# Node_Plant_Project.net
KiCad netlist of a schematic drawn in EasyEDA
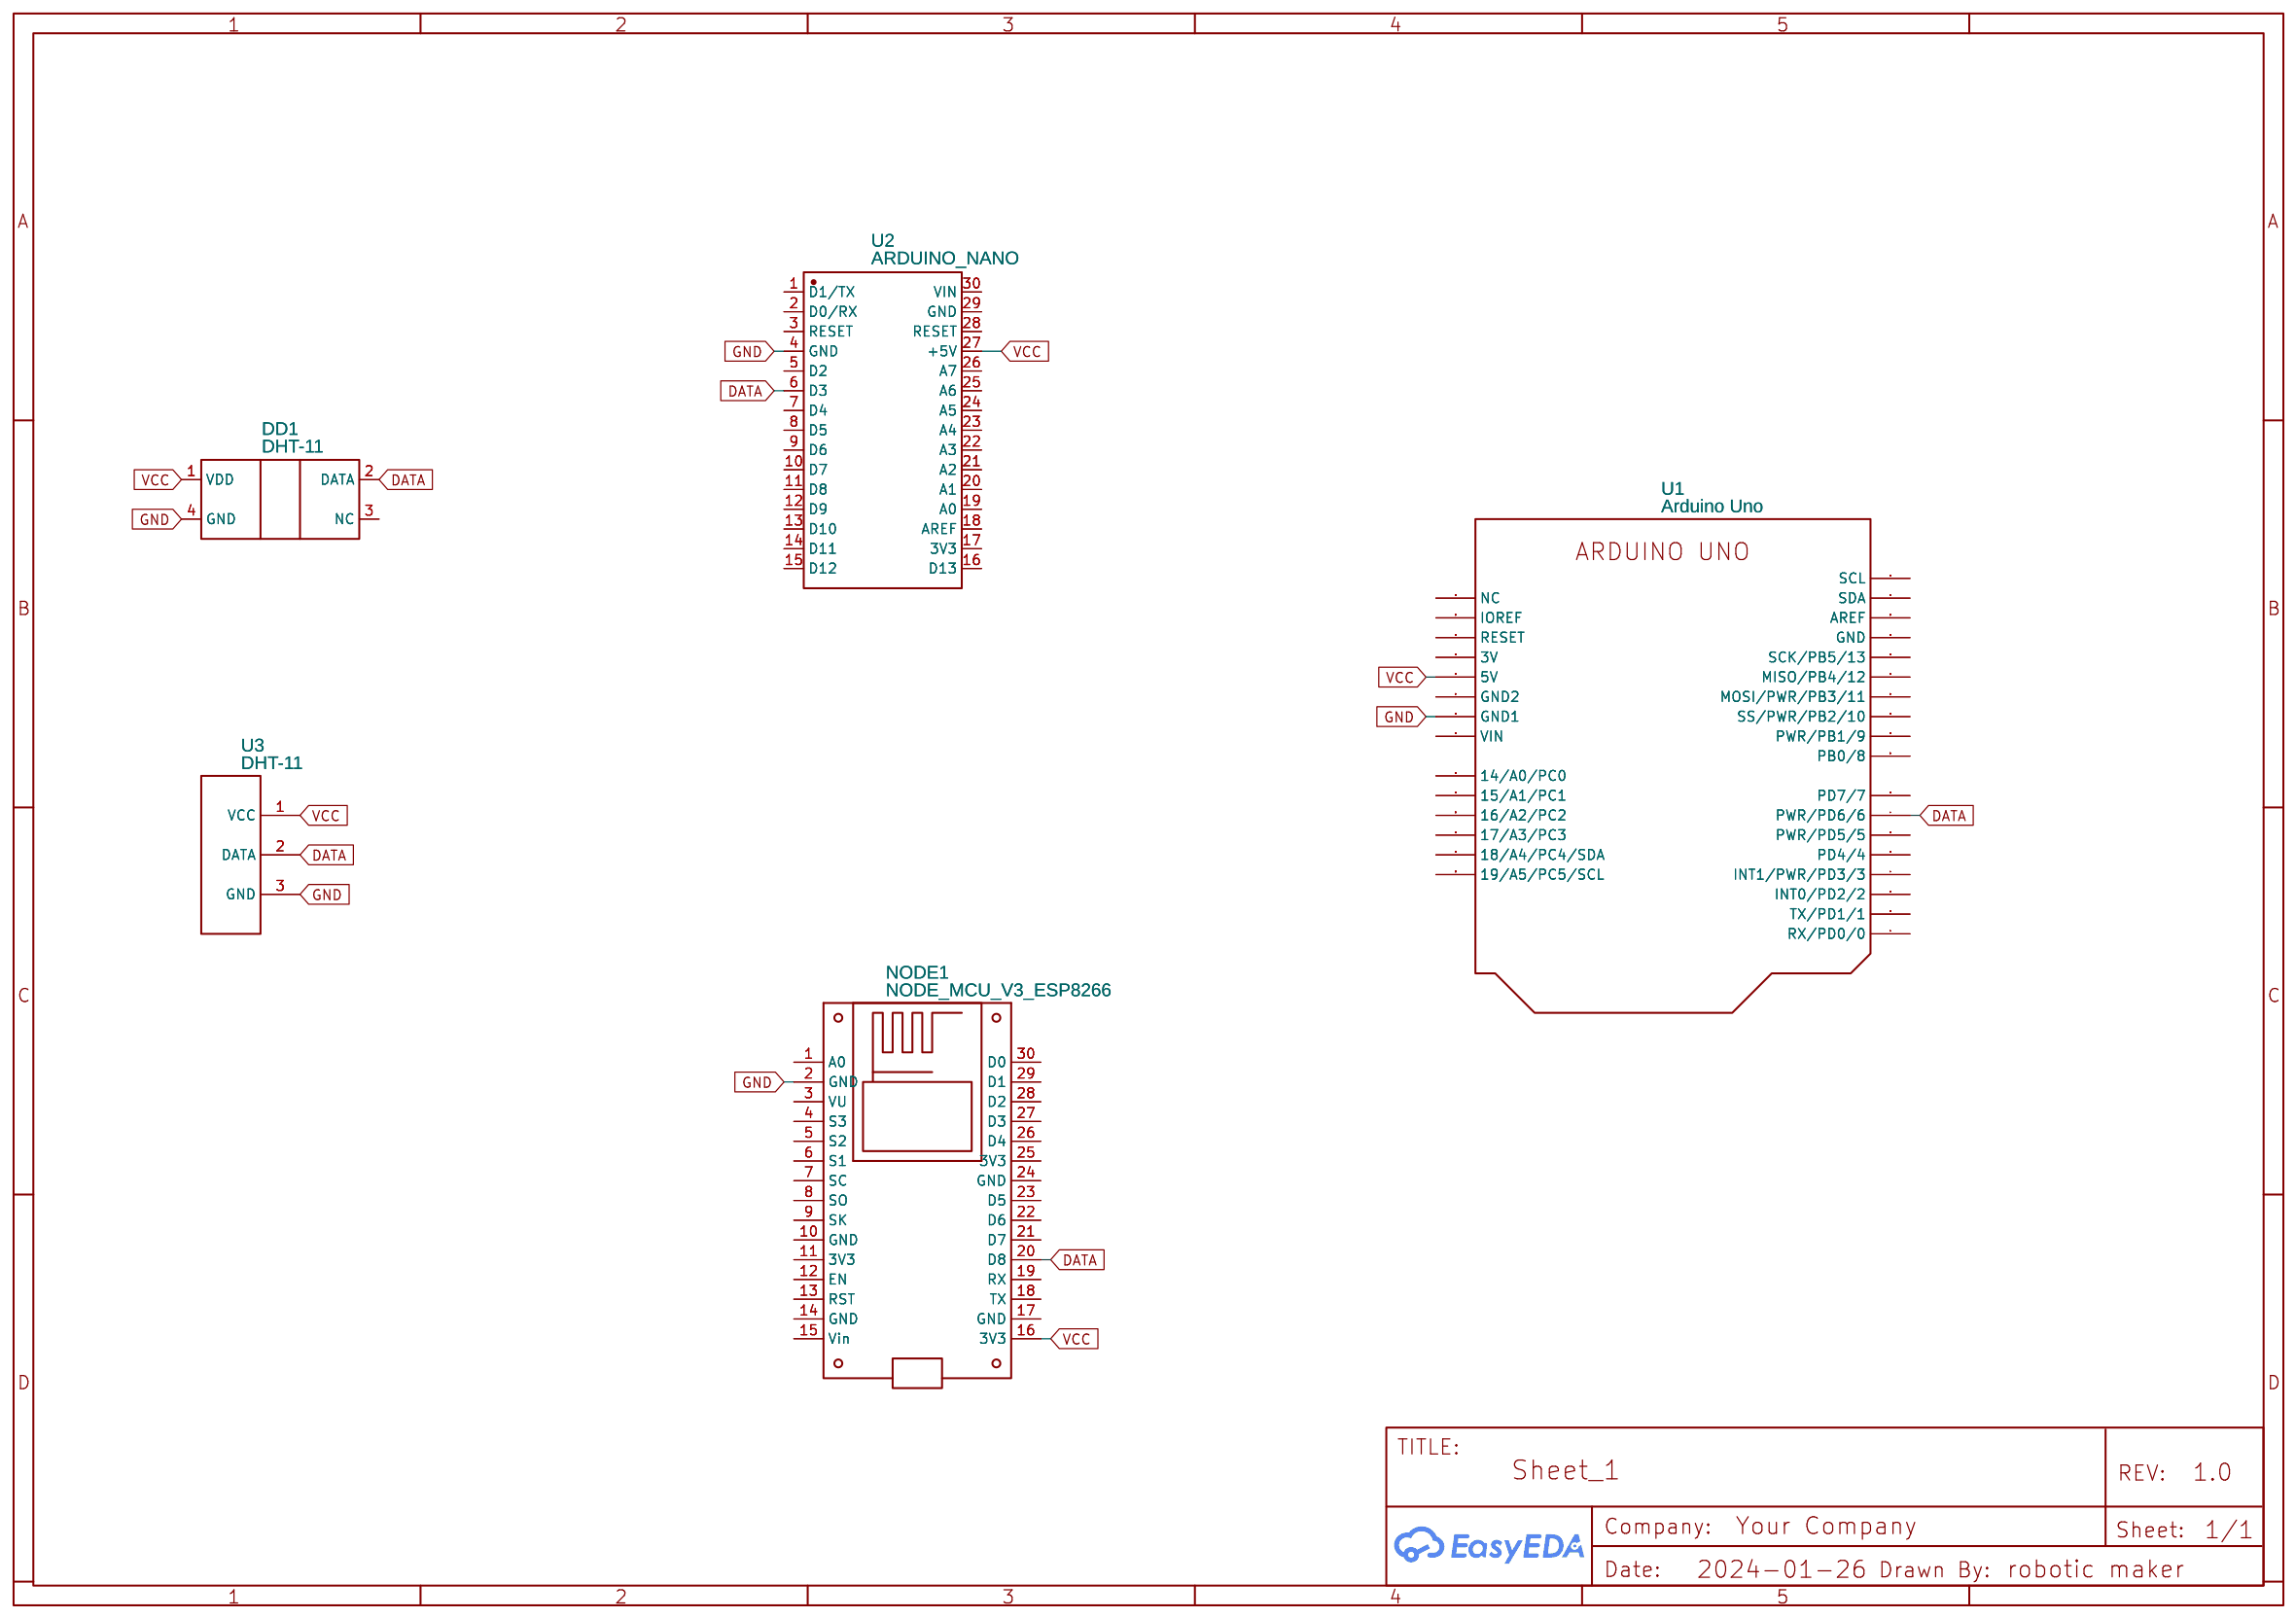
[diagram p0: DHT-11 & DHT-22]
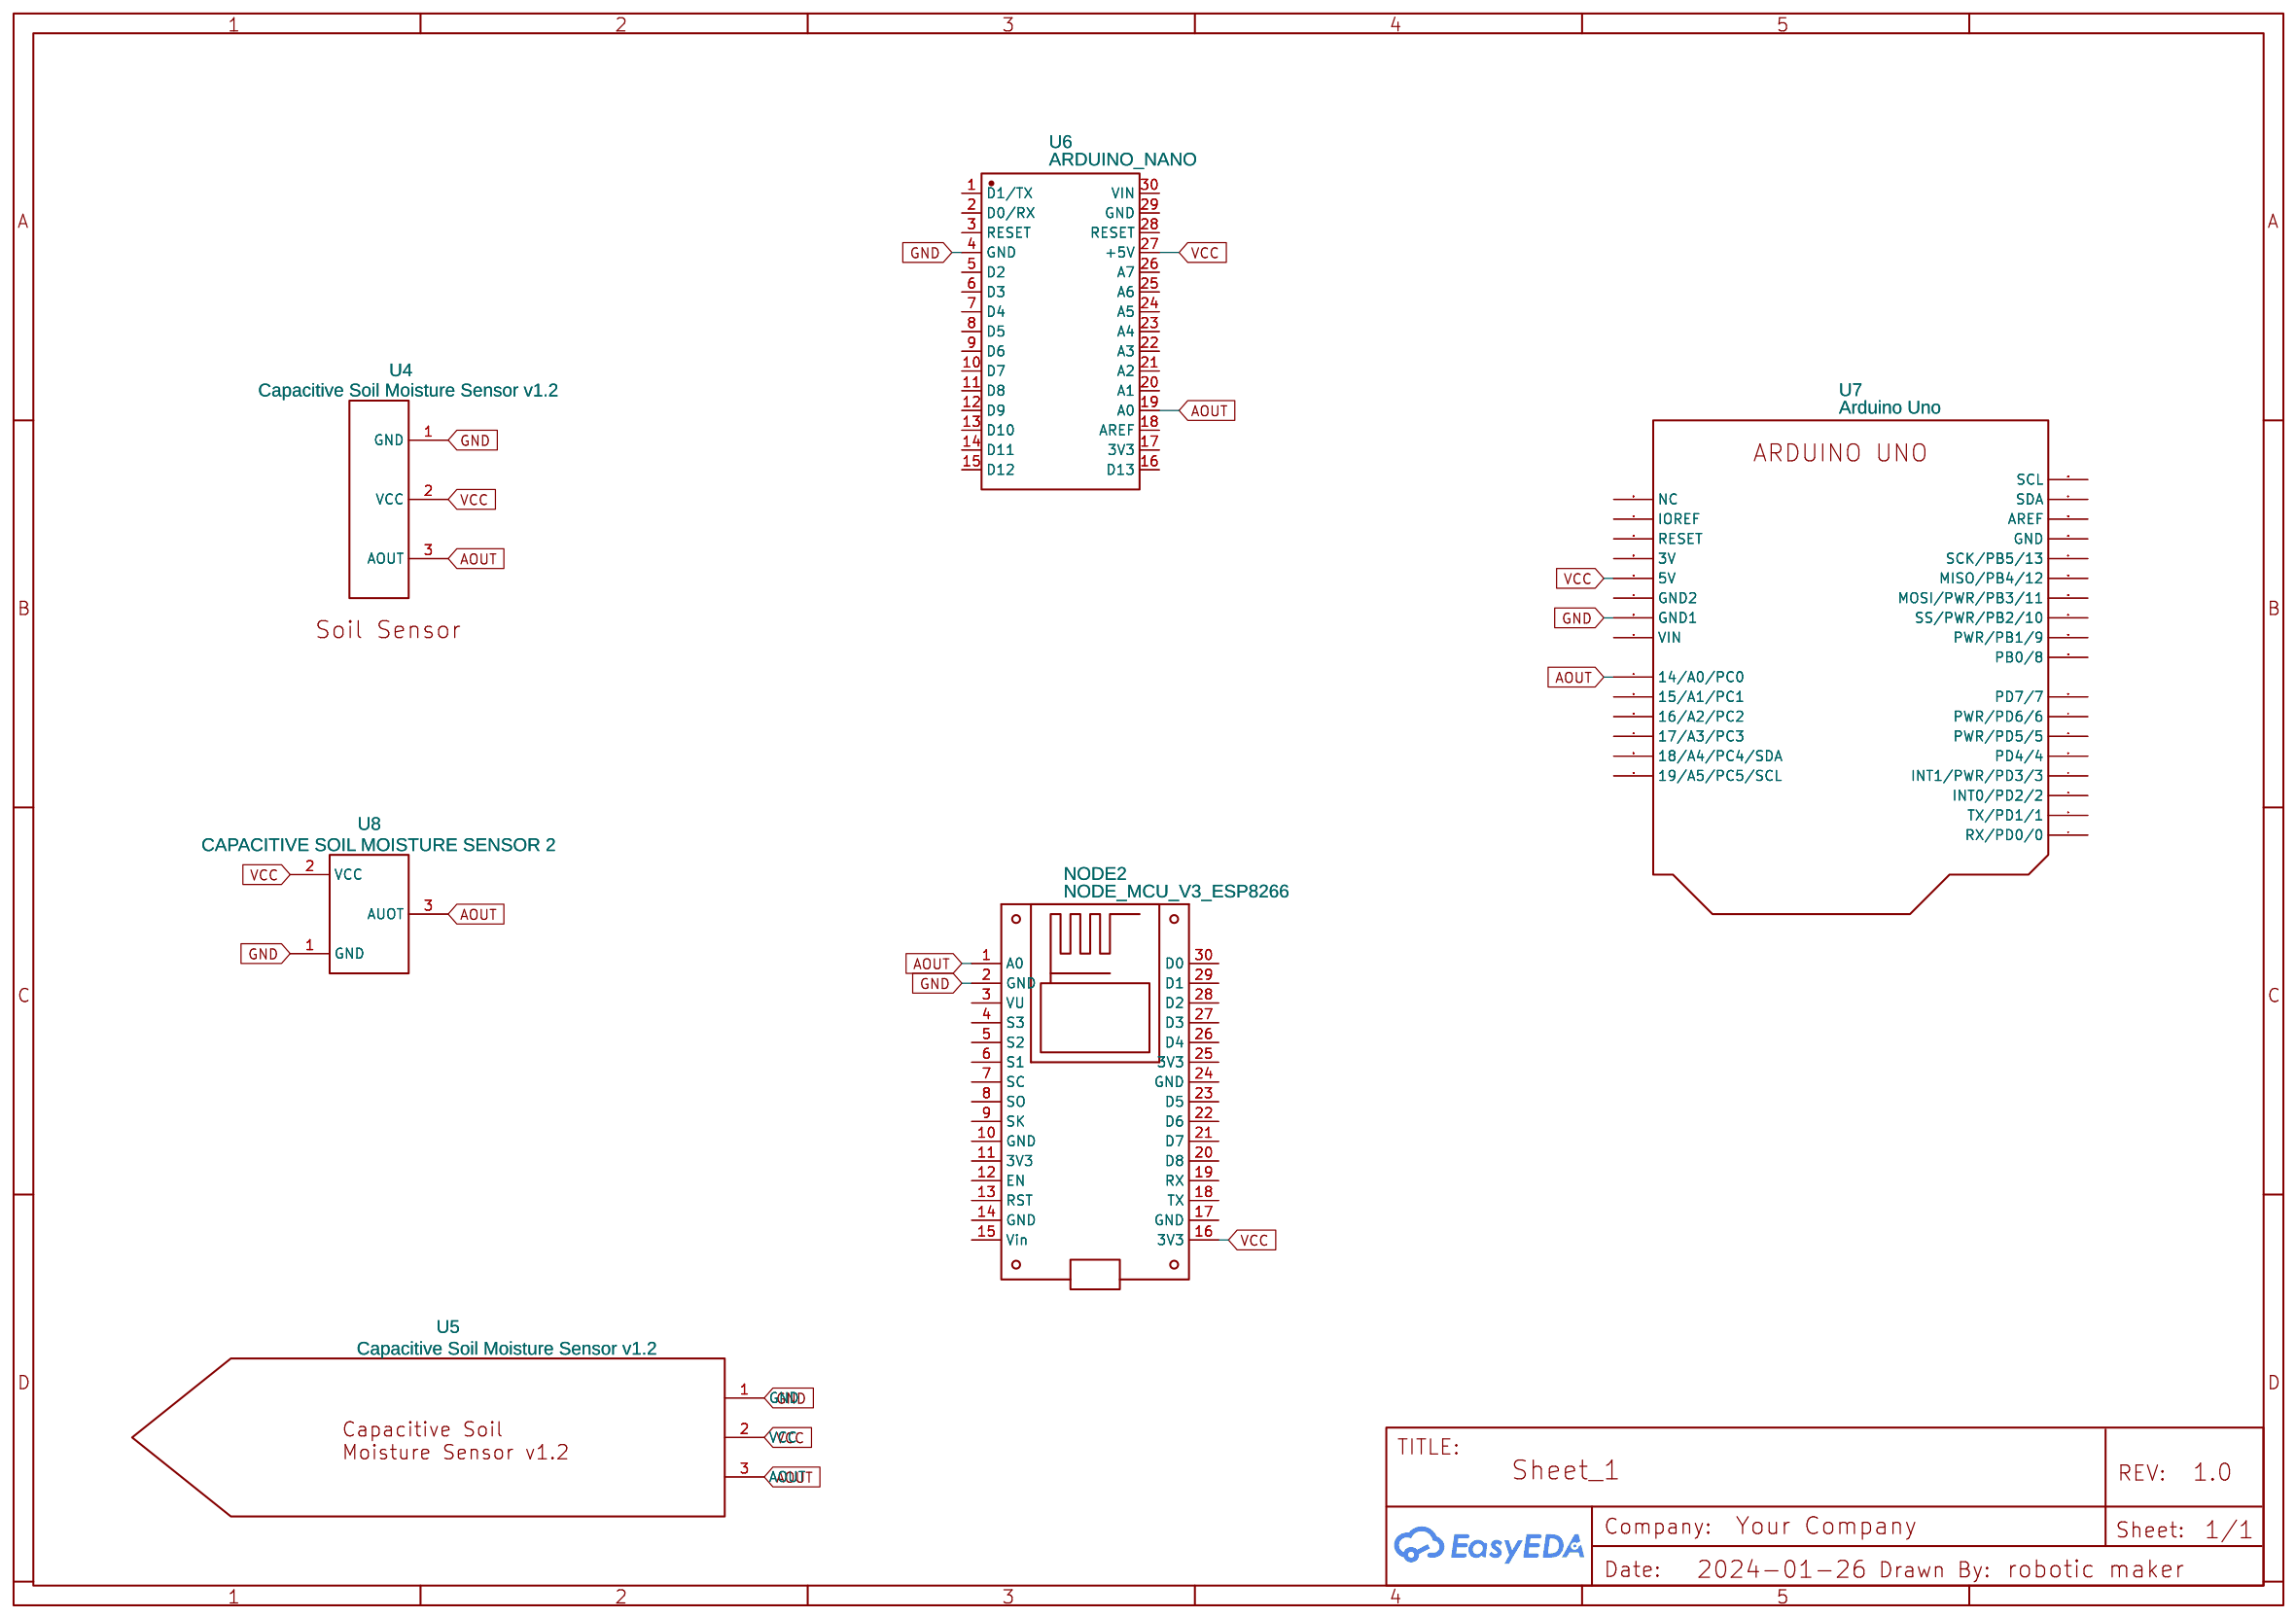
[diagram p1: Capacitive Soil Moisture Sensor]
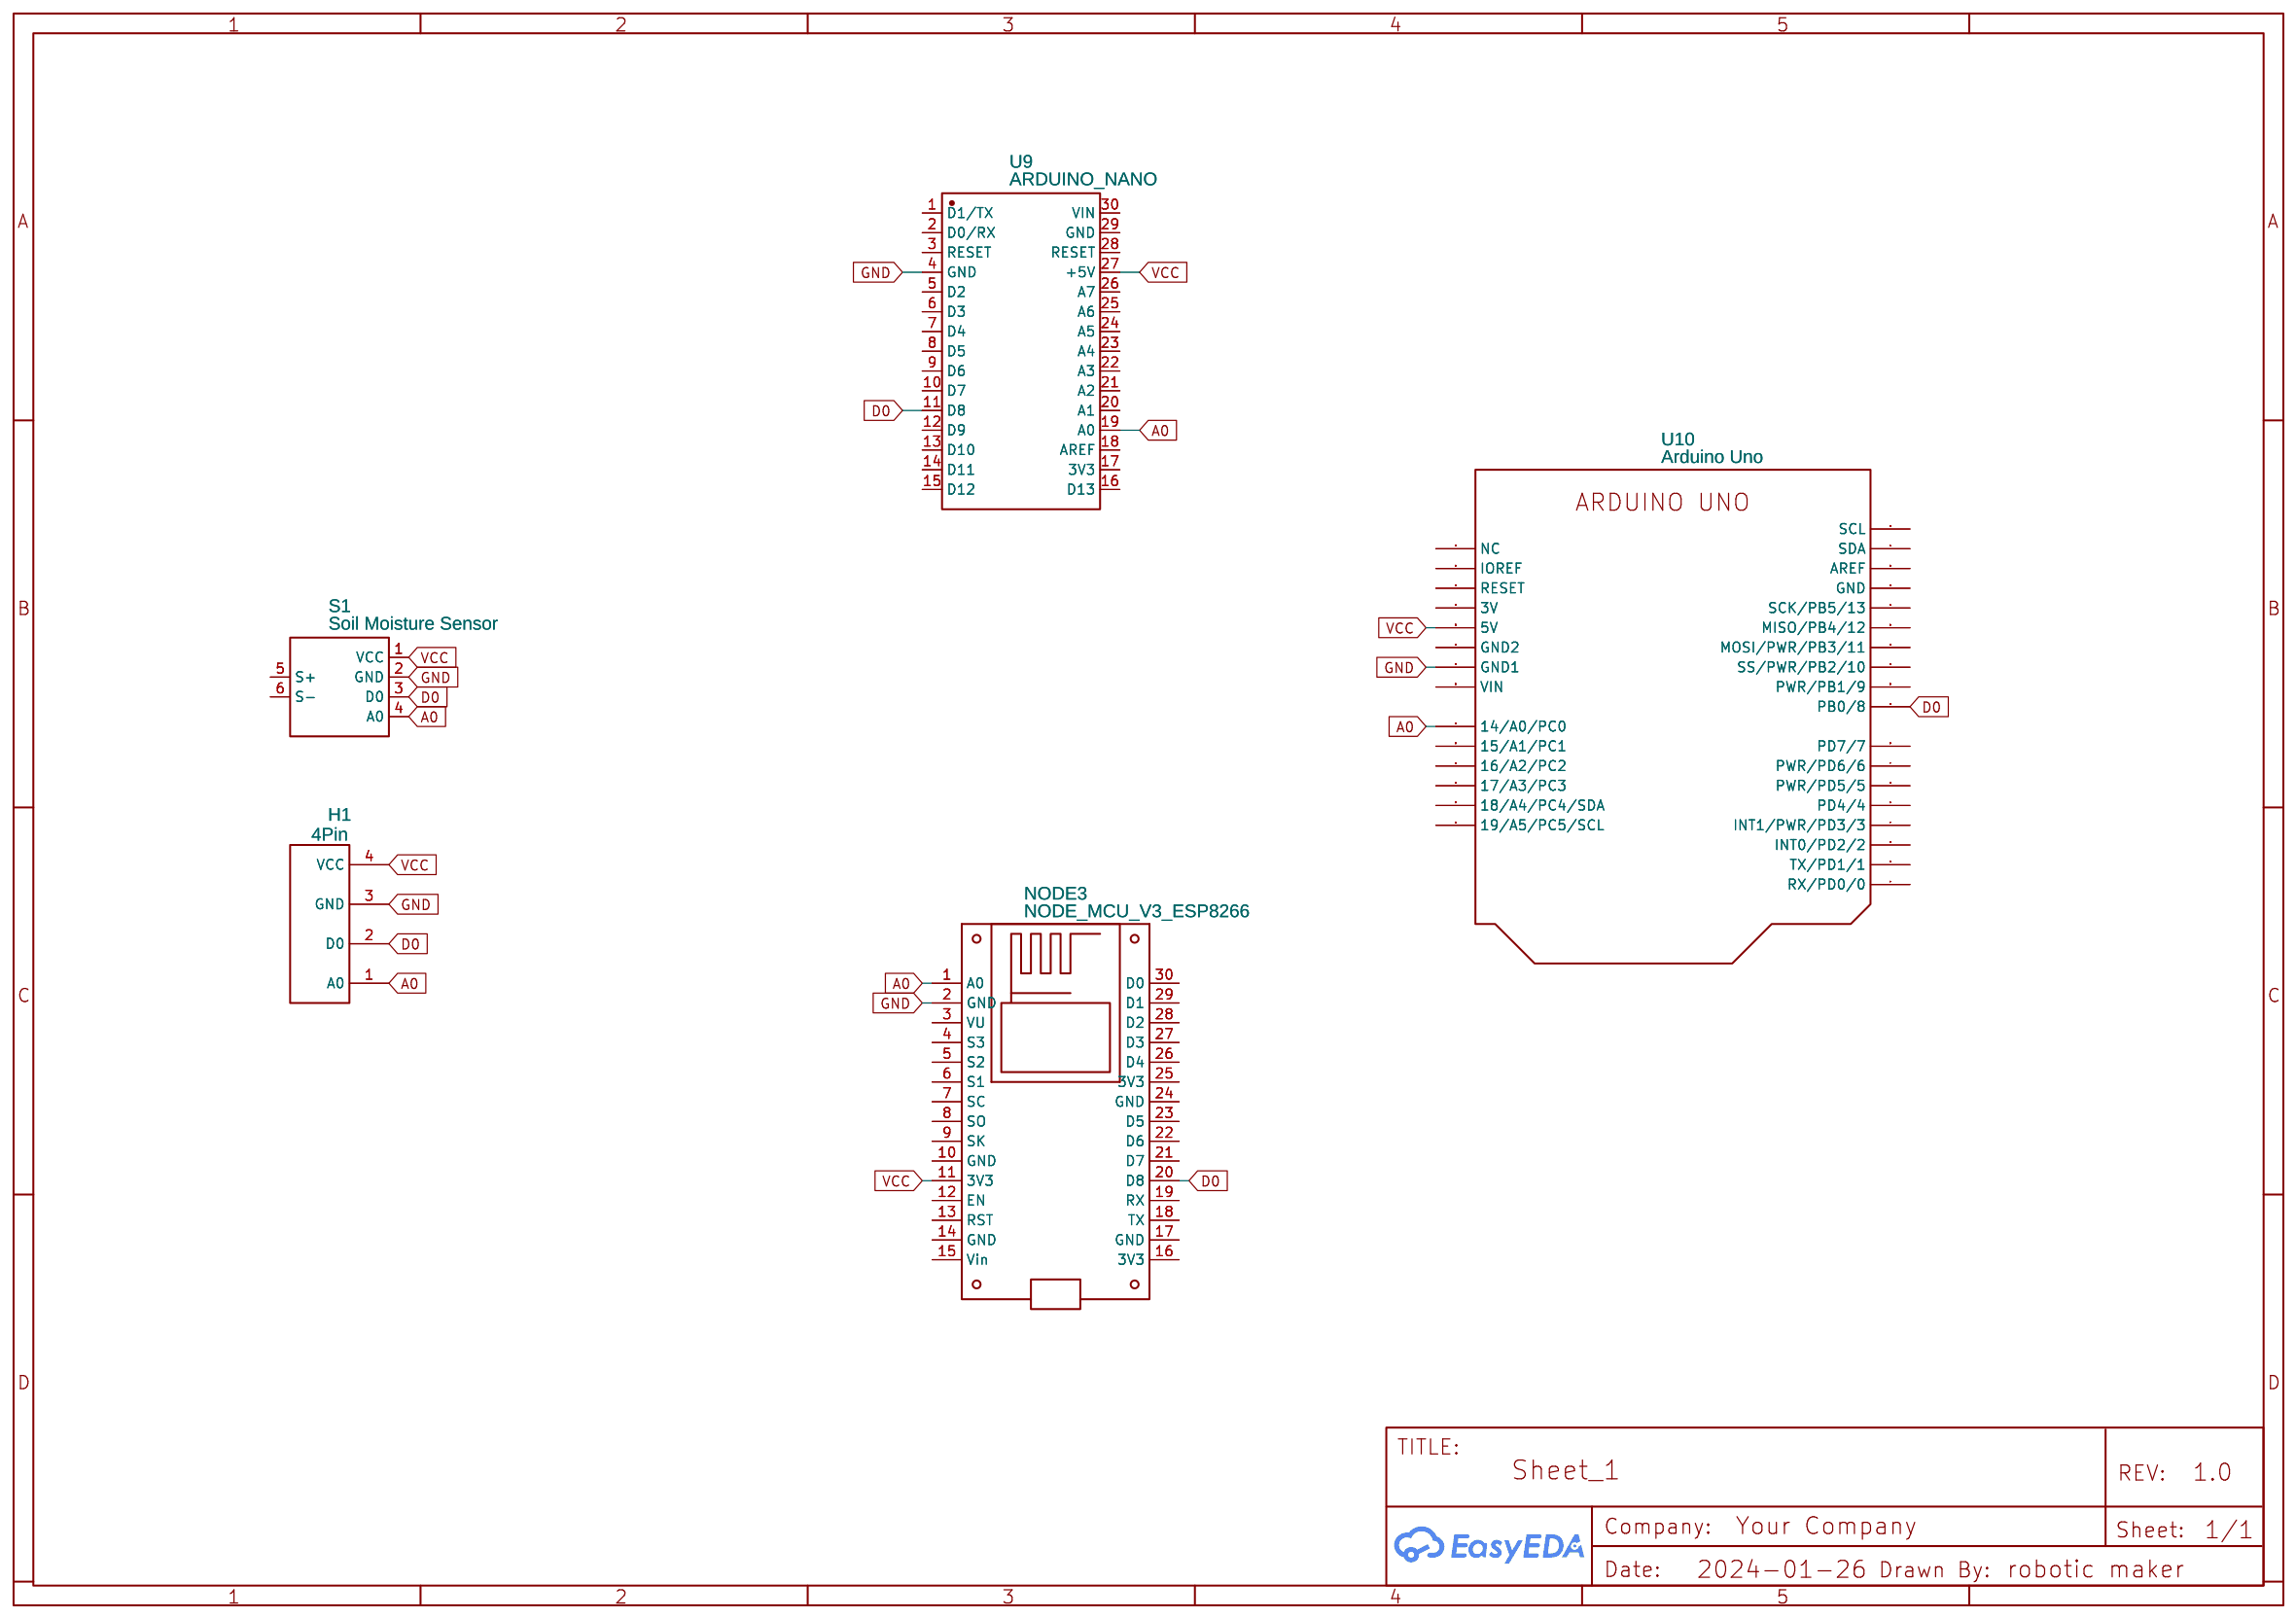
[diagram p2: Soil Moisture Sensor]
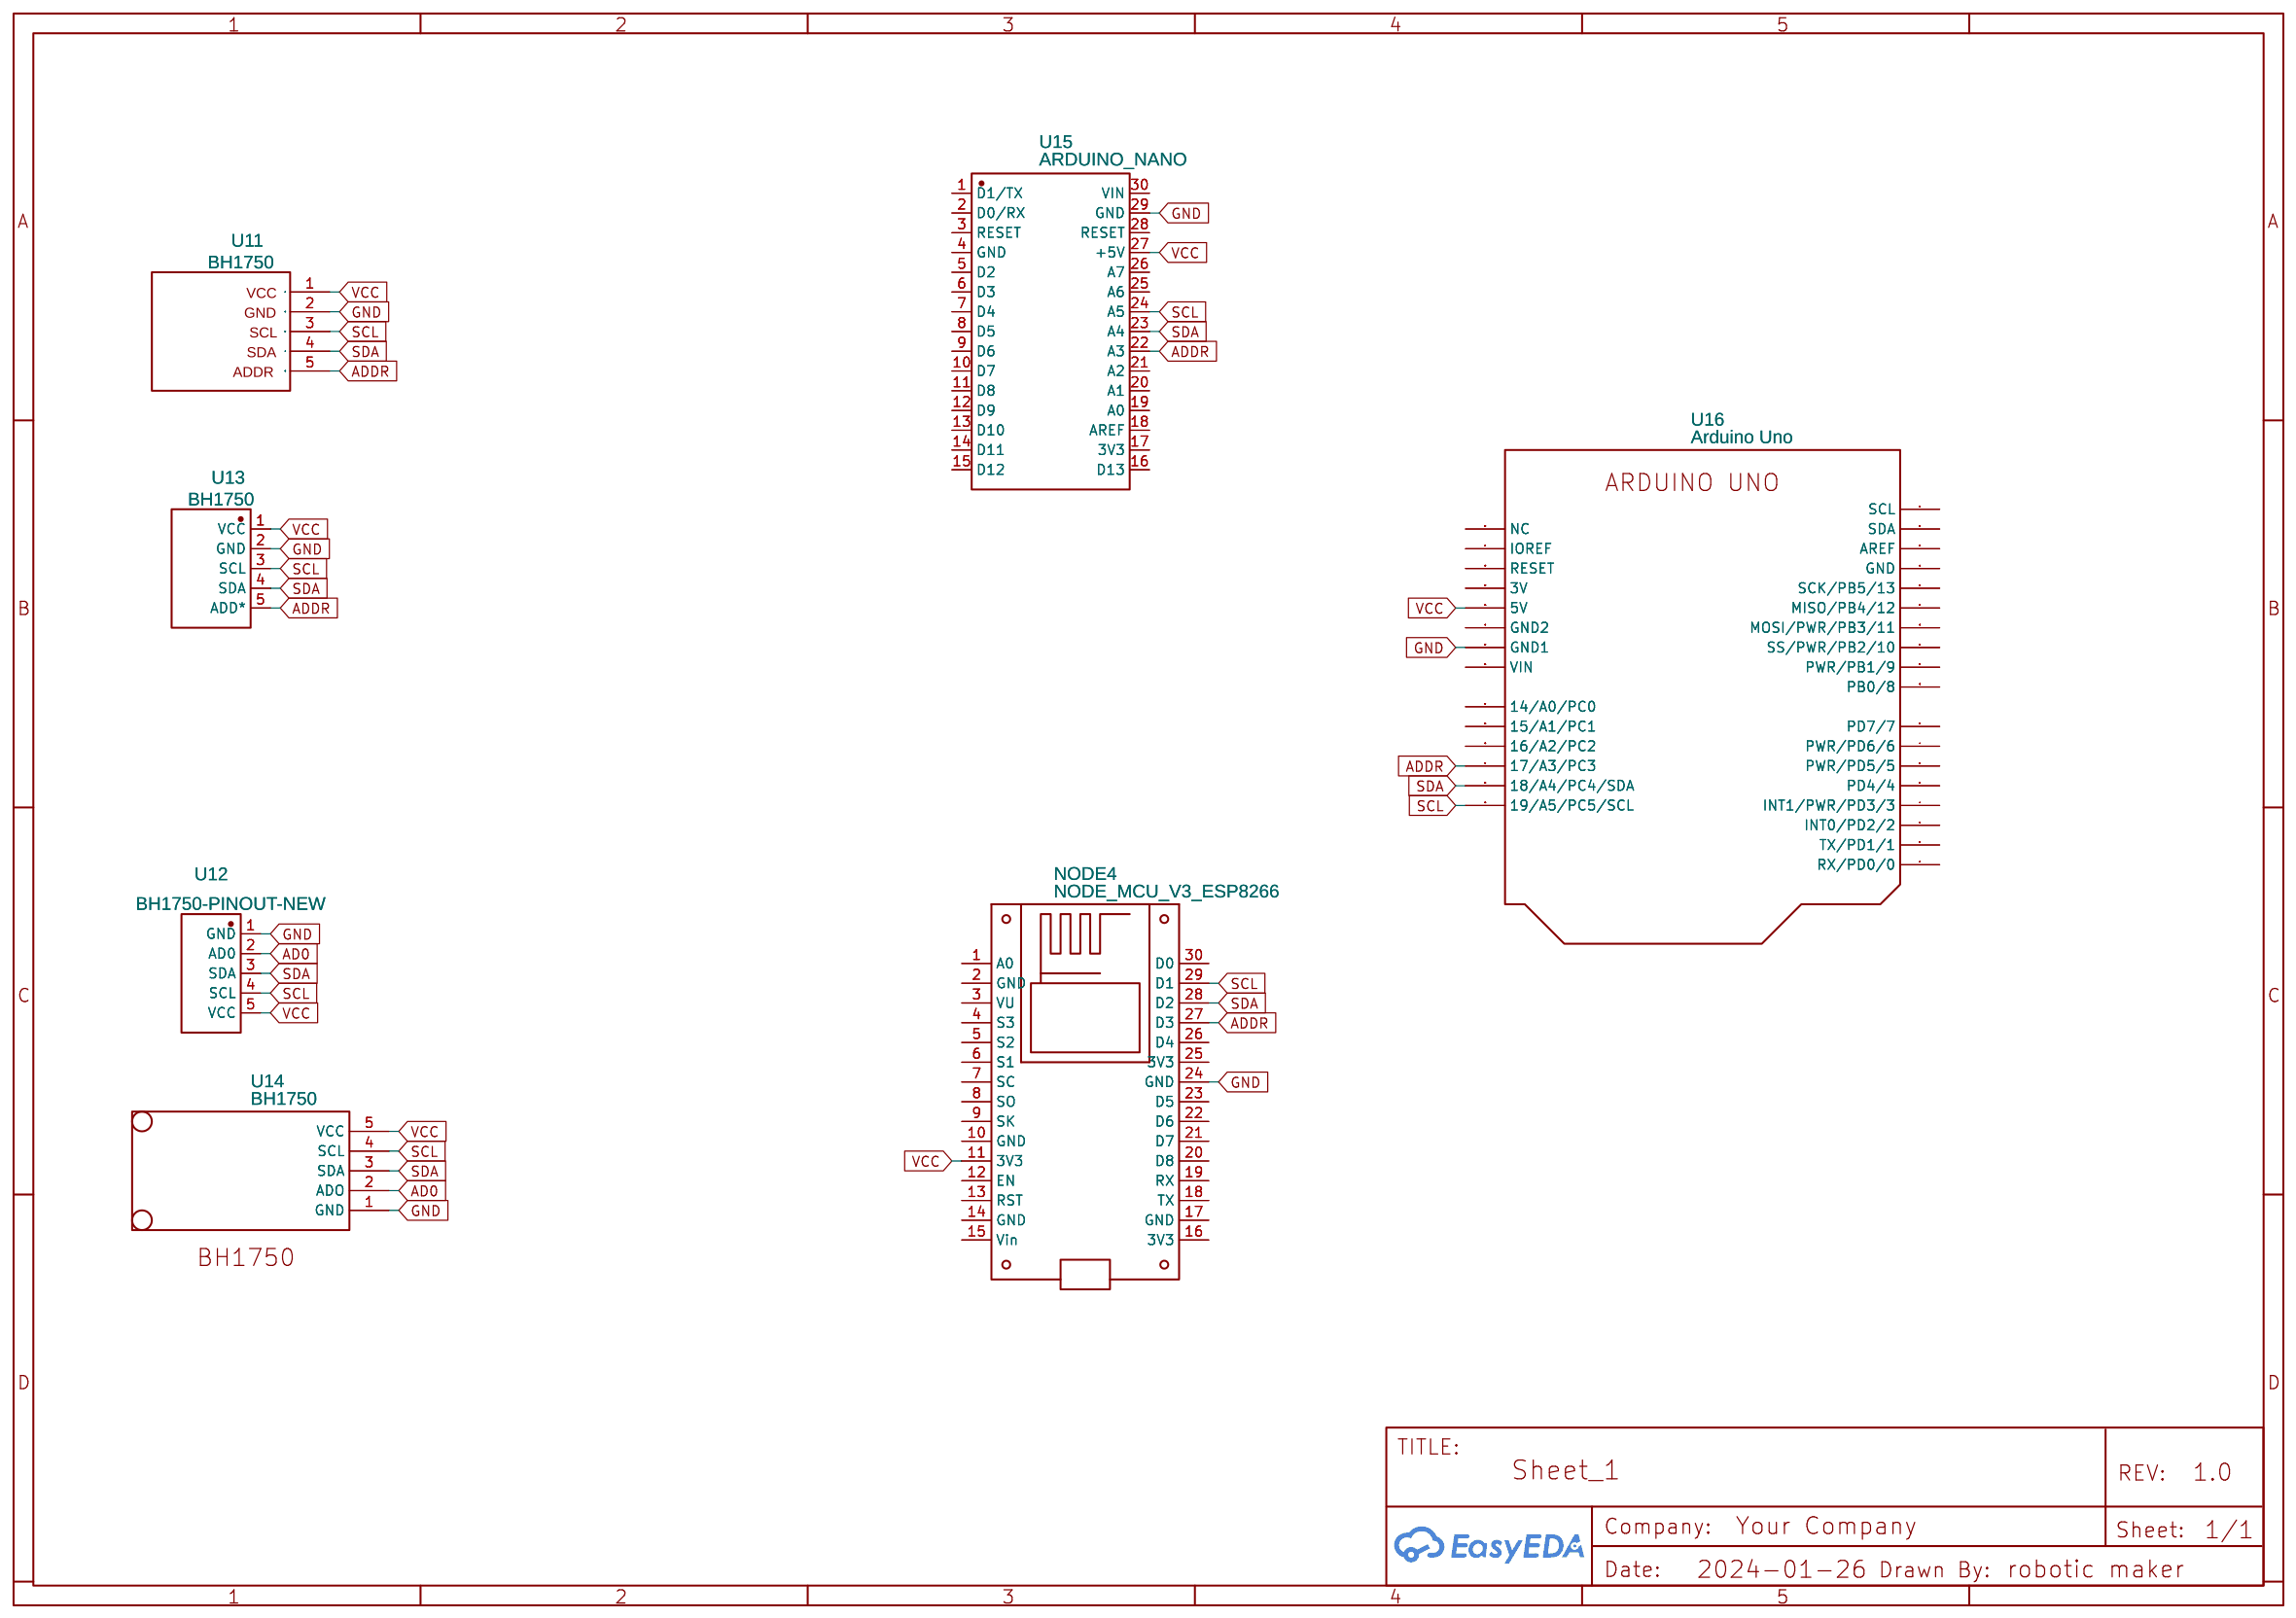
[diagram p3: BH1750]
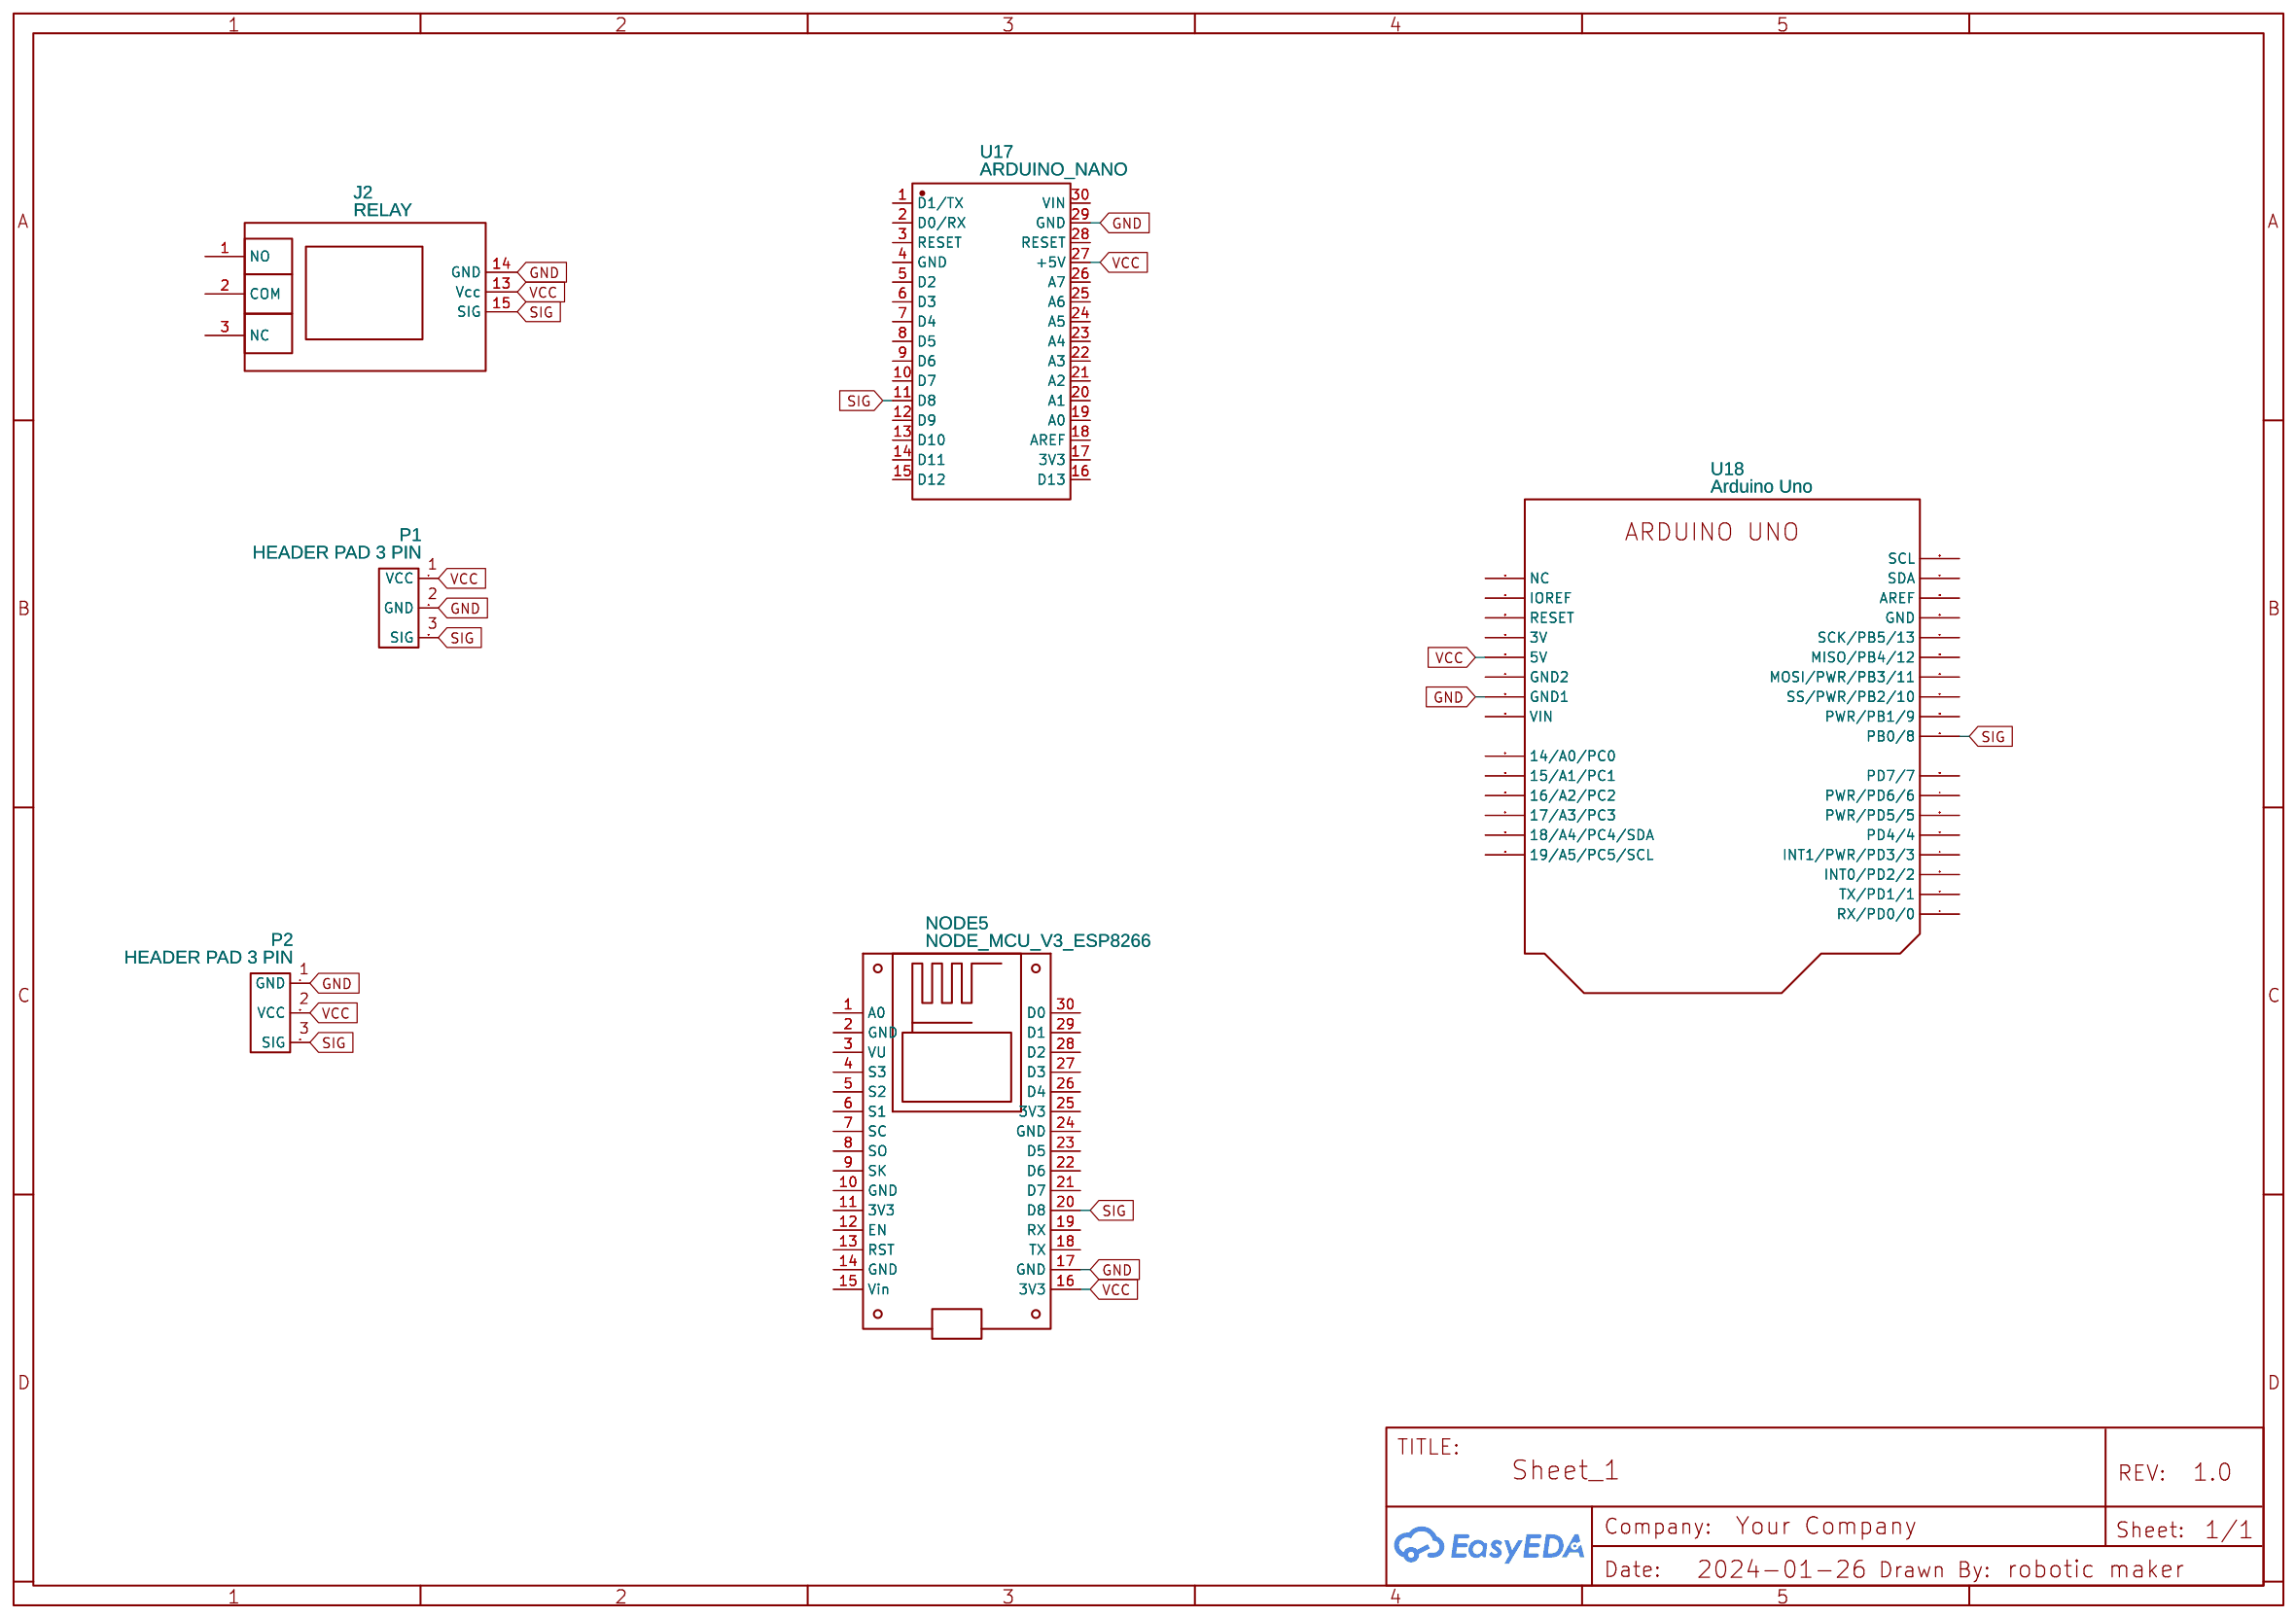
[diagram p4: Relay]
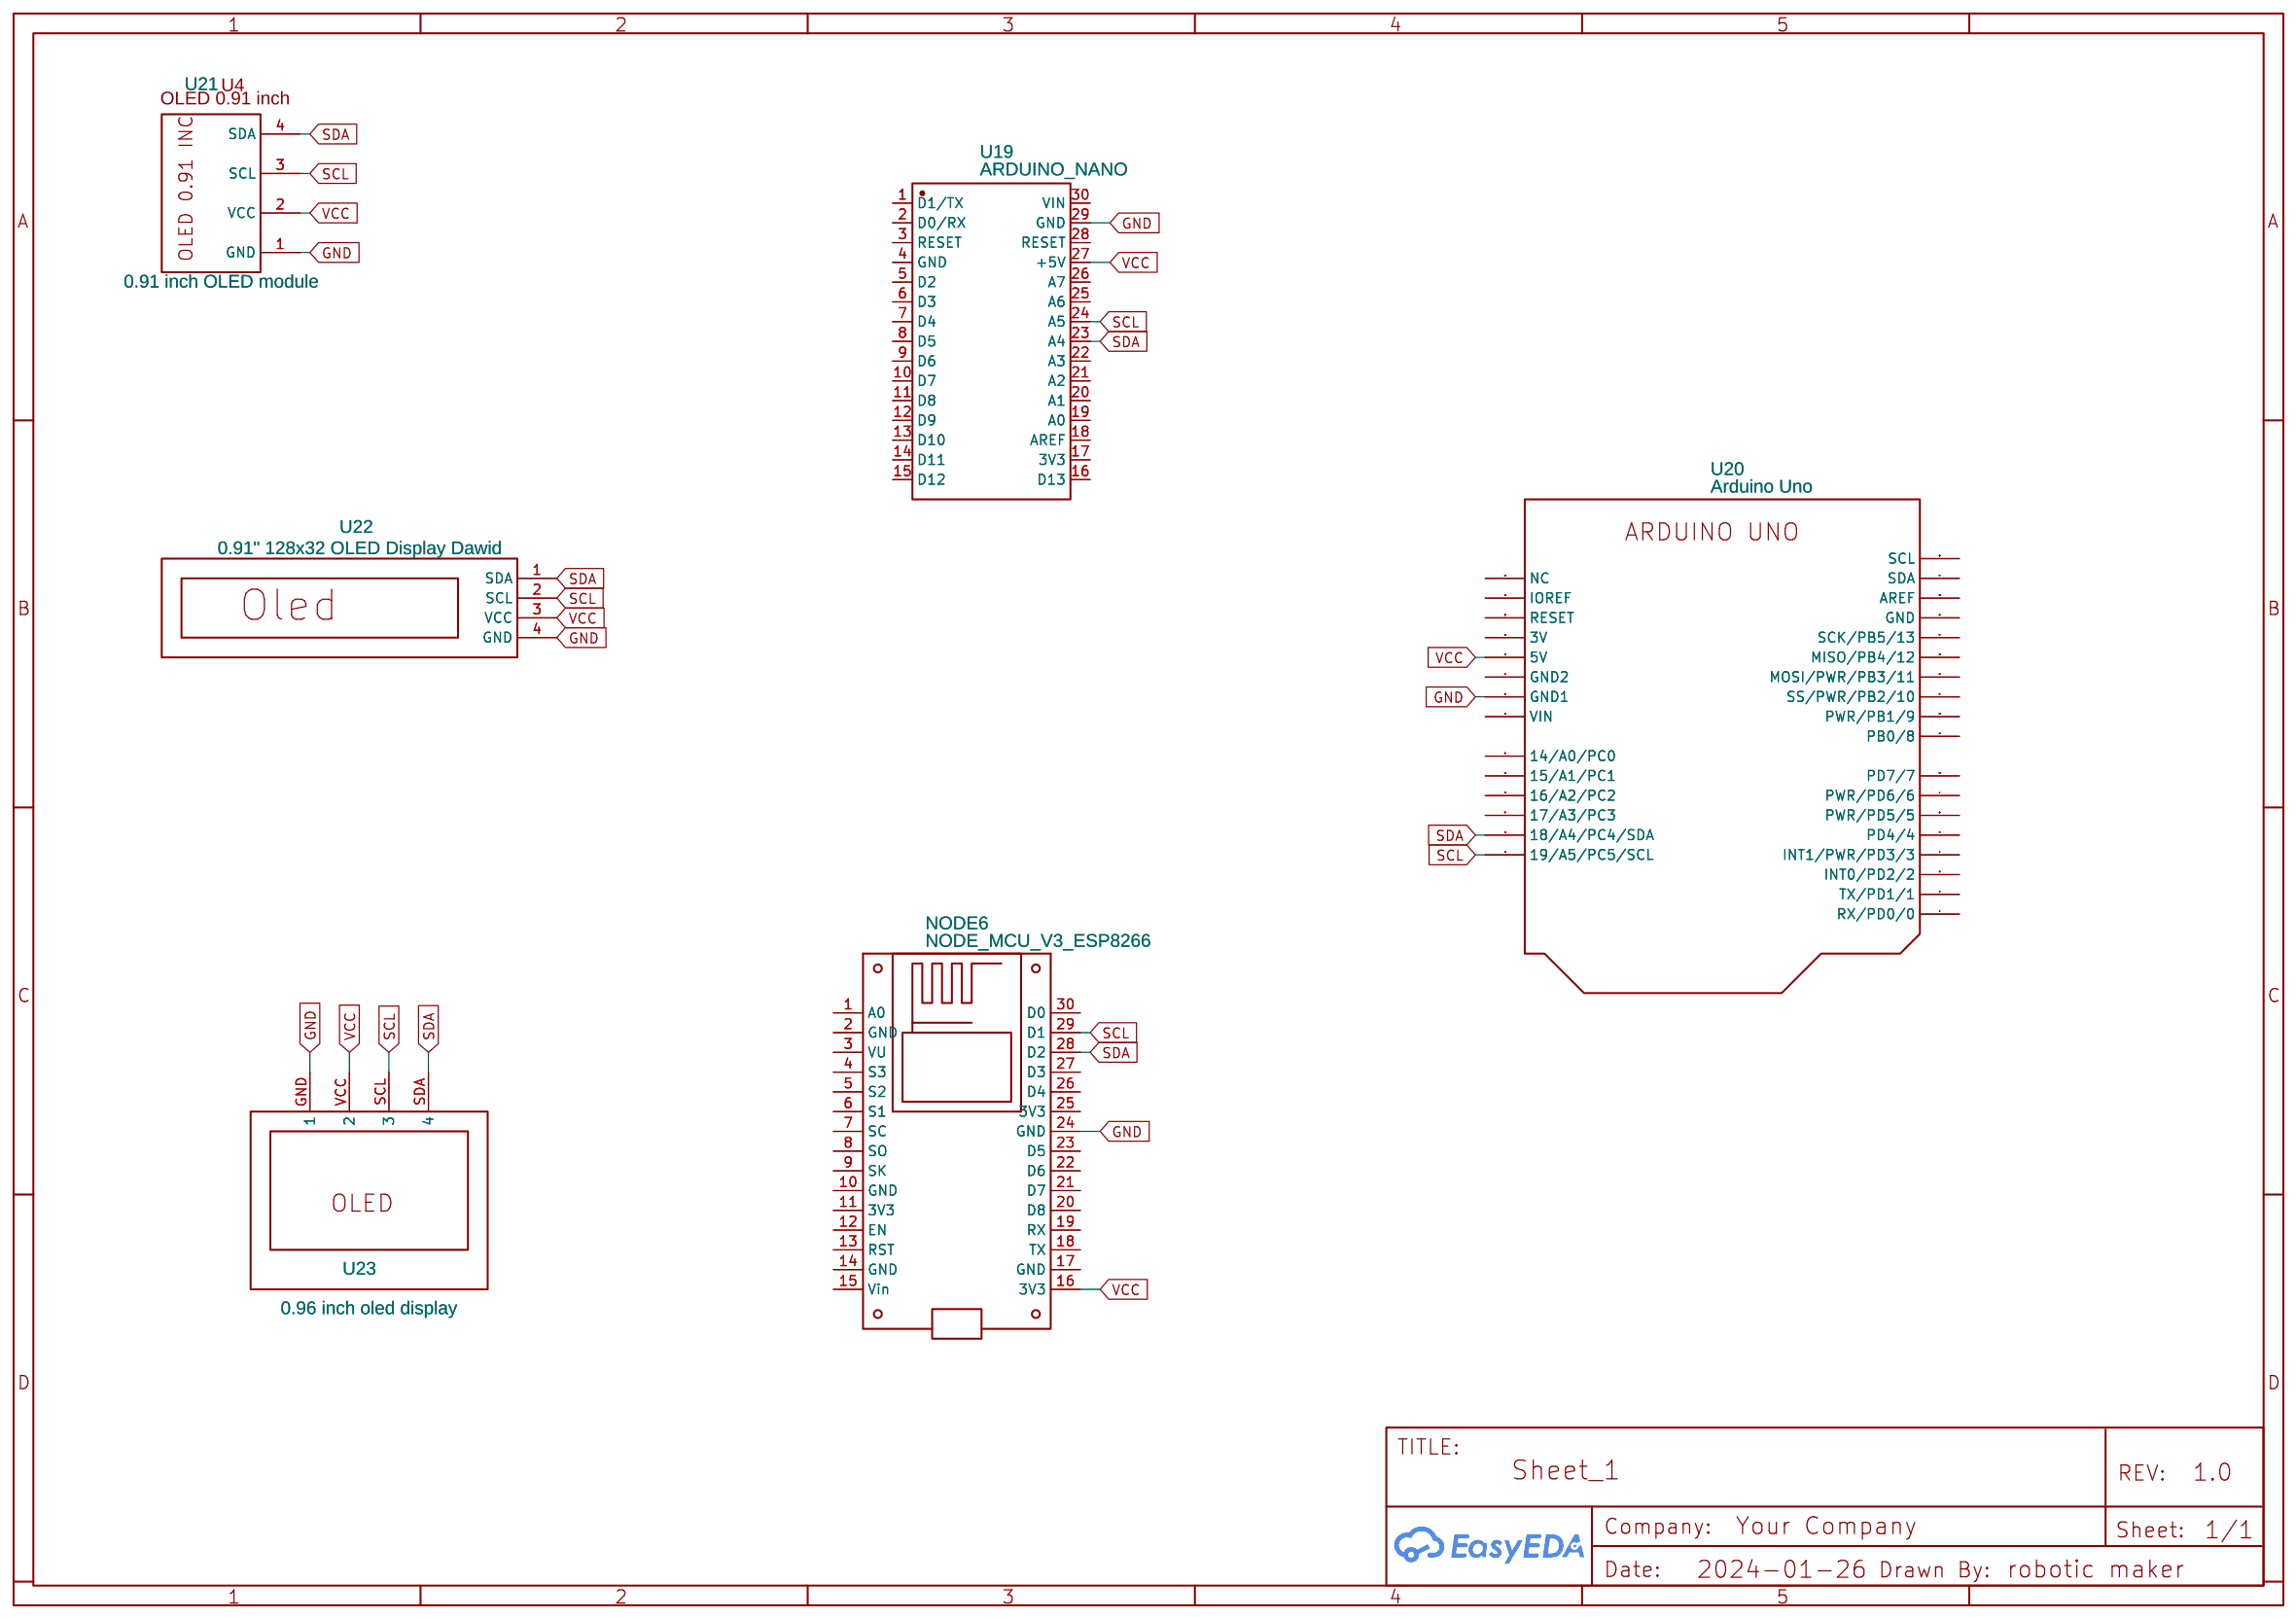
[diagram p5: 0.91 INCH OLED Display]
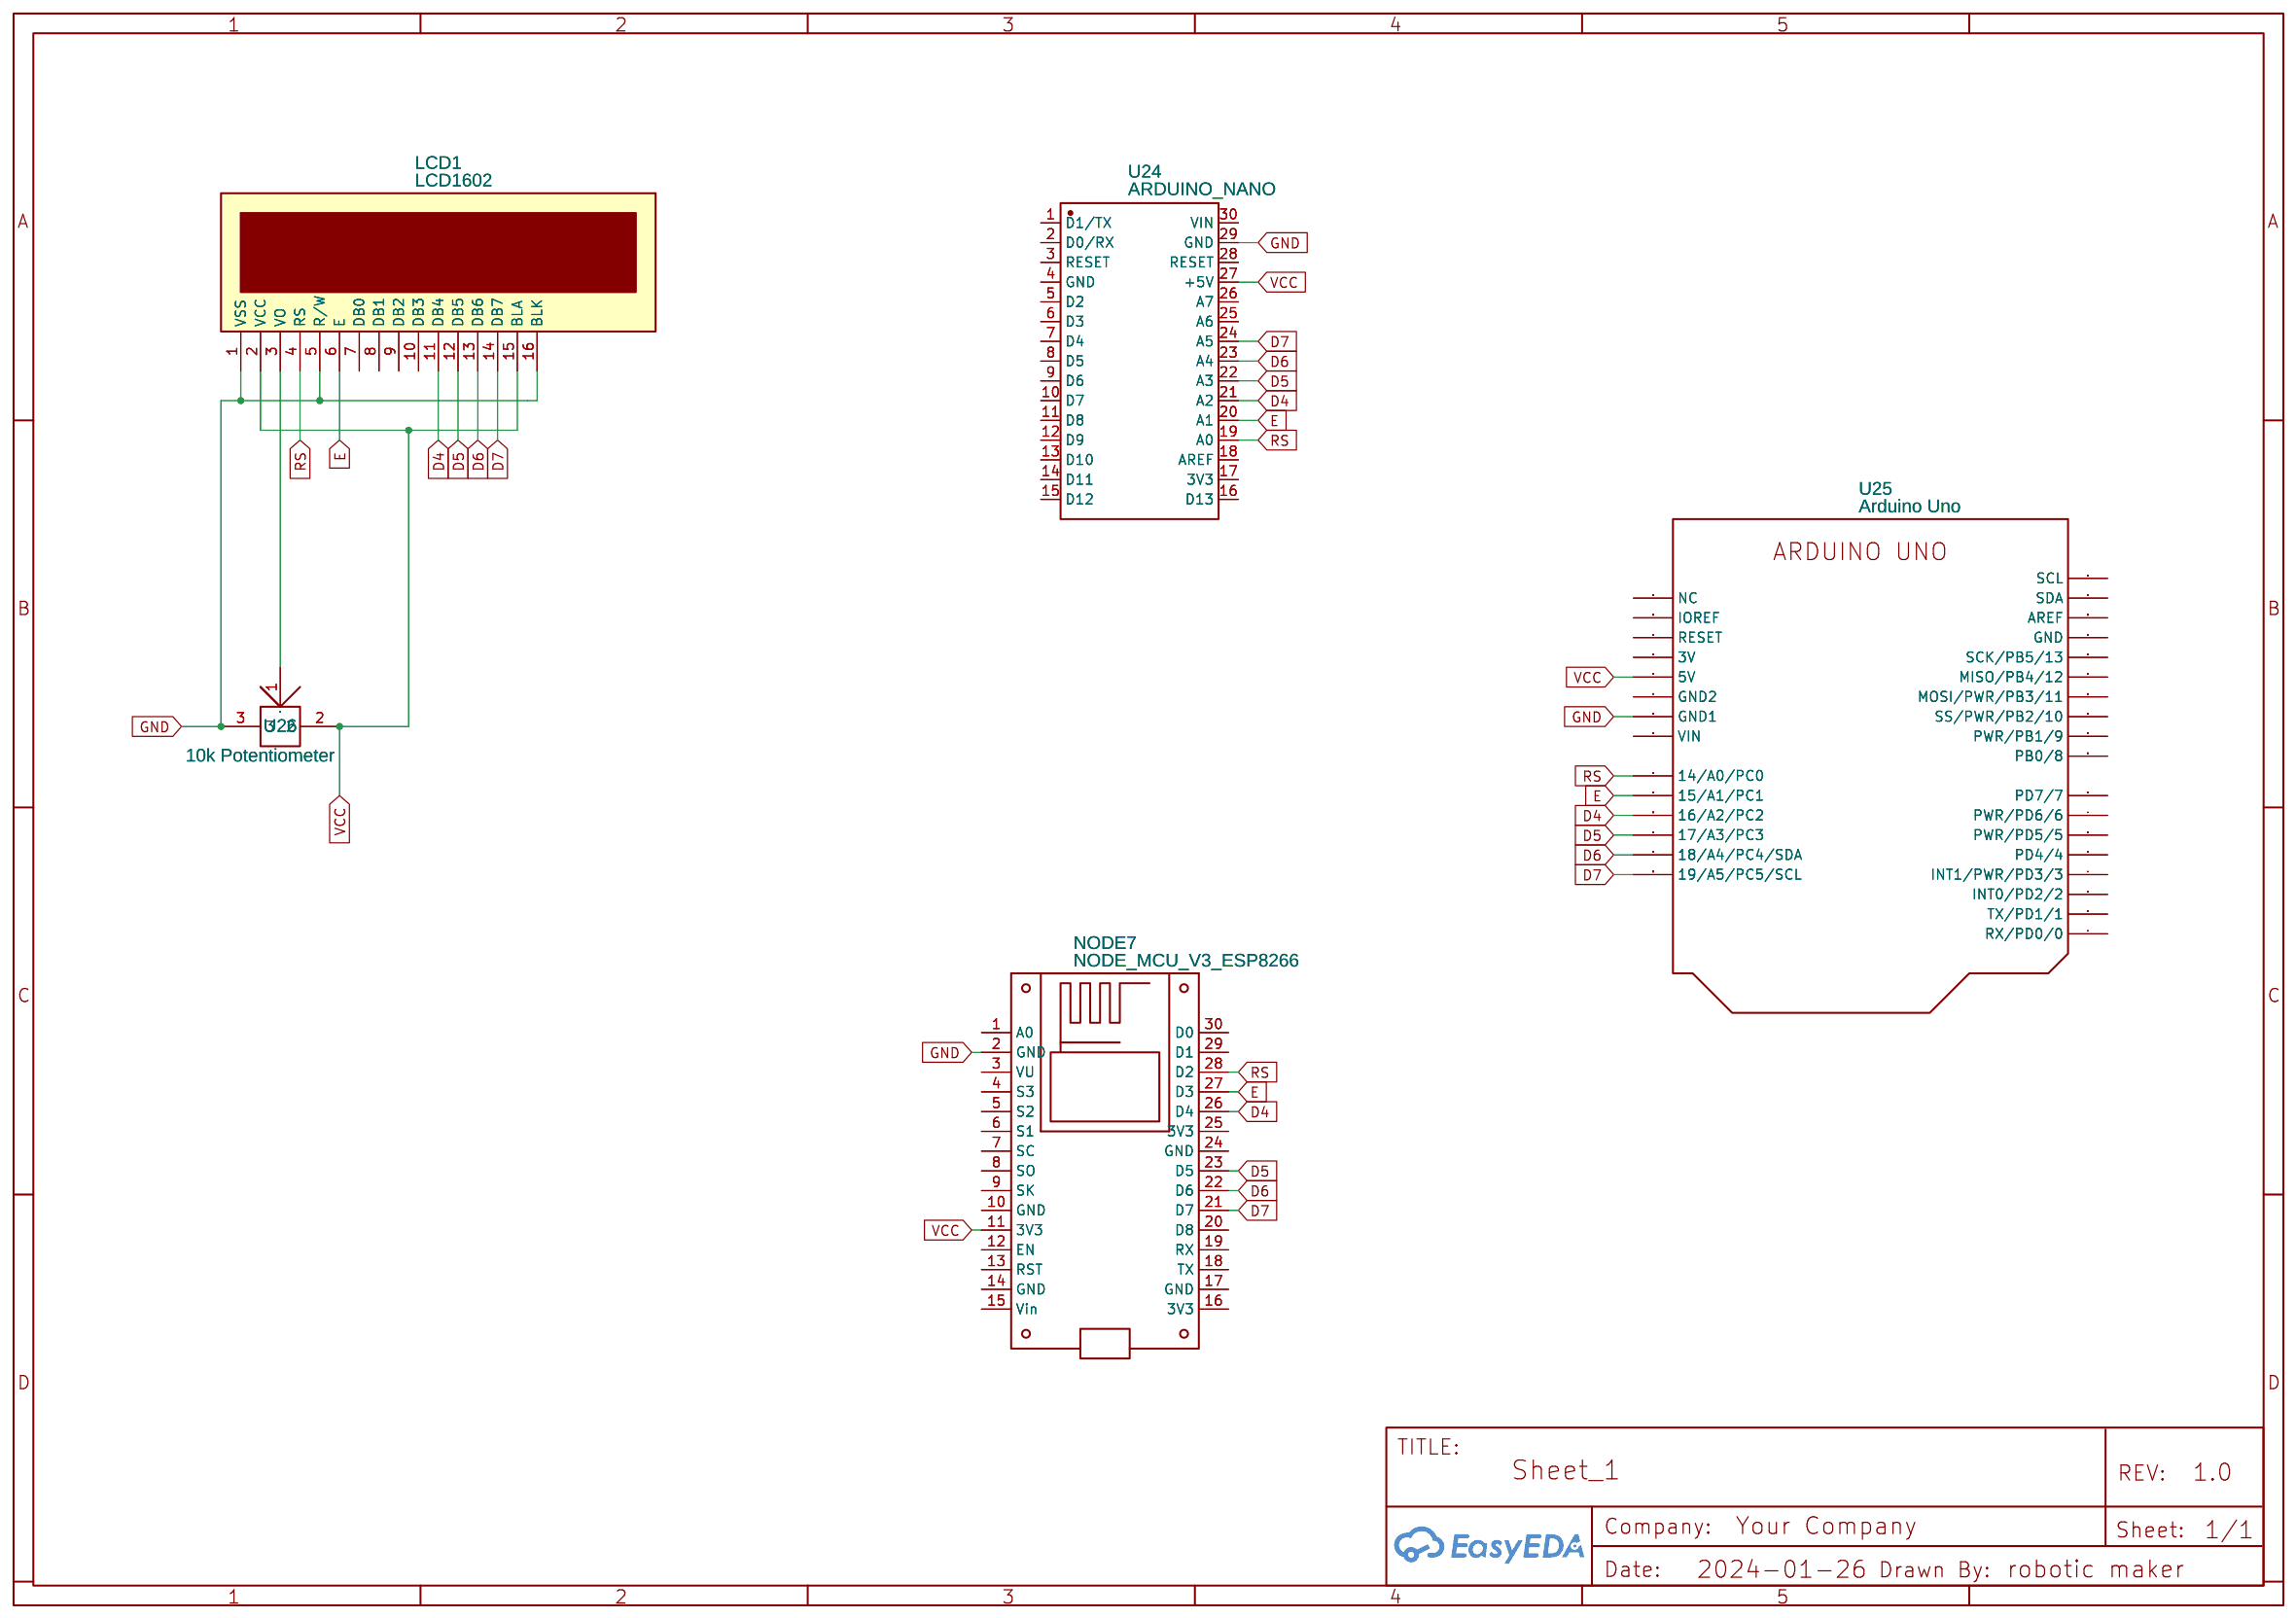
[diagram p6: 16X2 LCD Display]
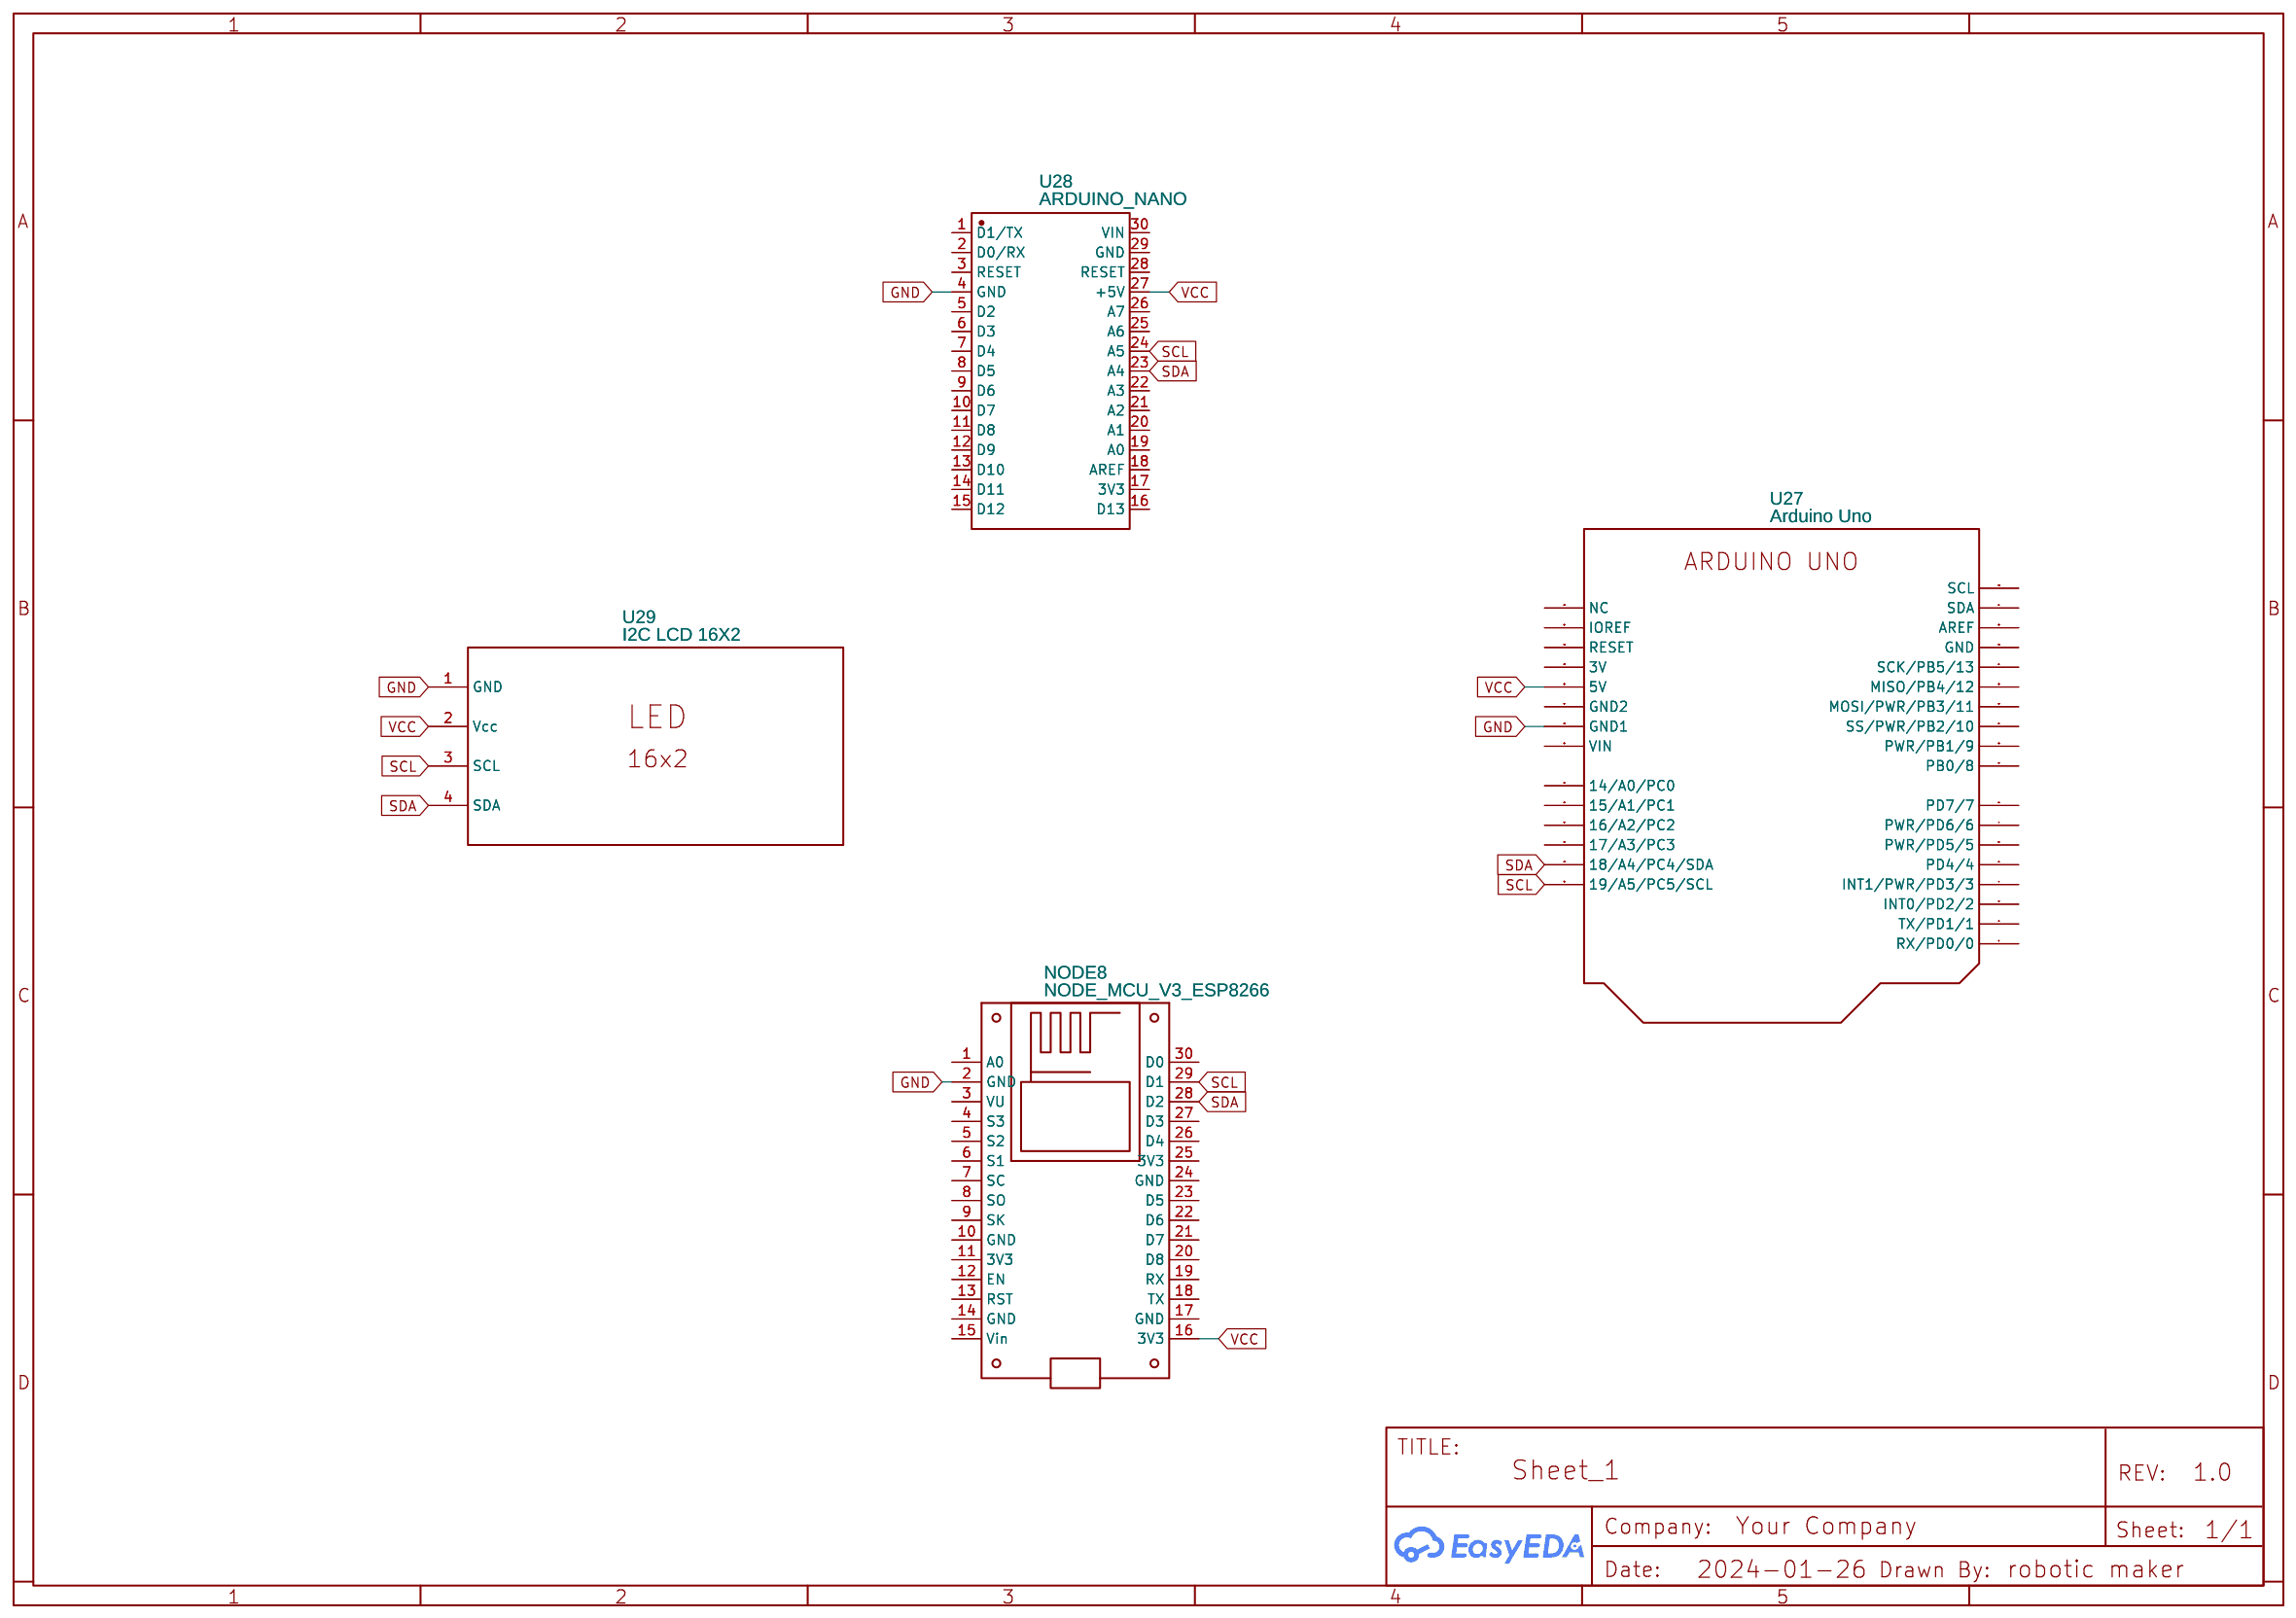
[diagram p7: 16X2 LCD Display I2C]

(export (version "E")
  (design (tool "Eeschema 10.0.6"))
  (components
    (comp (ref "DD1") (value "DHT-11") (libsource (lib "") (part "DHT-11_1")))
    (comp (ref "NODE1") (value "NODE_MCU_V3_ESP8266") (libsource (lib "") (part "NODE_MCU_V3_ESP8266")))
    (comp (ref "U1") (value "Arduino Uno") (libsource (lib "") (part "Arduino Uno")))
    (comp (ref "U2") (value "ARDUINO_NANO") (libsource (lib "") (part "ARDUINO_NANO")))
    (comp (ref "U3") (value "DHT-11") (libsource (lib "") (part "DHT-11")))
    (comp (ref "NODE2") (value "NODE_MCU_V3_ESP8266") (libsource (lib "") (part "NODE_MCU_V3_ESP8266")))
    (comp (ref "U4")
      (value "Capacitive Soil Moisture Sensor v1.2")
      (libsource (lib "") (part "Capacitive Soil Moisture Sensor v1.2"))
    )
    (comp (ref "U5")
      (value "Capacitive Soil Moisture Sensor v1.2")
      (libsource (lib "") (part "Capacitive Soil Moisture Sensor v1.2_1"))
    )
    (comp (ref "U6") (value "ARDUINO_NANO") (libsource (lib "") (part "ARDUINO_NANO")))
    (comp (ref "U7") (value "Arduino Uno") (libsource (lib "") (part "Arduino Uno")))
    (comp (ref "U8")
      (value "CAPACITIVE SOIL MOISTURE SENSOR 2")
      (libsource (lib "") (part "CAPACITIVE SOIL MOISTURE SENSOR 2"))
    )
    (comp (ref "H1") (value "4Pin") (libsource (lib "") (part "4Pin")))
    (comp (ref "NODE3") (value "NODE_MCU_V3_ESP8266") (libsource (lib "") (part "NODE_MCU_V3_ESP8266")))
    (comp (ref "S1") (value "Soil Moisture Sensor") (libsource (lib "") (part "Soil Moisture Sensor")))
    (comp (ref "U9") (value "ARDUINO_NANO") (libsource (lib "") (part "ARDUINO_NANO")))
    (comp (ref "U10") (value "Arduino Uno") (libsource (lib "") (part "Arduino Uno")))
    (comp (ref "NODE4") (value "NODE_MCU_V3_ESP8266") (libsource (lib "") (part "NODE_MCU_V3_ESP8266")))
    (comp (ref "U11") (value "BH1750") (libsource (lib "") (part "BH1750")))
    (comp (ref "U12")
      (value "BH1750-PINOUT-NEW")
      (fields (field (name "Manufacturer Part") "New SchematicLib"))
      (libsource (lib "") (part "BH1750-PINOUT-NEW"))
    )
    (comp (ref "U13") (value "BH1750") (libsource (lib "") (part "BH1750_2")))
    (comp (ref "U14") (value "BH1750") (libsource (lib "") (part "BH1750_1")))
    (comp (ref "U15") (value "ARDUINO_NANO") (libsource (lib "") (part "ARDUINO_NANO")))
    (comp (ref "U16") (value "Arduino Uno") (libsource (lib "") (part "Arduino Uno")))
    (comp (ref "J2")
      (value "RELAY")
      (fields (field (name "Manufacturer Part") "1-Channel 5V Relay Module w/ Opto-isolator"))
      (libsource (lib "") (part "RELAY"))
    )
    (comp (ref "NODE5") (value "NODE_MCU_V3_ESP8266") (libsource (lib "") (part "NODE_MCU_V3_ESP8266")))
    (comp (ref "P1")
      (value "HEADER PAD 3 PIN")
      (fields
        (field (name "Manufacturer Part") "Female headerHDR1X8-2.54")
        (field (name "Manufacturer") "BOOMELE")
      )
      (libsource (lib "") (part "HEADER PAD 3 PIN"))
    )
    (comp (ref "P2")
      (value "HEADER PAD 3 PIN")
      (fields
        (field (name "Manufacturer Part") "Female headerHDR1X8-2.54")
        (field (name "Manufacturer") "BOOMELE")
      )
      (libsource (lib "") (part "HEADER PAD 3 PIN_1"))
    )
    (comp (ref "U17") (value "ARDUINO_NANO") (libsource (lib "") (part "ARDUINO_NANO")))
    (comp (ref "U18") (value "Arduino Uno") (libsource (lib "") (part "Arduino Uno")))
    (comp (ref "NODE6") (value "NODE_MCU_V3_ESP8266") (libsource (lib "") (part "NODE_MCU_V3_ESP8266")))
    (comp (ref "U19") (value "ARDUINO_NANO") (libsource (lib "") (part "ARDUINO_NANO")))
    (comp (ref "U20") (value "Arduino Uno") (libsource (lib "") (part "Arduino Uno")))
    (comp (ref "U21") (value "0.91 inch OLED module") (libsource (lib "") (part "0.91 inch OLED module")))
    (comp (ref "U22")
      (value "0.91\" 128x32 OLED Display Dawid")
      (libsource (lib "") (part "0.91{dblquote} 128x32 OLED Display Dawid"))
    )
    (comp (ref "U23") (value "0.96 inch oled display") (libsource (lib "") (part "0.96 inch oled display")))
    (comp (ref "LCD1")
      (value "LCD1602")
      (fields
        (field (name "Manufacturer Part") "LCM1602K-NSW-BBW")
        (field (name "Manufacturer") "LONTECH(厦门龙特)")
      )
      (libsource (lib "") (part "LCD1602"))
    )
    (comp (ref "NODE7") (value "NODE_MCU_V3_ESP8266") (libsource (lib "") (part "NODE_MCU_V3_ESP8266")))
    (comp (ref "U24") (value "ARDUINO_NANO") (libsource (lib "") (part "ARDUINO_NANO")))
    (comp (ref "U25") (value "Arduino Uno") (libsource (lib "") (part "Arduino Uno")))
    (comp (ref "U26") (value "10k Potentiometer") (libsource (lib "") (part "10k Potentiometer")))
    (comp (ref "NODE8") (value "NODE_MCU_V3_ESP8266") (libsource (lib "") (part "NODE_MCU_V3_ESP8266")))
    (comp (ref "U27") (value "Arduino Uno") (libsource (lib "") (part "Arduino Uno")))
    (comp (ref "U28") (value "ARDUINO_NANO") (libsource (lib "") (part "ARDUINO_NANO")))
    (comp (ref "U29") (value "I2C LCD 16X2") (libsource (lib "") (part "I2C LCD 16X2")))
  )
  (nets
    (net (code "1") (name "A0") (class "Default")
      (node (ref "H1") (pin "1") (pinfunction "A0_1") (pintype "unspecified"))
      (node (ref "NODE3") (pin "1") (pinfunction "A0_1") (pintype "unspecified"))
      (node (ref "S1") (pin "4") (pinfunction "A0_4") (pintype "unspecified"))
      (node (ref "U10") (pin "24") (pinfunction "14/A0/PC0_24") (pintype "unspecified"))
      (node (ref "U9") (pin "19") (pinfunction "A0_19") (pintype "unspecified"))
    )
    (net (code "2") (name "AD0") (class "Default")
      (node (ref "U12") (pin "2") (pinfunction "AD0_2") (pintype "unspecified"))
      (node (ref "U14") (pin "2") (pinfunction "ADO_2") (pintype "unspecified"))
    )
    (net (code "3") (name "ADDR") (class "Default")
      (node (ref "NODE4") (pin "27") (pinfunction "D3_27") (pintype "unspecified"))
      (node (ref "U11") (pin "5") (pinfunction "5_5") (pintype "unspecified"))
      (node (ref "U13") (pin "5") (pinfunction "ADD*_5") (pintype "unspecified"))
      (node (ref "U15") (pin "22") (pinfunction "A3_22") (pintype "unspecified"))
      (node (ref "U16") (pin "21") (pinfunction "17/A3/PC3_21") (pintype "unspecified"))
    )
    (net (code "4") (name "AOUT") (class "Default")
      (node (ref "NODE2") (pin "1") (pinfunction "A0_1") (pintype "unspecified"))
      (node (ref "U4") (pin "3") (pinfunction "AOUT_3") (pintype "unspecified"))
      (node (ref "U6") (pin "19") (pinfunction "A0_19") (pintype "unspecified"))
      (node (ref "U7") (pin "24") (pinfunction "14/A0/PC0_24") (pintype "unspecified"))
      (node (ref "U8") (pin "3") (pinfunction "AUOT_3") (pintype "unspecified"))
    )
    (net (code "5") (name "D0") (class "Default")
      (node (ref "H1") (pin "2") (pinfunction "D0_2") (pintype "unspecified"))
      (node (ref "NODE3") (pin "20") (pinfunction "D8_20") (pintype "unspecified"))
      (node (ref "S1") (pin "3") (pinfunction "D0_3") (pintype "unspecified"))
      (node (ref "U10") (pin "9") (pinfunction "PB0/8_9") (pintype "unspecified"))
      (node (ref "U9") (pin "11") (pinfunction "D8_11") (pintype "unspecified"))
    )
    (net (code "6") (name "D4") (class "Default")
      (node (ref "LCD1") (pin "11") (pinfunction "DB4_11") (pintype "unspecified"))
      (node (ref "NODE7") (pin "26") (pinfunction "D4_26") (pintype "unspecified"))
      (node (ref "U24") (pin "21") (pinfunction "A2_21") (pintype "unspecified"))
      (node (ref "U25") (pin "22") (pinfunction "16/A2/PC2_22") (pintype "unspecified"))
    )
    (net (code "7") (name "D5") (class "Default")
      (node (ref "LCD1") (pin "12") (pinfunction "DB5_12") (pintype "unspecified"))
      (node (ref "NODE7") (pin "23") (pinfunction "D5_23") (pintype "unspecified"))
      (node (ref "U24") (pin "22") (pinfunction "A3_22") (pintype "unspecified"))
      (node (ref "U25") (pin "21") (pinfunction "17/A3/PC3_21") (pintype "unspecified"))
    )
    (net (code "8") (name "D6") (class "Default")
      (node (ref "LCD1") (pin "13") (pinfunction "DB6_13") (pintype "unspecified"))
      (node (ref "NODE7") (pin "22") (pinfunction "D6_22") (pintype "unspecified"))
      (node (ref "U24") (pin "23") (pinfunction "A4_23") (pintype "unspecified"))
      (node (ref "U25") (pin "20") (pinfunction "18/A4/PC4/SDA_20") (pintype "unspecified"))
    )
    (net (code "9") (name "D7") (class "Default")
      (node (ref "LCD1") (pin "14") (pinfunction "DB7_14") (pintype "unspecified"))
      (node (ref "NODE7") (pin "21") (pinfunction "D7_21") (pintype "unspecified"))
      (node (ref "U24") (pin "24") (pinfunction "A5_24") (pintype "unspecified"))
      (node (ref "U25") (pin "19") (pinfunction "19/A5/PC5/SCL_19") (pintype "unspecified"))
    )
    (net (code "10") (name "DATA") (class "Default")
      (node (ref "DD1") (pin "2") (pinfunction "DATA_2") (pintype "unspecified"))
      (node (ref "NODE1") (pin "20") (pinfunction "D8_20") (pintype "unspecified"))
      (node (ref "U1") (pin "7") (pinfunction "PWR/PD6/6_7") (pintype "unspecified"))
      (node (ref "U2") (pin "6") (pinfunction "D3_6") (pintype "unspecified"))
      (node (ref "U3") (pin "2") (pinfunction "DATA_2") (pintype "unspecified"))
    )
    (net (code "11") (name "E") (class "Default")
      (node (ref "LCD1") (pin "6") (pinfunction "E_6") (pintype "unspecified"))
      (node (ref "NODE7") (pin "27") (pinfunction "D3_27") (pintype "unspecified"))
      (node (ref "U24") (pin "20") (pinfunction "A1_20") (pintype "unspecified"))
      (node (ref "U25") (pin "23") (pinfunction "15/A1/PC1_23") (pintype "unspecified"))
    )
    (net (code "12") (name "GND") (class "Default")
      (node (ref "DD1") (pin "4") (pinfunction "GND_4") (pintype "unspecified"))
      (node (ref "H1") (pin "3") (pinfunction "GND_3") (pintype "unspecified"))
      (node (ref "J2") (pin "14") (pinfunction "GND_14") (pintype "unspecified"))
      (node (ref "LCD1") (pin "1") (pinfunction "VSS_1") (pintype "unspecified"))
      (node (ref "LCD1") (pin "16") (pinfunction "BLK_16") (pintype "unspecified"))
      (node (ref "LCD1") (pin "5") (pinfunction "R/W_5") (pintype "unspecified"))
      (node (ref "NODE1") (pin "2") (pinfunction "GND_2") (pintype "unspecified"))
      (node (ref "NODE2") (pin "2") (pinfunction "GND_2") (pintype "unspecified"))
      (node (ref "NODE3") (pin "2") (pinfunction "GND_2") (pintype "unspecified"))
      (node (ref "NODE4") (pin "24") (pinfunction "GND_24") (pintype "unspecified"))
      (node (ref "NODE5") (pin "17") (pinfunction "GND_17") (pintype "unspecified"))
      (node (ref "NODE6") (pin "24") (pinfunction "GND_24") (pintype "unspecified"))
      (node (ref "NODE7") (pin "2") (pinfunction "GND_2") (pintype "unspecified"))
      (node (ref "NODE8") (pin "2") (pinfunction "GND_2") (pintype "unspecified"))
      (node (ref "P1") (pin "2") (pinfunction "GND_2") (pintype "input"))
      (node (ref "P2") (pin "1") (pinfunction "GND_1") (pintype "input"))
      (node (ref "S1") (pin "2") (pinfunction "GND_2") (pintype "unspecified"))
      (node (ref "U1") (pin "26") (pinfunction "GND1_26") (pintype "passive"))
      (node (ref "U10") (pin "26") (pinfunction "GND1_26") (pintype "passive"))
      (node (ref "U11") (pin "2") (pinfunction "2_2") (pintype "unspecified"))
      (node (ref "U12") (pin "1") (pinfunction "GND_1") (pintype "unspecified"))
      (node (ref "U13") (pin "2") (pinfunction "GND_2") (pintype "unspecified"))
      (node (ref "U14") (pin "1") (pinfunction "GND_1") (pintype "unspecified"))
      (node (ref "U15") (pin "29") (pinfunction "GND_29") (pintype "unspecified"))
      (node (ref "U16") (pin "26") (pinfunction "GND1_26") (pintype "passive"))
      (node (ref "U17") (pin "29") (pinfunction "GND_29") (pintype "unspecified"))
      (node (ref "U18") (pin "26") (pinfunction "GND1_26") (pintype "passive"))
      (node (ref "U19") (pin "29") (pinfunction "GND_29") (pintype "unspecified"))
      (node (ref "U2") (pin "4") (pinfunction "GND_4") (pintype "unspecified"))
      (node (ref "U20") (pin "26") (pinfunction "GND1_26") (pintype "passive"))
      (node (ref "U21") (pin "1") (pinfunction "GND_1") (pintype "unspecified"))
      (node (ref "U22") (pin "4") (pinfunction "GND_4") (pintype "unspecified"))
      (node (ref "U23") (pin "GND") (pinfunction "1_GND") (pintype "unspecified"))
      (node (ref "U24") (pin "29") (pinfunction "GND_29") (pintype "unspecified"))
      (node (ref "U25") (pin "26") (pinfunction "GND1_26") (pintype "passive"))
      (node (ref "U26") (pin "3") (pinfunction "3_3") (pintype "unspecified"))
      (node (ref "U27") (pin "26") (pinfunction "GND1_26") (pintype "passive"))
      (node (ref "U28") (pin "4") (pinfunction "GND_4") (pintype "unspecified"))
      (node (ref "U29") (pin "1") (pinfunction "GND_1") (pintype "unspecified"))
      (node (ref "U3") (pin "3") (pinfunction "GND_3") (pintype "unspecified"))
      (node (ref "U4") (pin "1") (pinfunction "GND_1") (pintype "unspecified"))
      (node (ref "U6") (pin "4") (pinfunction "GND_4") (pintype "unspecified"))
      (node (ref "U7") (pin "26") (pinfunction "GND1_26") (pintype "passive"))
      (node (ref "U8") (pin "1") (pinfunction "GND_1") (pintype "unspecified"))
      (node (ref "U9") (pin "4") (pinfunction "GND_4") (pintype "unspecified"))
    )
    (net (code "13") (name "Net-(LCD1-VO)") (class "Default")
      (node (ref "LCD1") (pin "3") (pinfunction "VO_3") (pintype "unspecified"))
      (node (ref "U26") (pin "1") (pinfunction "1_1") (pintype "unspecified"))
    )
    (net (code "14") (name "RS") (class "Default")
      (node (ref "LCD1") (pin "4") (pinfunction "RS_4") (pintype "unspecified"))
      (node (ref "NODE7") (pin "28") (pinfunction "D2_28") (pintype "unspecified"))
      (node (ref "U24") (pin "19") (pinfunction "A0_19") (pintype "unspecified"))
      (node (ref "U25") (pin "24") (pinfunction "14/A0/PC0_24") (pintype "unspecified"))
    )
    (net (code "15") (name "SCL") (class "Default")
      (node (ref "NODE4") (pin "29") (pinfunction "D1_29") (pintype "unspecified"))
      (node (ref "NODE6") (pin "29") (pinfunction "D1_29") (pintype "unspecified"))
      (node (ref "NODE8") (pin "29") (pinfunction "D1_29") (pintype "unspecified"))
      (node (ref "U11") (pin "3") (pinfunction "3_3") (pintype "unspecified"))
      (node (ref "U12") (pin "4") (pinfunction "SCL_4") (pintype "unspecified"))
      (node (ref "U13") (pin "3") (pinfunction "SCL_3") (pintype "unspecified"))
      (node (ref "U14") (pin "4") (pinfunction "SCL_4") (pintype "unspecified"))
      (node (ref "U15") (pin "24") (pinfunction "A5_24") (pintype "unspecified"))
      (node (ref "U16") (pin "19") (pinfunction "19/A5/PC5/SCL_19") (pintype "unspecified"))
      (node (ref "U19") (pin "24") (pinfunction "A5_24") (pintype "unspecified"))
      (node (ref "U20") (pin "19") (pinfunction "19/A5/PC5/SCL_19") (pintype "unspecified"))
      (node (ref "U21") (pin "3") (pinfunction "SCL_3") (pintype "unspecified"))
      (node (ref "U22") (pin "2") (pinfunction "SCL_2") (pintype "unspecified"))
      (node (ref "U23") (pin "SCL") (pinfunction "3_SCL") (pintype "unspecified"))
      (node (ref "U27") (pin "19") (pinfunction "19/A5/PC5/SCL_19") (pintype "unspecified"))
      (node (ref "U28") (pin "24") (pinfunction "A5_24") (pintype "unspecified"))
      (node (ref "U29") (pin "3") (pinfunction "SCL_3") (pintype "unspecified"))
    )
    (net (code "16") (name "SDA") (class "Default")
      (node (ref "NODE4") (pin "28") (pinfunction "D2_28") (pintype "unspecified"))
      (node (ref "NODE6") (pin "28") (pinfunction "D2_28") (pintype "unspecified"))
      (node (ref "NODE8") (pin "28") (pinfunction "D2_28") (pintype "unspecified"))
      (node (ref "U11") (pin "4") (pinfunction "4_4") (pintype "unspecified"))
      (node (ref "U12") (pin "3") (pinfunction "SDA_3") (pintype "unspecified"))
      (node (ref "U13") (pin "4") (pinfunction "SDA_4") (pintype "unspecified"))
      (node (ref "U14") (pin "3") (pinfunction "SDA_3") (pintype "unspecified"))
      (node (ref "U15") (pin "23") (pinfunction "A4_23") (pintype "unspecified"))
      (node (ref "U16") (pin "20") (pinfunction "18/A4/PC4/SDA_20") (pintype "unspecified"))
      (node (ref "U19") (pin "23") (pinfunction "A4_23") (pintype "unspecified"))
      (node (ref "U20") (pin "20") (pinfunction "18/A4/PC4/SDA_20") (pintype "unspecified"))
      (node (ref "U21") (pin "4") (pinfunction "SDA_4") (pintype "unspecified"))
      (node (ref "U22") (pin "1") (pinfunction "SDA_1") (pintype "unspecified"))
      (node (ref "U23") (pin "SDA") (pinfunction "4_SDA") (pintype "unspecified"))
      (node (ref "U27") (pin "20") (pinfunction "18/A4/PC4/SDA_20") (pintype "unspecified"))
      (node (ref "U28") (pin "23") (pinfunction "A4_23") (pintype "unspecified"))
      (node (ref "U29") (pin "4") (pinfunction "SDA_4") (pintype "unspecified"))
    )
    (net (code "17") (name "SIG") (class "Default")
      (node (ref "J2") (pin "15") (pinfunction "SIG_15") (pintype "unspecified"))
      (node (ref "NODE5") (pin "20") (pinfunction "D8_20") (pintype "unspecified"))
      (node (ref "P1") (pin "3") (pinfunction "SIG_3") (pintype "input"))
      (node (ref "P2") (pin "3") (pinfunction "SIG_3") (pintype "input"))
      (node (ref "U17") (pin "11") (pinfunction "D8_11") (pintype "unspecified"))
      (node (ref "U18") (pin "9") (pinfunction "PB0/8_9") (pintype "unspecified"))
    )
    (net (code "18") (name "VCC") (class "Default")
      (node (ref "DD1") (pin "1") (pinfunction "VDD_1") (pintype "unspecified"))
      (node (ref "H1") (pin "4") (pinfunction "VCC_4") (pintype "unspecified"))
      (node (ref "J2") (pin "13") (pinfunction "Vcc_13") (pintype "unspecified"))
      (node (ref "LCD1") (pin "15") (pinfunction "BLA_15") (pintype "unspecified"))
      (node (ref "LCD1") (pin "2") (pinfunction "VCC_2") (pintype "unspecified"))
      (node (ref "NODE1") (pin "16") (pinfunction "3V3_16") (pintype "unspecified"))
      (node (ref "NODE2") (pin "16") (pinfunction "3V3_16") (pintype "unspecified"))
      (node (ref "NODE3") (pin "11") (pinfunction "3V3_11") (pintype "unspecified"))
      (node (ref "NODE4") (pin "11") (pinfunction "3V3_11") (pintype "unspecified"))
      (node (ref "NODE5") (pin "16") (pinfunction "3V3_16") (pintype "unspecified"))
      (node (ref "NODE6") (pin "16") (pinfunction "3V3_16") (pintype "unspecified"))
      (node (ref "NODE7") (pin "11") (pinfunction "3V3_11") (pintype "unspecified"))
      (node (ref "NODE8") (pin "16") (pinfunction "3V3_16") (pintype "unspecified"))
      (node (ref "P1") (pin "1") (pinfunction "VCC_1") (pintype "input"))
      (node (ref "P2") (pin "2") (pinfunction "VCC_2") (pintype "input"))
      (node (ref "S1") (pin "1") (pinfunction "VCC_1") (pintype "unspecified"))
      (node (ref "U1") (pin "28") (pinfunction "5V_28") (pintype "passive"))
      (node (ref "U10") (pin "28") (pinfunction "5V_28") (pintype "passive"))
      (node (ref "U11") (pin "1") (pinfunction "1_1") (pintype "unspecified"))
      (node (ref "U12") (pin "5") (pinfunction "VCC_5") (pintype "unspecified"))
      (node (ref "U13") (pin "1") (pinfunction "VCC_1") (pintype "unspecified"))
      (node (ref "U14") (pin "5") (pinfunction "VCC_5") (pintype "unspecified"))
      (node (ref "U15") (pin "27") (pinfunction "+5V_27") (pintype "unspecified"))
      (node (ref "U16") (pin "28") (pinfunction "5V_28") (pintype "passive"))
      (node (ref "U17") (pin "27") (pinfunction "+5V_27") (pintype "unspecified"))
      (node (ref "U18") (pin "28") (pinfunction "5V_28") (pintype "passive"))
      (node (ref "U19") (pin "27") (pinfunction "+5V_27") (pintype "unspecified"))
      (node (ref "U2") (pin "27") (pinfunction "+5V_27") (pintype "unspecified"))
      (node (ref "U20") (pin "28") (pinfunction "5V_28") (pintype "passive"))
      (node (ref "U21") (pin "2") (pinfunction "VCC_2") (pintype "unspecified"))
      (node (ref "U22") (pin "3") (pinfunction "VCC_3") (pintype "unspecified"))
      (node (ref "U23") (pin "VCC") (pinfunction "2_VCC") (pintype "unspecified"))
      (node (ref "U24") (pin "27") (pinfunction "+5V_27") (pintype "unspecified"))
      (node (ref "U25") (pin "28") (pinfunction "5V_28") (pintype "passive"))
      (node (ref "U26") (pin "2") (pinfunction "2_2") (pintype "unspecified"))
      (node (ref "U27") (pin "28") (pinfunction "5V_28") (pintype "passive"))
      (node (ref "U28") (pin "27") (pinfunction "+5V_27") (pintype "unspecified"))
      (node (ref "U29") (pin "2") (pinfunction "Vcc_2") (pintype "unspecified"))
      (node (ref "U3") (pin "1") (pinfunction "VCC_1") (pintype "unspecified"))
      (node (ref "U4") (pin "2") (pinfunction "VCC_2") (pintype "unspecified"))
      (node (ref "U6") (pin "27") (pinfunction "+5V_27") (pintype "unspecified"))
      (node (ref "U7") (pin "28") (pinfunction "5V_28") (pintype "passive"))
      (node (ref "U8") (pin "2") (pinfunction "VCC_2") (pintype "unspecified"))
      (node (ref "U9") (pin "27") (pinfunction "+5V_27") (pintype "unspecified"))
    )
    (net (code "19") (name "unconnected-(DD1-NC-Pad3)") (class "Default")
      (node (ref "DD1") (pin "3") (pinfunction "NC_3") (pintype "unspecified"))
    )
    (net (code "20") (name "unconnected-(J2-COM-Pad2)") (class "Default")
      (node (ref "J2") (pin "2") (pinfunction "COM_2") (pintype "unspecified"))
    )
    (net (code "21") (name "unconnected-(J2-NC-Pad3)") (class "Default")
      (node (ref "J2") (pin "3") (pinfunction "NC_3") (pintype "unspecified"))
    )
    (net (code "22") (name "unconnected-(J2-NO-Pad1)") (class "Default")
      (node (ref "J2") (pin "1") (pinfunction "NO_1") (pintype "unspecified"))
    )
    (net (code "23") (name "unconnected-(LCD1-DB0-Pad7)") (class "Default")
      (node (ref "LCD1") (pin "7") (pinfunction "DB0_7") (pintype "unspecified"))
    )
    (net (code "24") (name "unconnected-(LCD1-DB1-Pad8)") (class "Default")
      (node (ref "LCD1") (pin "8") (pinfunction "DB1_8") (pintype "unspecified"))
    )
    (net (code "25") (name "unconnected-(LCD1-DB2-Pad9)") (class "Default")
      (node (ref "LCD1") (pin "9") (pinfunction "DB2_9") (pintype "unspecified"))
    )
    (net (code "26") (name "unconnected-(LCD1-DB3-Pad10)") (class "Default")
      (node (ref "LCD1") (pin "10") (pinfunction "DB3_10") (pintype "unspecified"))
    )
    (net (code "27") (name "unconnected-(NODE1-3V3-Pad11)") (class "Default")
      (node (ref "NODE1") (pin "11") (pinfunction "3V3_11") (pintype "unspecified"))
    )
    (net (code "28") (name "unconnected-(NODE1-3V3-Pad25)") (class "Default")
      (node (ref "NODE1") (pin "25") (pinfunction "3V3_25") (pintype "unspecified"))
    )
    (net (code "29") (name "unconnected-(NODE1-A0-Pad1)") (class "Default")
      (node (ref "NODE1") (pin "1") (pinfunction "A0_1") (pintype "unspecified"))
    )
    (net (code "30") (name "unconnected-(NODE1-D0-Pad30)") (class "Default")
      (node (ref "NODE1") (pin "30") (pinfunction "D0_30") (pintype "unspecified"))
    )
    (net (code "31") (name "unconnected-(NODE1-D1-Pad29)") (class "Default")
      (node (ref "NODE1") (pin "29") (pinfunction "D1_29") (pintype "unspecified"))
    )
    (net (code "32") (name "unconnected-(NODE1-D2-Pad28)") (class "Default")
      (node (ref "NODE1") (pin "28") (pinfunction "D2_28") (pintype "unspecified"))
    )
    (net (code "33") (name "unconnected-(NODE1-D3-Pad27)") (class "Default")
      (node (ref "NODE1") (pin "27") (pinfunction "D3_27") (pintype "unspecified"))
    )
    (net (code "34") (name "unconnected-(NODE1-D4-Pad26)") (class "Default")
      (node (ref "NODE1") (pin "26") (pinfunction "D4_26") (pintype "unspecified"))
    )
    (net (code "35") (name "unconnected-(NODE1-D5-Pad23)") (class "Default")
      (node (ref "NODE1") (pin "23") (pinfunction "D5_23") (pintype "unspecified"))
    )
    (net (code "36") (name "unconnected-(NODE1-D6-Pad22)") (class "Default")
      (node (ref "NODE1") (pin "22") (pinfunction "D6_22") (pintype "unspecified"))
    )
    (net (code "37") (name "unconnected-(NODE1-D7-Pad21)") (class "Default")
      (node (ref "NODE1") (pin "21") (pinfunction "D7_21") (pintype "unspecified"))
    )
    (net (code "38") (name "unconnected-(NODE1-EN-Pad12)") (class "Default")
      (node (ref "NODE1") (pin "12") (pinfunction "EN_12") (pintype "unspecified"))
    )
    (net (code "39") (name "unconnected-(NODE1-GND-Pad10)") (class "Default")
      (node (ref "NODE1") (pin "10") (pinfunction "GND_10") (pintype "unspecified"))
    )
    (net (code "40") (name "unconnected-(NODE1-GND-Pad14)") (class "Default")
      (node (ref "NODE1") (pin "14") (pinfunction "GND_14") (pintype "unspecified"))
    )
    (net (code "41") (name "unconnected-(NODE1-GND-Pad17)") (class "Default")
      (node (ref "NODE1") (pin "17") (pinfunction "GND_17") (pintype "unspecified"))
    )
    (net (code "42") (name "unconnected-(NODE1-GND-Pad24)") (class "Default")
      (node (ref "NODE1") (pin "24") (pinfunction "GND_24") (pintype "unspecified"))
    )
    (net (code "43") (name "unconnected-(NODE1-RST-Pad13)") (class "Default")
      (node (ref "NODE1") (pin "13") (pinfunction "RST_13") (pintype "unspecified"))
    )
    (net (code "44") (name "unconnected-(NODE1-RX-Pad19)") (class "Default")
      (node (ref "NODE1") (pin "19") (pinfunction "RX_19") (pintype "unspecified"))
    )
    (net (code "45") (name "unconnected-(NODE1-S1-Pad6)") (class "Default")
      (node (ref "NODE1") (pin "6") (pinfunction "S1_6") (pintype "unspecified"))
    )
    (net (code "46") (name "unconnected-(NODE1-S2-Pad5)") (class "Default")
      (node (ref "NODE1") (pin "5") (pinfunction "S2_5") (pintype "unspecified"))
    )
    (net (code "47") (name "unconnected-(NODE1-S3-Pad4)") (class "Default")
      (node (ref "NODE1") (pin "4") (pinfunction "S3_4") (pintype "unspecified"))
    )
    (net (code "48") (name "unconnected-(NODE1-SC-Pad7)") (class "Default")
      (node (ref "NODE1") (pin "7") (pinfunction "SC_7") (pintype "unspecified"))
    )
    (net (code "49") (name "unconnected-(NODE1-SK-Pad9)") (class "Default")
      (node (ref "NODE1") (pin "9") (pinfunction "SK_9") (pintype "unspecified"))
    )
    (net (code "50") (name "unconnected-(NODE1-SO-Pad8)") (class "Default")
      (node (ref "NODE1") (pin "8") (pinfunction "SO_8") (pintype "unspecified"))
    )
    (net (code "51") (name "unconnected-(NODE1-TX-Pad18)") (class "Default")
      (node (ref "NODE1") (pin "18") (pinfunction "TX_18") (pintype "unspecified"))
    )
    (net (code "52") (name "unconnected-(NODE1-VU-Pad3)") (class "Default")
      (node (ref "NODE1") (pin "3") (pinfunction "VU_3") (pintype "unspecified"))
    )
    (net (code "53") (name "unconnected-(NODE1-Vin-Pad15)") (class "Default")
      (node (ref "NODE1") (pin "15") (pinfunction "Vin_15") (pintype "unspecified"))
    )
    (net (code "54") (name "unconnected-(NODE2-3V3-Pad11)") (class "Default")
      (node (ref "NODE2") (pin "11") (pinfunction "3V3_11") (pintype "unspecified"))
    )
    (net (code "55") (name "unconnected-(NODE2-3V3-Pad25)") (class "Default")
      (node (ref "NODE2") (pin "25") (pinfunction "3V3_25") (pintype "unspecified"))
    )
    (net (code "56") (name "unconnected-(NODE2-D0-Pad30)") (class "Default")
      (node (ref "NODE2") (pin "30") (pinfunction "D0_30") (pintype "unspecified"))
    )
    (net (code "57") (name "unconnected-(NODE2-D1-Pad29)") (class "Default")
      (node (ref "NODE2") (pin "29") (pinfunction "D1_29") (pintype "unspecified"))
    )
    (net (code "58") (name "unconnected-(NODE2-D2-Pad28)") (class "Default")
      (node (ref "NODE2") (pin "28") (pinfunction "D2_28") (pintype "unspecified"))
    )
    (net (code "59") (name "unconnected-(NODE2-D3-Pad27)") (class "Default")
      (node (ref "NODE2") (pin "27") (pinfunction "D3_27") (pintype "unspecified"))
    )
    (net (code "60") (name "unconnected-(NODE2-D4-Pad26)") (class "Default")
      (node (ref "NODE2") (pin "26") (pinfunction "D4_26") (pintype "unspecified"))
    )
    (net (code "61") (name "unconnected-(NODE2-D5-Pad23)") (class "Default")
      (node (ref "NODE2") (pin "23") (pinfunction "D5_23") (pintype "unspecified"))
    )
    (net (code "62") (name "unconnected-(NODE2-D6-Pad22)") (class "Default")
      (node (ref "NODE2") (pin "22") (pinfunction "D6_22") (pintype "unspecified"))
    )
    (net (code "63") (name "unconnected-(NODE2-D7-Pad21)") (class "Default")
      (node (ref "NODE2") (pin "21") (pinfunction "D7_21") (pintype "unspecified"))
    )
    (net (code "64") (name "unconnected-(NODE2-D8-Pad20)") (class "Default")
      (node (ref "NODE2") (pin "20") (pinfunction "D8_20") (pintype "unspecified"))
    )
    (net (code "65") (name "unconnected-(NODE2-EN-Pad12)") (class "Default")
      (node (ref "NODE2") (pin "12") (pinfunction "EN_12") (pintype "unspecified"))
    )
    (net (code "66") (name "unconnected-(NODE2-GND-Pad10)") (class "Default")
      (node (ref "NODE2") (pin "10") (pinfunction "GND_10") (pintype "unspecified"))
    )
    (net (code "67") (name "unconnected-(NODE2-GND-Pad14)") (class "Default")
      (node (ref "NODE2") (pin "14") (pinfunction "GND_14") (pintype "unspecified"))
    )
    (net (code "68") (name "unconnected-(NODE2-GND-Pad17)") (class "Default")
      (node (ref "NODE2") (pin "17") (pinfunction "GND_17") (pintype "unspecified"))
    )
    (net (code "69") (name "unconnected-(NODE2-GND-Pad24)") (class "Default")
      (node (ref "NODE2") (pin "24") (pinfunction "GND_24") (pintype "unspecified"))
    )
    (net (code "70") (name "unconnected-(NODE2-RST-Pad13)") (class "Default")
      (node (ref "NODE2") (pin "13") (pinfunction "RST_13") (pintype "unspecified"))
    )
    (net (code "71") (name "unconnected-(NODE2-RX-Pad19)") (class "Default")
      (node (ref "NODE2") (pin "19") (pinfunction "RX_19") (pintype "unspecified"))
    )
    (net (code "72") (name "unconnected-(NODE2-S1-Pad6)") (class "Default")
      (node (ref "NODE2") (pin "6") (pinfunction "S1_6") (pintype "unspecified"))
    )
    (net (code "73") (name "unconnected-(NODE2-S2-Pad5)") (class "Default")
      (node (ref "NODE2") (pin "5") (pinfunction "S2_5") (pintype "unspecified"))
    )
    (net (code "74") (name "unconnected-(NODE2-S3-Pad4)") (class "Default")
      (node (ref "NODE2") (pin "4") (pinfunction "S3_4") (pintype "unspecified"))
    )
    (net (code "75") (name "unconnected-(NODE2-SC-Pad7)") (class "Default")
      (node (ref "NODE2") (pin "7") (pinfunction "SC_7") (pintype "unspecified"))
    )
    (net (code "76") (name "unconnected-(NODE2-SK-Pad9)") (class "Default")
      (node (ref "NODE2") (pin "9") (pinfunction "SK_9") (pintype "unspecified"))
    )
    (net (code "77") (name "unconnected-(NODE2-SO-Pad8)") (class "Default")
      (node (ref "NODE2") (pin "8") (pinfunction "SO_8") (pintype "unspecified"))
    )
    (net (code "78") (name "unconnected-(NODE2-TX-Pad18)") (class "Default")
      (node (ref "NODE2") (pin "18") (pinfunction "TX_18") (pintype "unspecified"))
    )
    (net (code "79") (name "unconnected-(NODE2-VU-Pad3)") (class "Default")
      (node (ref "NODE2") (pin "3") (pinfunction "VU_3") (pintype "unspecified"))
    )
    (net (code "80") (name "unconnected-(NODE2-Vin-Pad15)") (class "Default")
      (node (ref "NODE2") (pin "15") (pinfunction "Vin_15") (pintype "unspecified"))
    )
    (net (code "81") (name "unconnected-(NODE3-3V3-Pad16)") (class "Default")
      (node (ref "NODE3") (pin "16") (pinfunction "3V3_16") (pintype "unspecified"))
    )
    (net (code "82") (name "unconnected-(NODE3-3V3-Pad25)") (class "Default")
      (node (ref "NODE3") (pin "25") (pinfunction "3V3_25") (pintype "unspecified"))
    )
    (net (code "83") (name "unconnected-(NODE3-D0-Pad30)") (class "Default")
      (node (ref "NODE3") (pin "30") (pinfunction "D0_30") (pintype "unspecified"))
    )
    (net (code "84") (name "unconnected-(NODE3-D1-Pad29)") (class "Default")
      (node (ref "NODE3") (pin "29") (pinfunction "D1_29") (pintype "unspecified"))
    )
    (net (code "85") (name "unconnected-(NODE3-D2-Pad28)") (class "Default")
      (node (ref "NODE3") (pin "28") (pinfunction "D2_28") (pintype "unspecified"))
    )
    (net (code "86") (name "unconnected-(NODE3-D3-Pad27)") (class "Default")
      (node (ref "NODE3") (pin "27") (pinfunction "D3_27") (pintype "unspecified"))
    )
    (net (code "87") (name "unconnected-(NODE3-D4-Pad26)") (class "Default")
      (node (ref "NODE3") (pin "26") (pinfunction "D4_26") (pintype "unspecified"))
    )
    (net (code "88") (name "unconnected-(NODE3-D5-Pad23)") (class "Default")
      (node (ref "NODE3") (pin "23") (pinfunction "D5_23") (pintype "unspecified"))
    )
    (net (code "89") (name "unconnected-(NODE3-D6-Pad22)") (class "Default")
      (node (ref "NODE3") (pin "22") (pinfunction "D6_22") (pintype "unspecified"))
    )
    (net (code "90") (name "unconnected-(NODE3-D7-Pad21)") (class "Default")
      (node (ref "NODE3") (pin "21") (pinfunction "D7_21") (pintype "unspecified"))
    )
    (net (code "91") (name "unconnected-(NODE3-EN-Pad12)") (class "Default")
      (node (ref "NODE3") (pin "12") (pinfunction "EN_12") (pintype "unspecified"))
    )
    (net (code "92") (name "unconnected-(NODE3-GND-Pad10)") (class "Default")
      (node (ref "NODE3") (pin "10") (pinfunction "GND_10") (pintype "unspecified"))
    )
    (net (code "93") (name "unconnected-(NODE3-GND-Pad14)") (class "Default")
      (node (ref "NODE3") (pin "14") (pinfunction "GND_14") (pintype "unspecified"))
    )
    (net (code "94") (name "unconnected-(NODE3-GND-Pad17)") (class "Default")
      (node (ref "NODE3") (pin "17") (pinfunction "GND_17") (pintype "unspecified"))
    )
    (net (code "95") (name "unconnected-(NODE3-GND-Pad24)") (class "Default")
      (node (ref "NODE3") (pin "24") (pinfunction "GND_24") (pintype "unspecified"))
    )
    (net (code "96") (name "unconnected-(NODE3-RST-Pad13)") (class "Default")
      (node (ref "NODE3") (pin "13") (pinfunction "RST_13") (pintype "unspecified"))
    )
    (net (code "97") (name "unconnected-(NODE3-RX-Pad19)") (class "Default")
      (node (ref "NODE3") (pin "19") (pinfunction "RX_19") (pintype "unspecified"))
    )
    (net (code "98") (name "unconnected-(NODE3-S1-Pad6)") (class "Default")
      (node (ref "NODE3") (pin "6") (pinfunction "S1_6") (pintype "unspecified"))
    )
    (net (code "99") (name "unconnected-(NODE3-S2-Pad5)") (class "Default")
      (node (ref "NODE3") (pin "5") (pinfunction "S2_5") (pintype "unspecified"))
    )
    (net (code "100") (name "unconnected-(NODE3-S3-Pad4)") (class "Default")
      (node (ref "NODE3") (pin "4") (pinfunction "S3_4") (pintype "unspecified"))
    )
    (net (code "101") (name "unconnected-(NODE3-SC-Pad7)") (class "Default")
      (node (ref "NODE3") (pin "7") (pinfunction "SC_7") (pintype "unspecified"))
    )
    (net (code "102") (name "unconnected-(NODE3-SK-Pad9)") (class "Default")
      (node (ref "NODE3") (pin "9") (pinfunction "SK_9") (pintype "unspecified"))
    )
    (net (code "103") (name "unconnected-(NODE3-SO-Pad8)") (class "Default")
      (node (ref "NODE3") (pin "8") (pinfunction "SO_8") (pintype "unspecified"))
    )
    (net (code "104") (name "unconnected-(NODE3-TX-Pad18)") (class "Default")
      (node (ref "NODE3") (pin "18") (pinfunction "TX_18") (pintype "unspecified"))
    )
    (net (code "105") (name "unconnected-(NODE3-VU-Pad3)") (class "Default")
      (node (ref "NODE3") (pin "3") (pinfunction "VU_3") (pintype "unspecified"))
    )
    (net (code "106") (name "unconnected-(NODE3-Vin-Pad15)") (class "Default")
      (node (ref "NODE3") (pin "15") (pinfunction "Vin_15") (pintype "unspecified"))
    )
    (net (code "107") (name "unconnected-(NODE4-3V3-Pad16)") (class "Default")
      (node (ref "NODE4") (pin "16") (pinfunction "3V3_16") (pintype "unspecified"))
    )
    (net (code "108") (name "unconnected-(NODE4-3V3-Pad25)") (class "Default")
      (node (ref "NODE4") (pin "25") (pinfunction "3V3_25") (pintype "unspecified"))
    )
    (net (code "109") (name "unconnected-(NODE4-A0-Pad1)") (class "Default")
      (node (ref "NODE4") (pin "1") (pinfunction "A0_1") (pintype "unspecified"))
    )
    (net (code "110") (name "unconnected-(NODE4-D0-Pad30)") (class "Default")
      (node (ref "NODE4") (pin "30") (pinfunction "D0_30") (pintype "unspecified"))
    )
    (net (code "111") (name "unconnected-(NODE4-D4-Pad26)") (class "Default")
      (node (ref "NODE4") (pin "26") (pinfunction "D4_26") (pintype "unspecified"))
    )
    (net (code "112") (name "unconnected-(NODE4-D5-Pad23)") (class "Default")
      (node (ref "NODE4") (pin "23") (pinfunction "D5_23") (pintype "unspecified"))
    )
    (net (code "113") (name "unconnected-(NODE4-D6-Pad22)") (class "Default")
      (node (ref "NODE4") (pin "22") (pinfunction "D6_22") (pintype "unspecified"))
    )
    (net (code "114") (name "unconnected-(NODE4-D7-Pad21)") (class "Default")
      (node (ref "NODE4") (pin "21") (pinfunction "D7_21") (pintype "unspecified"))
    )
    (net (code "115") (name "unconnected-(NODE4-D8-Pad20)") (class "Default")
      (node (ref "NODE4") (pin "20") (pinfunction "D8_20") (pintype "unspecified"))
    )
    (net (code "116") (name "unconnected-(NODE4-EN-Pad12)") (class "Default")
      (node (ref "NODE4") (pin "12") (pinfunction "EN_12") (pintype "unspecified"))
    )
    (net (code "117") (name "unconnected-(NODE4-GND-Pad2)") (class "Default")
      (node (ref "NODE4") (pin "2") (pinfunction "GND_2") (pintype "unspecified"))
    )
    (net (code "118") (name "unconnected-(NODE4-GND-Pad10)") (class "Default")
      (node (ref "NODE4") (pin "10") (pinfunction "GND_10") (pintype "unspecified"))
    )
    (net (code "119") (name "unconnected-(NODE4-GND-Pad14)") (class "Default")
      (node (ref "NODE4") (pin "14") (pinfunction "GND_14") (pintype "unspecified"))
    )
    (net (code "120") (name "unconnected-(NODE4-GND-Pad17)") (class "Default")
      (node (ref "NODE4") (pin "17") (pinfunction "GND_17") (pintype "unspecified"))
    )
    (net (code "121") (name "unconnected-(NODE4-RST-Pad13)") (class "Default")
      (node (ref "NODE4") (pin "13") (pinfunction "RST_13") (pintype "unspecified"))
    )
    (net (code "122") (name "unconnected-(NODE4-RX-Pad19)") (class "Default")
      (node (ref "NODE4") (pin "19") (pinfunction "RX_19") (pintype "unspecified"))
    )
    (net (code "123") (name "unconnected-(NODE4-S1-Pad6)") (class "Default")
      (node (ref "NODE4") (pin "6") (pinfunction "S1_6") (pintype "unspecified"))
    )
    (net (code "124") (name "unconnected-(NODE4-S2-Pad5)") (class "Default")
      (node (ref "NODE4") (pin "5") (pinfunction "S2_5") (pintype "unspecified"))
    )
    (net (code "125") (name "unconnected-(NODE4-S3-Pad4)") (class "Default")
      (node (ref "NODE4") (pin "4") (pinfunction "S3_4") (pintype "unspecified"))
    )
    (net (code "126") (name "unconnected-(NODE4-SC-Pad7)") (class "Default")
      (node (ref "NODE4") (pin "7") (pinfunction "SC_7") (pintype "unspecified"))
    )
    (net (code "127") (name "unconnected-(NODE4-SK-Pad9)") (class "Default")
      (node (ref "NODE4") (pin "9") (pinfunction "SK_9") (pintype "unspecified"))
    )
    (net (code "128") (name "unconnected-(NODE4-SO-Pad8)") (class "Default")
      (node (ref "NODE4") (pin "8") (pinfunction "SO_8") (pintype "unspecified"))
    )
    (net (code "129") (name "unconnected-(NODE4-TX-Pad18)") (class "Default")
      (node (ref "NODE4") (pin "18") (pinfunction "TX_18") (pintype "unspecified"))
    )
    (net (code "130") (name "unconnected-(NODE4-VU-Pad3)") (class "Default")
      (node (ref "NODE4") (pin "3") (pinfunction "VU_3") (pintype "unspecified"))
    )
    (net (code "131") (name "unconnected-(NODE4-Vin-Pad15)") (class "Default")
      (node (ref "NODE4") (pin "15") (pinfunction "Vin_15") (pintype "unspecified"))
    )
    (net (code "132") (name "unconnected-(NODE5-3V3-Pad11)") (class "Default")
      (node (ref "NODE5") (pin "11") (pinfunction "3V3_11") (pintype "unspecified"))
    )
    (net (code "133") (name "unconnected-(NODE5-3V3-Pad25)") (class "Default")
      (node (ref "NODE5") (pin "25") (pinfunction "3V3_25") (pintype "unspecified"))
    )
    (net (code "134") (name "unconnected-(NODE5-A0-Pad1)") (class "Default")
      (node (ref "NODE5") (pin "1") (pinfunction "A0_1") (pintype "unspecified"))
    )
    (net (code "135") (name "unconnected-(NODE5-D0-Pad30)") (class "Default")
      (node (ref "NODE5") (pin "30") (pinfunction "D0_30") (pintype "unspecified"))
    )
    (net (code "136") (name "unconnected-(NODE5-D1-Pad29)") (class "Default")
      (node (ref "NODE5") (pin "29") (pinfunction "D1_29") (pintype "unspecified"))
    )
    (net (code "137") (name "unconnected-(NODE5-D2-Pad28)") (class "Default")
      (node (ref "NODE5") (pin "28") (pinfunction "D2_28") (pintype "unspecified"))
    )
    (net (code "138") (name "unconnected-(NODE5-D3-Pad27)") (class "Default")
      (node (ref "NODE5") (pin "27") (pinfunction "D3_27") (pintype "unspecified"))
    )
    (net (code "139") (name "unconnected-(NODE5-D4-Pad26)") (class "Default")
      (node (ref "NODE5") (pin "26") (pinfunction "D4_26") (pintype "unspecified"))
    )
    (net (code "140") (name "unconnected-(NODE5-D5-Pad23)") (class "Default")
      (node (ref "NODE5") (pin "23") (pinfunction "D5_23") (pintype "unspecified"))
    )
    (net (code "141") (name "unconnected-(NODE5-D6-Pad22)") (class "Default")
      (node (ref "NODE5") (pin "22") (pinfunction "D6_22") (pintype "unspecified"))
    )
    (net (code "142") (name "unconnected-(NODE5-D7-Pad21)") (class "Default")
      (node (ref "NODE5") (pin "21") (pinfunction "D7_21") (pintype "unspecified"))
    )
    (net (code "143") (name "unconnected-(NODE5-EN-Pad12)") (class "Default")
      (node (ref "NODE5") (pin "12") (pinfunction "EN_12") (pintype "unspecified"))
    )
    (net (code "144") (name "unconnected-(NODE5-GND-Pad2)") (class "Default")
      (node (ref "NODE5") (pin "2") (pinfunction "GND_2") (pintype "unspecified"))
    )
    (net (code "145") (name "unconnected-(NODE5-GND-Pad10)") (class "Default")
      (node (ref "NODE5") (pin "10") (pinfunction "GND_10") (pintype "unspecified"))
    )
    (net (code "146") (name "unconnected-(NODE5-GND-Pad14)") (class "Default")
      (node (ref "NODE5") (pin "14") (pinfunction "GND_14") (pintype "unspecified"))
    )
    (net (code "147") (name "unconnected-(NODE5-GND-Pad24)") (class "Default")
      (node (ref "NODE5") (pin "24") (pinfunction "GND_24") (pintype "unspecified"))
    )
    (net (code "148") (name "unconnected-(NODE5-RST-Pad13)") (class "Default")
      (node (ref "NODE5") (pin "13") (pinfunction "RST_13") (pintype "unspecified"))
    )
    (net (code "149") (name "unconnected-(NODE5-RX-Pad19)") (class "Default")
      (node (ref "NODE5") (pin "19") (pinfunction "RX_19") (pintype "unspecified"))
    )
    (net (code "150") (name "unconnected-(NODE5-S1-Pad6)") (class "Default")
      (node (ref "NODE5") (pin "6") (pinfunction "S1_6") (pintype "unspecified"))
    )
    (net (code "151") (name "unconnected-(NODE5-S2-Pad5)") (class "Default")
      (node (ref "NODE5") (pin "5") (pinfunction "S2_5") (pintype "unspecified"))
    )
    (net (code "152") (name "unconnected-(NODE5-S3-Pad4)") (class "Default")
      (node (ref "NODE5") (pin "4") (pinfunction "S3_4") (pintype "unspecified"))
    )
    (net (code "153") (name "unconnected-(NODE5-SC-Pad7)") (class "Default")
      (node (ref "NODE5") (pin "7") (pinfunction "SC_7") (pintype "unspecified"))
    )
    (net (code "154") (name "unconnected-(NODE5-SK-Pad9)") (class "Default")
      (node (ref "NODE5") (pin "9") (pinfunction "SK_9") (pintype "unspecified"))
    )
    (net (code "155") (name "unconnected-(NODE5-SO-Pad8)") (class "Default")
      (node (ref "NODE5") (pin "8") (pinfunction "SO_8") (pintype "unspecified"))
    )
    (net (code "156") (name "unconnected-(NODE5-TX-Pad18)") (class "Default")
      (node (ref "NODE5") (pin "18") (pinfunction "TX_18") (pintype "unspecified"))
    )
    (net (code "157") (name "unconnected-(NODE5-VU-Pad3)") (class "Default")
      (node (ref "NODE5") (pin "3") (pinfunction "VU_3") (pintype "unspecified"))
    )
    (net (code "158") (name "unconnected-(NODE5-Vin-Pad15)") (class "Default")
      (node (ref "NODE5") (pin "15") (pinfunction "Vin_15") (pintype "unspecified"))
    )
    (net (code "159") (name "unconnected-(NODE6-3V3-Pad11)") (class "Default")
      (node (ref "NODE6") (pin "11") (pinfunction "3V3_11") (pintype "unspecified"))
    )
    (net (code "160") (name "unconnected-(NODE6-3V3-Pad25)") (class "Default")
      (node (ref "NODE6") (pin "25") (pinfunction "3V3_25") (pintype "unspecified"))
    )
    (net (code "161") (name "unconnected-(NODE6-A0-Pad1)") (class "Default")
      (node (ref "NODE6") (pin "1") (pinfunction "A0_1") (pintype "unspecified"))
    )
    (net (code "162") (name "unconnected-(NODE6-D0-Pad30)") (class "Default")
      (node (ref "NODE6") (pin "30") (pinfunction "D0_30") (pintype "unspecified"))
    )
    (net (code "163") (name "unconnected-(NODE6-D3-Pad27)") (class "Default")
      (node (ref "NODE6") (pin "27") (pinfunction "D3_27") (pintype "unspecified"))
    )
    (net (code "164") (name "unconnected-(NODE6-D4-Pad26)") (class "Default")
      (node (ref "NODE6") (pin "26") (pinfunction "D4_26") (pintype "unspecified"))
    )
    (net (code "165") (name "unconnected-(NODE6-D5-Pad23)") (class "Default")
      (node (ref "NODE6") (pin "23") (pinfunction "D5_23") (pintype "unspecified"))
    )
    (net (code "166") (name "unconnected-(NODE6-D6-Pad22)") (class "Default")
      (node (ref "NODE6") (pin "22") (pinfunction "D6_22") (pintype "unspecified"))
    )
    (net (code "167") (name "unconnected-(NODE6-D7-Pad21)") (class "Default")
      (node (ref "NODE6") (pin "21") (pinfunction "D7_21") (pintype "unspecified"))
    )
    (net (code "168") (name "unconnected-(NODE6-D8-Pad20)") (class "Default")
      (node (ref "NODE6") (pin "20") (pinfunction "D8_20") (pintype "unspecified"))
    )
    (net (code "169") (name "unconnected-(NODE6-EN-Pad12)") (class "Default")
      (node (ref "NODE6") (pin "12") (pinfunction "EN_12") (pintype "unspecified"))
    )
    (net (code "170") (name "unconnected-(NODE6-GND-Pad2)") (class "Default")
      (node (ref "NODE6") (pin "2") (pinfunction "GND_2") (pintype "unspecified"))
    )
    (net (code "171") (name "unconnected-(NODE6-GND-Pad10)") (class "Default")
      (node (ref "NODE6") (pin "10") (pinfunction "GND_10") (pintype "unspecified"))
    )
    (net (code "172") (name "unconnected-(NODE6-GND-Pad14)") (class "Default")
      (node (ref "NODE6") (pin "14") (pinfunction "GND_14") (pintype "unspecified"))
    )
    (net (code "173") (name "unconnected-(NODE6-GND-Pad17)") (class "Default")
      (node (ref "NODE6") (pin "17") (pinfunction "GND_17") (pintype "unspecified"))
    )
    (net (code "174") (name "unconnected-(NODE6-RST-Pad13)") (class "Default")
      (node (ref "NODE6") (pin "13") (pinfunction "RST_13") (pintype "unspecified"))
    )
    (net (code "175") (name "unconnected-(NODE6-RX-Pad19)") (class "Default")
      (node (ref "NODE6") (pin "19") (pinfunction "RX_19") (pintype "unspecified"))
    )
    (net (code "176") (name "unconnected-(NODE6-S1-Pad6)") (class "Default")
      (node (ref "NODE6") (pin "6") (pinfunction "S1_6") (pintype "unspecified"))
    )
    (net (code "177") (name "unconnected-(NODE6-S2-Pad5)") (class "Default")
      (node (ref "NODE6") (pin "5") (pinfunction "S2_5") (pintype "unspecified"))
    )
    (net (code "178") (name "unconnected-(NODE6-S3-Pad4)") (class "Default")
      (node (ref "NODE6") (pin "4") (pinfunction "S3_4") (pintype "unspecified"))
    )
    (net (code "179") (name "unconnected-(NODE6-SC-Pad7)") (class "Default")
      (node (ref "NODE6") (pin "7") (pinfunction "SC_7") (pintype "unspecified"))
    )
    (net (code "180") (name "unconnected-(NODE6-SK-Pad9)") (class "Default")
      (node (ref "NODE6") (pin "9") (pinfunction "SK_9") (pintype "unspecified"))
    )
    (net (code "181") (name "unconnected-(NODE6-SO-Pad8)") (class "Default")
      (node (ref "NODE6") (pin "8") (pinfunction "SO_8") (pintype "unspecified"))
    )
    (net (code "182") (name "unconnected-(NODE6-TX-Pad18)") (class "Default")
      (node (ref "NODE6") (pin "18") (pinfunction "TX_18") (pintype "unspecified"))
    )
    (net (code "183") (name "unconnected-(NODE6-VU-Pad3)") (class "Default")
      (node (ref "NODE6") (pin "3") (pinfunction "VU_3") (pintype "unspecified"))
    )
    (net (code "184") (name "unconnected-(NODE6-Vin-Pad15)") (class "Default")
      (node (ref "NODE6") (pin "15") (pinfunction "Vin_15") (pintype "unspecified"))
    )
    (net (code "185") (name "unconnected-(NODE7-3V3-Pad16)") (class "Default")
      (node (ref "NODE7") (pin "16") (pinfunction "3V3_16") (pintype "unspecified"))
    )
    (net (code "186") (name "unconnected-(NODE7-3V3-Pad25)") (class "Default")
      (node (ref "NODE7") (pin "25") (pinfunction "3V3_25") (pintype "unspecified"))
    )
    (net (code "187") (name "unconnected-(NODE7-A0-Pad1)") (class "Default")
      (node (ref "NODE7") (pin "1") (pinfunction "A0_1") (pintype "unspecified"))
    )
    (net (code "188") (name "unconnected-(NODE7-D0-Pad30)") (class "Default")
      (node (ref "NODE7") (pin "30") (pinfunction "D0_30") (pintype "unspecified"))
    )
    (net (code "189") (name "unconnected-(NODE7-D1-Pad29)") (class "Default")
      (node (ref "NODE7") (pin "29") (pinfunction "D1_29") (pintype "unspecified"))
    )
    (net (code "190") (name "unconnected-(NODE7-D8-Pad20)") (class "Default")
      (node (ref "NODE7") (pin "20") (pinfunction "D8_20") (pintype "unspecified"))
    )
    (net (code "191") (name "unconnected-(NODE7-EN-Pad12)") (class "Default")
      (node (ref "NODE7") (pin "12") (pinfunction "EN_12") (pintype "unspecified"))
    )
    (net (code "192") (name "unconnected-(NODE7-GND-Pad10)") (class "Default")
      (node (ref "NODE7") (pin "10") (pinfunction "GND_10") (pintype "unspecified"))
    )
    (net (code "193") (name "unconnected-(NODE7-GND-Pad14)") (class "Default")
      (node (ref "NODE7") (pin "14") (pinfunction "GND_14") (pintype "unspecified"))
    )
    (net (code "194") (name "unconnected-(NODE7-GND-Pad17)") (class "Default")
      (node (ref "NODE7") (pin "17") (pinfunction "GND_17") (pintype "unspecified"))
    )
    (net (code "195") (name "unconnected-(NODE7-GND-Pad24)") (class "Default")
      (node (ref "NODE7") (pin "24") (pinfunction "GND_24") (pintype "unspecified"))
    )
    (net (code "196") (name "unconnected-(NODE7-RST-Pad13)") (class "Default")
      (node (ref "NODE7") (pin "13") (pinfunction "RST_13") (pintype "unspecified"))
    )
    (net (code "197") (name "unconnected-(NODE7-RX-Pad19)") (class "Default")
      (node (ref "NODE7") (pin "19") (pinfunction "RX_19") (pintype "unspecified"))
    )
    (net (code "198") (name "unconnected-(NODE7-S1-Pad6)") (class "Default")
      (node (ref "NODE7") (pin "6") (pinfunction "S1_6") (pintype "unspecified"))
    )
    (net (code "199") (name "unconnected-(NODE7-S2-Pad5)") (class "Default")
      (node (ref "NODE7") (pin "5") (pinfunction "S2_5") (pintype "unspecified"))
    )
    (net (code "200") (name "unconnected-(NODE7-S3-Pad4)") (class "Default")
      (node (ref "NODE7") (pin "4") (pinfunction "S3_4") (pintype "unspecified"))
    )
    (net (code "201") (name "unconnected-(NODE7-SC-Pad7)") (class "Default")
      (node (ref "NODE7") (pin "7") (pinfunction "SC_7") (pintype "unspecified"))
    )
    (net (code "202") (name "unconnected-(NODE7-SK-Pad9)") (class "Default")
      (node (ref "NODE7") (pin "9") (pinfunction "SK_9") (pintype "unspecified"))
    )
    (net (code "203") (name "unconnected-(NODE7-SO-Pad8)") (class "Default")
      (node (ref "NODE7") (pin "8") (pinfunction "SO_8") (pintype "unspecified"))
    )
    (net (code "204") (name "unconnected-(NODE7-TX-Pad18)") (class "Default")
      (node (ref "NODE7") (pin "18") (pinfunction "TX_18") (pintype "unspecified"))
    )
    (net (code "205") (name "unconnected-(NODE7-VU-Pad3)") (class "Default")
      (node (ref "NODE7") (pin "3") (pinfunction "VU_3") (pintype "unspecified"))
    )
    (net (code "206") (name "unconnected-(NODE7-Vin-Pad15)") (class "Default")
      (node (ref "NODE7") (pin "15") (pinfunction "Vin_15") (pintype "unspecified"))
    )
    (net (code "207") (name "unconnected-(NODE8-3V3-Pad11)") (class "Default")
      (node (ref "NODE8") (pin "11") (pinfunction "3V3_11") (pintype "unspecified"))
    )
    (net (code "208") (name "unconnected-(NODE8-3V3-Pad25)") (class "Default")
      (node (ref "NODE8") (pin "25") (pinfunction "3V3_25") (pintype "unspecified"))
    )
    (net (code "209") (name "unconnected-(NODE8-A0-Pad1)") (class "Default")
      (node (ref "NODE8") (pin "1") (pinfunction "A0_1") (pintype "unspecified"))
    )
    (net (code "210") (name "unconnected-(NODE8-D0-Pad30)") (class "Default")
      (node (ref "NODE8") (pin "30") (pinfunction "D0_30") (pintype "unspecified"))
    )
    (net (code "211") (name "unconnected-(NODE8-D3-Pad27)") (class "Default")
      (node (ref "NODE8") (pin "27") (pinfunction "D3_27") (pintype "unspecified"))
    )
    (net (code "212") (name "unconnected-(NODE8-D4-Pad26)") (class "Default")
      (node (ref "NODE8") (pin "26") (pinfunction "D4_26") (pintype "unspecified"))
    )
    (net (code "213") (name "unconnected-(NODE8-D5-Pad23)") (class "Default")
      (node (ref "NODE8") (pin "23") (pinfunction "D5_23") (pintype "unspecified"))
    )
    (net (code "214") (name "unconnected-(NODE8-D6-Pad22)") (class "Default")
      (node (ref "NODE8") (pin "22") (pinfunction "D6_22") (pintype "unspecified"))
    )
    (net (code "215") (name "unconnected-(NODE8-D7-Pad21)") (class "Default")
      (node (ref "NODE8") (pin "21") (pinfunction "D7_21") (pintype "unspecified"))
    )
    (net (code "216") (name "unconnected-(NODE8-D8-Pad20)") (class "Default")
      (node (ref "NODE8") (pin "20") (pinfunction "D8_20") (pintype "unspecified"))
    )
    (net (code "217") (name "unconnected-(NODE8-EN-Pad12)") (class "Default")
      (node (ref "NODE8") (pin "12") (pinfunction "EN_12") (pintype "unspecified"))
    )
    (net (code "218") (name "unconnected-(NODE8-GND-Pad10)") (class "Default")
      (node (ref "NODE8") (pin "10") (pinfunction "GND_10") (pintype "unspecified"))
    )
    (net (code "219") (name "unconnected-(NODE8-GND-Pad14)") (class "Default")
      (node (ref "NODE8") (pin "14") (pinfunction "GND_14") (pintype "unspecified"))
    )
    (net (code "220") (name "unconnected-(NODE8-GND-Pad17)") (class "Default")
      (node (ref "NODE8") (pin "17") (pinfunction "GND_17") (pintype "unspecified"))
    )
    (net (code "221") (name "unconnected-(NODE8-GND-Pad24)") (class "Default")
      (node (ref "NODE8") (pin "24") (pinfunction "GND_24") (pintype "unspecified"))
    )
    (net (code "222") (name "unconnected-(NODE8-RST-Pad13)") (class "Default")
      (node (ref "NODE8") (pin "13") (pinfunction "RST_13") (pintype "unspecified"))
    )
    (net (code "223") (name "unconnected-(NODE8-RX-Pad19)") (class "Default")
      (node (ref "NODE8") (pin "19") (pinfunction "RX_19") (pintype "unspecified"))
    )
    (net (code "224") (name "unconnected-(NODE8-S1-Pad6)") (class "Default")
      (node (ref "NODE8") (pin "6") (pinfunction "S1_6") (pintype "unspecified"))
    )
    (net (code "225") (name "unconnected-(NODE8-S2-Pad5)") (class "Default")
      (node (ref "NODE8") (pin "5") (pinfunction "S2_5") (pintype "unspecified"))
    )
    (net (code "226") (name "unconnected-(NODE8-S3-Pad4)") (class "Default")
      (node (ref "NODE8") (pin "4") (pinfunction "S3_4") (pintype "unspecified"))
    )
    (net (code "227") (name "unconnected-(NODE8-SC-Pad7)") (class "Default")
      (node (ref "NODE8") (pin "7") (pinfunction "SC_7") (pintype "unspecified"))
    )
    (net (code "228") (name "unconnected-(NODE8-SK-Pad9)") (class "Default")
      (node (ref "NODE8") (pin "9") (pinfunction "SK_9") (pintype "unspecified"))
    )
    (net (code "229") (name "unconnected-(NODE8-SO-Pad8)") (class "Default")
      (node (ref "NODE8") (pin "8") (pinfunction "SO_8") (pintype "unspecified"))
    )
    (net (code "230") (name "unconnected-(NODE8-TX-Pad18)") (class "Default")
      (node (ref "NODE8") (pin "18") (pinfunction "TX_18") (pintype "unspecified"))
    )
    (net (code "231") (name "unconnected-(NODE8-VU-Pad3)") (class "Default")
      (node (ref "NODE8") (pin "3") (pinfunction "VU_3") (pintype "unspecified"))
    )
    (net (code "232") (name "unconnected-(NODE8-Vin-Pad15)") (class "Default")
      (node (ref "NODE8") (pin "15") (pinfunction "Vin_15") (pintype "unspecified"))
    )
    (net (code "233") (name "unconnected-(S1-S+-Pad5)") (class "Default")
      (node (ref "S1") (pin "5") (pinfunction "S+_5") (pintype "unspecified"))
    )
    (net (code "234") (name "unconnected-(S1-S--Pad6)") (class "Default")
      (node (ref "S1") (pin "6") (pinfunction "S-_6") (pintype "unspecified"))
    )
    (net (code "235") (name "unconnected-(U1-3V-Pad29)") (class "Default")
      (node (ref "U1") (pin "29") (pinfunction "3V_29") (pintype "passive"))
    )
    (net (code "236") (name "unconnected-(U1-14{slash}A0{slash}PC0-Pad24)") (class "Default")
      (node (ref "U1") (pin "24") (pinfunction "14/A0/PC0_24") (pintype "unspecified"))
    )
    (net (code "237") (name "unconnected-(U1-15{slash}A1{slash}PC1-Pad23)") (class "Default")
      (node (ref "U1") (pin "23") (pinfunction "15/A1/PC1_23") (pintype "unspecified"))
    )
    (net (code "238") (name "unconnected-(U1-16{slash}A2{slash}PC2-Pad22)") (class "Default")
      (node (ref "U1") (pin "22") (pinfunction "16/A2/PC2_22") (pintype "unspecified"))
    )
    (net (code "239") (name "unconnected-(U1-17{slash}A3{slash}PC3-Pad21)") (class "Default")
      (node (ref "U1") (pin "21") (pinfunction "17/A3/PC3_21") (pintype "unspecified"))
    )
    (net (code "240") (name "unconnected-(U1-18{slash}A4{slash}PC4{slash}SDA-Pad20)") (class "Default")
      (node (ref "U1") (pin "20") (pinfunction "18/A4/PC4/SDA_20") (pintype "unspecified"))
    )
    (net (code "241") (name "unconnected-(U1-19{slash}A5{slash}PC5{slash}SCL-Pad19)") (class "Default")
      (node (ref "U1") (pin "19") (pinfunction "19/A5/PC5/SCL_19") (pintype "unspecified"))
    )
    (net (code "242") (name "unconnected-(U1-AREF-Pad16)") (class "Default")
      (node (ref "U1") (pin "16") (pinfunction "AREF_16") (pintype "unspecified"))
    )
    (net (code "243") (name "unconnected-(U1-GND-Pad15)") (class "Default")
      (node (ref "U1") (pin "15") (pinfunction "GND_15") (pintype "passive"))
    )
    (net (code "244") (name "unconnected-(U1-GND2-Pad27)") (class "Default")
      (node (ref "U1") (pin "27") (pinfunction "GND2_27") (pintype "passive"))
    )
    (net (code "245") (name "unconnected-(U1-INT0{slash}PD2{slash}2-Pad3)") (class "Default")
      (node (ref "U1") (pin "3") (pinfunction "INT0/PD2/2_3") (pintype "unspecified"))
    )
    (net (code "246") (name "unconnected-(U1-INT1{slash}PWR{slash}PD3{slash}3-Pad4)") (class "Default")
      (node (ref "U1") (pin "4") (pinfunction "INT1/PWR/PD3/3_4") (pintype "unspecified"))
    )
    (net (code "247") (name "unconnected-(U1-IOREF-Pad31)") (class "Default")
      (node (ref "U1") (pin "31") (pinfunction "IOREF_31") (pintype "unspecified"))
    )
    (net (code "248") (name "unconnected-(U1-MISO{slash}PB4{slash}12-Pad13)") (class "Default")
      (node (ref "U1") (pin "13") (pinfunction "MISO/PB4/12_13") (pintype "unspecified"))
    )
    (net (code "249") (name "unconnected-(U1-MOSI{slash}PWR{slash}PB3{slash}11-Pad12)") (class "Default")
      (node (ref "U1") (pin "12") (pinfunction "MOSI/PWR/PB3/11_12") (pintype "unspecified"))
    )
    (net (code "250") (name "unconnected-(U1-NC-Pad32)") (class "Default")
      (node (ref "U1") (pin "32") (pinfunction "NC_32") (pintype "unspecified"))
    )
    (net (code "251") (name "unconnected-(U1-PB0{slash}8-Pad9)") (class "Default")
      (node (ref "U1") (pin "9") (pinfunction "PB0/8_9") (pintype "unspecified"))
    )
    (net (code "252") (name "unconnected-(U1-PD4{slash}4-Pad5)") (class "Default")
      (node (ref "U1") (pin "5") (pinfunction "PD4/4_5") (pintype "unspecified"))
    )
    (net (code "253") (name "unconnected-(U1-PD7{slash}7-Pad8)") (class "Default")
      (node (ref "U1") (pin "8") (pinfunction "PD7/7_8") (pintype "unspecified"))
    )
    (net (code "254") (name "unconnected-(U1-PWR{slash}PB1{slash}9-Pad10)") (class "Default")
      (node (ref "U1") (pin "10") (pinfunction "PWR/PB1/9_10") (pintype "unspecified"))
    )
    (net (code "255") (name "unconnected-(U1-PWR{slash}PD5{slash}5-Pad6)") (class "Default")
      (node (ref "U1") (pin "6") (pinfunction "PWR/PD5/5_6") (pintype "unspecified"))
    )
    (net (code "256") (name "unconnected-(U1-RESET-Pad30)") (class "Default")
      (node (ref "U1") (pin "30") (pinfunction "RESET_30") (pintype "unspecified"))
    )
    (net (code "257") (name "unconnected-(U1-RX{slash}PD0{slash}0-Pad1)") (class "Default")
      (node (ref "U1") (pin "1") (pinfunction "RX/PD0/0_1") (pintype "unspecified"))
    )
    (net (code "258") (name "unconnected-(U1-SCK{slash}PB5{slash}13-Pad14)") (class "Default")
      (node (ref "U1") (pin "14") (pinfunction "SCK/PB5/13_14") (pintype "unspecified"))
    )
    (net (code "259") (name "unconnected-(U1-SCL-Pad18)") (class "Default")
      (node (ref "U1") (pin "18") (pinfunction "SCL_18") (pintype "unspecified"))
    )
    (net (code "260") (name "unconnected-(U1-SDA-Pad17)") (class "Default")
      (node (ref "U1") (pin "17") (pinfunction "SDA_17") (pintype "unspecified"))
    )
    (net (code "261") (name "unconnected-(U1-SS{slash}PWR{slash}PB2{slash}10-Pad11)") (class "Default")
      (node (ref "U1") (pin "11") (pinfunction "SS/PWR/PB2/10_11") (pintype "unspecified"))
    )
    (net (code "262") (name "unconnected-(U1-TX{slash}PD1{slash}1-Pad2)") (class "Default")
      (node (ref "U1") (pin "2") (pinfunction "TX/PD1/1_2") (pintype "unspecified"))
    )
    (net (code "263") (name "unconnected-(U1-VIN-Pad25)") (class "Default")
      (node (ref "U1") (pin "25") (pinfunction "VIN_25") (pintype "passive"))
    )
    (net (code "264") (name "unconnected-(U2-3V3-Pad17)") (class "Default")
      (node (ref "U2") (pin "17") (pinfunction "3V3_17") (pintype "unspecified"))
    )
    (net (code "265") (name "unconnected-(U2-A0-Pad19)") (class "Default")
      (node (ref "U2") (pin "19") (pinfunction "A0_19") (pintype "unspecified"))
    )
    (net (code "266") (name "unconnected-(U2-A1-Pad20)") (class "Default")
      (node (ref "U2") (pin "20") (pinfunction "A1_20") (pintype "unspecified"))
    )
    (net (code "267") (name "unconnected-(U2-A2-Pad21)") (class "Default")
      (node (ref "U2") (pin "21") (pinfunction "A2_21") (pintype "unspecified"))
    )
    (net (code "268") (name "unconnected-(U2-A3-Pad22)") (class "Default")
      (node (ref "U2") (pin "22") (pinfunction "A3_22") (pintype "unspecified"))
    )
    (net (code "269") (name "unconnected-(U2-A4-Pad23)") (class "Default")
      (node (ref "U2") (pin "23") (pinfunction "A4_23") (pintype "unspecified"))
    )
    (net (code "270") (name "unconnected-(U2-A5-Pad24)") (class "Default")
      (node (ref "U2") (pin "24") (pinfunction "A5_24") (pintype "unspecified"))
    )
    (net (code "271") (name "unconnected-(U2-A6-Pad25)") (class "Default")
      (node (ref "U2") (pin "25") (pinfunction "A6_25") (pintype "unspecified"))
    )
    (net (code "272") (name "unconnected-(U2-A7-Pad26)") (class "Default")
      (node (ref "U2") (pin "26") (pinfunction "A7_26") (pintype "unspecified"))
    )
    (net (code "273") (name "unconnected-(U2-AREF-Pad18)") (class "Default")
      (node (ref "U2") (pin "18") (pinfunction "AREF_18") (pintype "unspecified"))
    )
    (net (code "274") (name "unconnected-(U2-D0{slash}RX-Pad2)") (class "Default")
      (node (ref "U2") (pin "2") (pinfunction "D0/RX_2") (pintype "unspecified"))
    )
    (net (code "275") (name "unconnected-(U2-D1{slash}TX-Pad1)") (class "Default")
      (node (ref "U2") (pin "1") (pinfunction "D1/TX_1") (pintype "unspecified"))
    )
    (net (code "276") (name "unconnected-(U2-D2-Pad5)") (class "Default")
      (node (ref "U2") (pin "5") (pinfunction "D2_5") (pintype "unspecified"))
    )
    (net (code "277") (name "unconnected-(U2-D4-Pad7)") (class "Default")
      (node (ref "U2") (pin "7") (pinfunction "D4_7") (pintype "unspecified"))
    )
    (net (code "278") (name "unconnected-(U2-D5-Pad8)") (class "Default")
      (node (ref "U2") (pin "8") (pinfunction "D5_8") (pintype "unspecified"))
    )
    (net (code "279") (name "unconnected-(U2-D6-Pad9)") (class "Default")
      (node (ref "U2") (pin "9") (pinfunction "D6_9") (pintype "unspecified"))
    )
    (net (code "280") (name "unconnected-(U2-D7-Pad10)") (class "Default")
      (node (ref "U2") (pin "10") (pinfunction "D7_10") (pintype "unspecified"))
    )
    (net (code "281") (name "unconnected-(U2-D8-Pad11)") (class "Default")
      (node (ref "U2") (pin "11") (pinfunction "D8_11") (pintype "unspecified"))
    )
    (net (code "282") (name "unconnected-(U2-D9-Pad12)") (class "Default")
      (node (ref "U2") (pin "12") (pinfunction "D9_12") (pintype "unspecified"))
    )
    (net (code "283") (name "unconnected-(U2-D10-Pad13)") (class "Default")
      (node (ref "U2") (pin "13") (pinfunction "D10_13") (pintype "unspecified"))
    )
    (net (code "284") (name "unconnected-(U2-D11-Pad14)") (class "Default")
      (node (ref "U2") (pin "14") (pinfunction "D11_14") (pintype "unspecified"))
    )
    (net (code "285") (name "unconnected-(U2-D12-Pad15)") (class "Default")
      (node (ref "U2") (pin "15") (pinfunction "D12_15") (pintype "unspecified"))
    )
    (net (code "286") (name "unconnected-(U2-D13-Pad16)") (class "Default")
      (node (ref "U2") (pin "16") (pinfunction "D13_16") (pintype "unspecified"))
    )
    (net (code "287") (name "unconnected-(U2-GND-Pad29)") (class "Default")
      (node (ref "U2") (pin "29") (pinfunction "GND_29") (pintype "unspecified"))
    )
    (net (code "288") (name "unconnected-(U2-RESET-Pad3)") (class "Default")
      (node (ref "U2") (pin "3") (pinfunction "RESET_3") (pintype "unspecified"))
    )
    (net (code "289") (name "unconnected-(U2-RESET-Pad28)") (class "Default")
      (node (ref "U2") (pin "28") (pinfunction "RESET_28") (pintype "unspecified"))
    )
    (net (code "290") (name "unconnected-(U2-VIN-Pad30)") (class "Default")
      (node (ref "U2") (pin "30") (pinfunction "VIN_30") (pintype "unspecified"))
    )
    (net (code "291") (name "unconnected-(U5-AOUT-Pad3)") (class "Default")
      (node (ref "U5") (pin "3") (pinfunction "AOUT_3") (pintype "unspecified"))
    )
    (net (code "292") (name "unconnected-(U5-GND-Pad1)") (class "Default")
      (node (ref "U5") (pin "1") (pinfunction "GND_1") (pintype "unspecified"))
    )
    (net (code "293") (name "unconnected-(U5-VCC-Pad2)") (class "Default")
      (node (ref "U5") (pin "2") (pinfunction "VCC_2") (pintype "unspecified"))
    )
    (net (code "294") (name "unconnected-(U6-3V3-Pad17)") (class "Default")
      (node (ref "U6") (pin "17") (pinfunction "3V3_17") (pintype "unspecified"))
    )
    (net (code "295") (name "unconnected-(U6-A1-Pad20)") (class "Default")
      (node (ref "U6") (pin "20") (pinfunction "A1_20") (pintype "unspecified"))
    )
    (net (code "296") (name "unconnected-(U6-A2-Pad21)") (class "Default")
      (node (ref "U6") (pin "21") (pinfunction "A2_21") (pintype "unspecified"))
    )
    (net (code "297") (name "unconnected-(U6-A3-Pad22)") (class "Default")
      (node (ref "U6") (pin "22") (pinfunction "A3_22") (pintype "unspecified"))
    )
    (net (code "298") (name "unconnected-(U6-A4-Pad23)") (class "Default")
      (node (ref "U6") (pin "23") (pinfunction "A4_23") (pintype "unspecified"))
    )
    (net (code "299") (name "unconnected-(U6-A5-Pad24)") (class "Default")
      (node (ref "U6") (pin "24") (pinfunction "A5_24") (pintype "unspecified"))
    )
    (net (code "300") (name "unconnected-(U6-A6-Pad25)") (class "Default")
      (node (ref "U6") (pin "25") (pinfunction "A6_25") (pintype "unspecified"))
    )
    (net (code "301") (name "unconnected-(U6-A7-Pad26)") (class "Default")
      (node (ref "U6") (pin "26") (pinfunction "A7_26") (pintype "unspecified"))
    )
    (net (code "302") (name "unconnected-(U6-AREF-Pad18)") (class "Default")
      (node (ref "U6") (pin "18") (pinfunction "AREF_18") (pintype "unspecified"))
    )
    (net (code "303") (name "unconnected-(U6-D0{slash}RX-Pad2)") (class "Default")
      (node (ref "U6") (pin "2") (pinfunction "D0/RX_2") (pintype "unspecified"))
    )
    (net (code "304") (name "unconnected-(U6-D1{slash}TX-Pad1)") (class "Default")
      (node (ref "U6") (pin "1") (pinfunction "D1/TX_1") (pintype "unspecified"))
    )
    (net (code "305") (name "unconnected-(U6-D2-Pad5)") (class "Default")
      (node (ref "U6") (pin "5") (pinfunction "D2_5") (pintype "unspecified"))
    )
    (net (code "306") (name "unconnected-(U6-D3-Pad6)") (class "Default")
      (node (ref "U6") (pin "6") (pinfunction "D3_6") (pintype "unspecified"))
    )
    (net (code "307") (name "unconnected-(U6-D4-Pad7)") (class "Default")
      (node (ref "U6") (pin "7") (pinfunction "D4_7") (pintype "unspecified"))
    )
    (net (code "308") (name "unconnected-(U6-D5-Pad8)") (class "Default")
      (node (ref "U6") (pin "8") (pinfunction "D5_8") (pintype "unspecified"))
    )
    (net (code "309") (name "unconnected-(U6-D6-Pad9)") (class "Default")
      (node (ref "U6") (pin "9") (pinfunction "D6_9") (pintype "unspecified"))
    )
    (net (code "310") (name "unconnected-(U6-D7-Pad10)") (class "Default")
      (node (ref "U6") (pin "10") (pinfunction "D7_10") (pintype "unspecified"))
    )
    (net (code "311") (name "unconnected-(U6-D8-Pad11)") (class "Default")
      (node (ref "U6") (pin "11") (pinfunction "D8_11") (pintype "unspecified"))
    )
    (net (code "312") (name "unconnected-(U6-D9-Pad12)") (class "Default")
      (node (ref "U6") (pin "12") (pinfunction "D9_12") (pintype "unspecified"))
    )
    (net (code "313") (name "unconnected-(U6-D10-Pad13)") (class "Default")
      (node (ref "U6") (pin "13") (pinfunction "D10_13") (pintype "unspecified"))
    )
    (net (code "314") (name "unconnected-(U6-D11-Pad14)") (class "Default")
      (node (ref "U6") (pin "14") (pinfunction "D11_14") (pintype "unspecified"))
    )
    (net (code "315") (name "unconnected-(U6-D12-Pad15)") (class "Default")
      (node (ref "U6") (pin "15") (pinfunction "D12_15") (pintype "unspecified"))
    )
    (net (code "316") (name "unconnected-(U6-D13-Pad16)") (class "Default")
      (node (ref "U6") (pin "16") (pinfunction "D13_16") (pintype "unspecified"))
    )
    (net (code "317") (name "unconnected-(U6-GND-Pad29)") (class "Default")
      (node (ref "U6") (pin "29") (pinfunction "GND_29") (pintype "unspecified"))
    )
    (net (code "318") (name "unconnected-(U6-RESET-Pad3)") (class "Default")
      (node (ref "U6") (pin "3") (pinfunction "RESET_3") (pintype "unspecified"))
    )
    (net (code "319") (name "unconnected-(U6-RESET-Pad28)") (class "Default")
      (node (ref "U6") (pin "28") (pinfunction "RESET_28") (pintype "unspecified"))
    )
    (net (code "320") (name "unconnected-(U6-VIN-Pad30)") (class "Default")
      (node (ref "U6") (pin "30") (pinfunction "VIN_30") (pintype "unspecified"))
    )
    (net (code "321") (name "unconnected-(U7-3V-Pad29)") (class "Default")
      (node (ref "U7") (pin "29") (pinfunction "3V_29") (pintype "passive"))
    )
    (net (code "322") (name "unconnected-(U7-15{slash}A1{slash}PC1-Pad23)") (class "Default")
      (node (ref "U7") (pin "23") (pinfunction "15/A1/PC1_23") (pintype "unspecified"))
    )
    (net (code "323") (name "unconnected-(U7-16{slash}A2{slash}PC2-Pad22)") (class "Default")
      (node (ref "U7") (pin "22") (pinfunction "16/A2/PC2_22") (pintype "unspecified"))
    )
    (net (code "324") (name "unconnected-(U7-17{slash}A3{slash}PC3-Pad21)") (class "Default")
      (node (ref "U7") (pin "21") (pinfunction "17/A3/PC3_21") (pintype "unspecified"))
    )
    (net (code "325") (name "unconnected-(U7-18{slash}A4{slash}PC4{slash}SDA-Pad20)") (class "Default")
      (node (ref "U7") (pin "20") (pinfunction "18/A4/PC4/SDA_20") (pintype "unspecified"))
    )
    (net (code "326") (name "unconnected-(U7-19{slash}A5{slash}PC5{slash}SCL-Pad19)") (class "Default")
      (node (ref "U7") (pin "19") (pinfunction "19/A5/PC5/SCL_19") (pintype "unspecified"))
    )
    (net (code "327") (name "unconnected-(U7-AREF-Pad16)") (class "Default")
      (node (ref "U7") (pin "16") (pinfunction "AREF_16") (pintype "unspecified"))
    )
    (net (code "328") (name "unconnected-(U7-GND-Pad15)") (class "Default")
      (node (ref "U7") (pin "15") (pinfunction "GND_15") (pintype "passive"))
    )
    (net (code "329") (name "unconnected-(U7-GND2-Pad27)") (class "Default")
      (node (ref "U7") (pin "27") (pinfunction "GND2_27") (pintype "passive"))
    )
    (net (code "330") (name "unconnected-(U7-INT0{slash}PD2{slash}2-Pad3)") (class "Default")
      (node (ref "U7") (pin "3") (pinfunction "INT0/PD2/2_3") (pintype "unspecified"))
    )
    (net (code "331") (name "unconnected-(U7-INT1{slash}PWR{slash}PD3{slash}3-Pad4)") (class "Default")
      (node (ref "U7") (pin "4") (pinfunction "INT1/PWR/PD3/3_4") (pintype "unspecified"))
    )
    (net (code "332") (name "unconnected-(U7-IOREF-Pad31)") (class "Default")
      (node (ref "U7") (pin "31") (pinfunction "IOREF_31") (pintype "unspecified"))
    )
    (net (code "333") (name "unconnected-(U7-MISO{slash}PB4{slash}12-Pad13)") (class "Default")
      (node (ref "U7") (pin "13") (pinfunction "MISO/PB4/12_13") (pintype "unspecified"))
    )
    (net (code "334") (name "unconnected-(U7-MOSI{slash}PWR{slash}PB3{slash}11-Pad12)") (class "Default")
      (node (ref "U7") (pin "12") (pinfunction "MOSI/PWR/PB3/11_12") (pintype "unspecified"))
    )
    (net (code "335") (name "unconnected-(U7-NC-Pad32)") (class "Default")
      (node (ref "U7") (pin "32") (pinfunction "NC_32") (pintype "unspecified"))
    )
    (net (code "336") (name "unconnected-(U7-PB0{slash}8-Pad9)") (class "Default")
      (node (ref "U7") (pin "9") (pinfunction "PB0/8_9") (pintype "unspecified"))
    )
    (net (code "337") (name "unconnected-(U7-PD4{slash}4-Pad5)") (class "Default")
      (node (ref "U7") (pin "5") (pinfunction "PD4/4_5") (pintype "unspecified"))
    )
    (net (code "338") (name "unconnected-(U7-PD7{slash}7-Pad8)") (class "Default")
      (node (ref "U7") (pin "8") (pinfunction "PD7/7_8") (pintype "unspecified"))
    )
    (net (code "339") (name "unconnected-(U7-PWR{slash}PB1{slash}9-Pad10)") (class "Default")
      (node (ref "U7") (pin "10") (pinfunction "PWR/PB1/9_10") (pintype "unspecified"))
    )
    (net (code "340") (name "unconnected-(U7-PWR{slash}PD5{slash}5-Pad6)") (class "Default")
      (node (ref "U7") (pin "6") (pinfunction "PWR/PD5/5_6") (pintype "unspecified"))
    )
    (net (code "341") (name "unconnected-(U7-PWR{slash}PD6{slash}6-Pad7)") (class "Default")
      (node (ref "U7") (pin "7") (pinfunction "PWR/PD6/6_7") (pintype "unspecified"))
    )
    (net (code "342") (name "unconnected-(U7-RESET-Pad30)") (class "Default")
      (node (ref "U7") (pin "30") (pinfunction "RESET_30") (pintype "unspecified"))
    )
    (net (code "343") (name "unconnected-(U7-RX{slash}PD0{slash}0-Pad1)") (class "Default")
      (node (ref "U7") (pin "1") (pinfunction "RX/PD0/0_1") (pintype "unspecified"))
    )
    (net (code "344") (name "unconnected-(U7-SCK{slash}PB5{slash}13-Pad14)") (class "Default")
      (node (ref "U7") (pin "14") (pinfunction "SCK/PB5/13_14") (pintype "unspecified"))
    )
    (net (code "345") (name "unconnected-(U7-SCL-Pad18)") (class "Default")
      (node (ref "U7") (pin "18") (pinfunction "SCL_18") (pintype "unspecified"))
    )
    (net (code "346") (name "unconnected-(U7-SDA-Pad17)") (class "Default")
      (node (ref "U7") (pin "17") (pinfunction "SDA_17") (pintype "unspecified"))
    )
    (net (code "347") (name "unconnected-(U7-SS{slash}PWR{slash}PB2{slash}10-Pad11)") (class "Default")
      (node (ref "U7") (pin "11") (pinfunction "SS/PWR/PB2/10_11") (pintype "unspecified"))
    )
    (net (code "348") (name "unconnected-(U7-TX{slash}PD1{slash}1-Pad2)") (class "Default")
      (node (ref "U7") (pin "2") (pinfunction "TX/PD1/1_2") (pintype "unspecified"))
    )
    (net (code "349") (name "unconnected-(U7-VIN-Pad25)") (class "Default")
      (node (ref "U7") (pin "25") (pinfunction "VIN_25") (pintype "passive"))
    )
    (net (code "350") (name "unconnected-(U9-3V3-Pad17)") (class "Default")
      (node (ref "U9") (pin "17") (pinfunction "3V3_17") (pintype "unspecified"))
    )
    (net (code "351") (name "unconnected-(U9-A1-Pad20)") (class "Default")
      (node (ref "U9") (pin "20") (pinfunction "A1_20") (pintype "unspecified"))
    )
    (net (code "352") (name "unconnected-(U9-A2-Pad21)") (class "Default")
      (node (ref "U9") (pin "21") (pinfunction "A2_21") (pintype "unspecified"))
    )
    (net (code "353") (name "unconnected-(U9-A3-Pad22)") (class "Default")
      (node (ref "U9") (pin "22") (pinfunction "A3_22") (pintype "unspecified"))
    )
    (net (code "354") (name "unconnected-(U9-A4-Pad23)") (class "Default")
      (node (ref "U9") (pin "23") (pinfunction "A4_23") (pintype "unspecified"))
    )
    (net (code "355") (name "unconnected-(U9-A5-Pad24)") (class "Default")
      (node (ref "U9") (pin "24") (pinfunction "A5_24") (pintype "unspecified"))
    )
    (net (code "356") (name "unconnected-(U9-A6-Pad25)") (class "Default")
      (node (ref "U9") (pin "25") (pinfunction "A6_25") (pintype "unspecified"))
    )
    (net (code "357") (name "unconnected-(U9-A7-Pad26)") (class "Default")
      (node (ref "U9") (pin "26") (pinfunction "A7_26") (pintype "unspecified"))
    )
    (net (code "358") (name "unconnected-(U9-AREF-Pad18)") (class "Default")
      (node (ref "U9") (pin "18") (pinfunction "AREF_18") (pintype "unspecified"))
    )
    (net (code "359") (name "unconnected-(U9-D0{slash}RX-Pad2)") (class "Default")
      (node (ref "U9") (pin "2") (pinfunction "D0/RX_2") (pintype "unspecified"))
    )
    (net (code "360") (name "unconnected-(U9-D1{slash}TX-Pad1)") (class "Default")
      (node (ref "U9") (pin "1") (pinfunction "D1/TX_1") (pintype "unspecified"))
    )
    (net (code "361") (name "unconnected-(U9-D2-Pad5)") (class "Default")
      (node (ref "U9") (pin "5") (pinfunction "D2_5") (pintype "unspecified"))
    )
    (net (code "362") (name "unconnected-(U9-D3-Pad6)") (class "Default")
      (node (ref "U9") (pin "6") (pinfunction "D3_6") (pintype "unspecified"))
    )
    (net (code "363") (name "unconnected-(U9-D4-Pad7)") (class "Default")
      (node (ref "U9") (pin "7") (pinfunction "D4_7") (pintype "unspecified"))
    )
    (net (code "364") (name "unconnected-(U9-D5-Pad8)") (class "Default")
      (node (ref "U9") (pin "8") (pinfunction "D5_8") (pintype "unspecified"))
    )
    (net (code "365") (name "unconnected-(U9-D6-Pad9)") (class "Default")
      (node (ref "U9") (pin "9") (pinfunction "D6_9") (pintype "unspecified"))
    )
    (net (code "366") (name "unconnected-(U9-D7-Pad10)") (class "Default")
      (node (ref "U9") (pin "10") (pinfunction "D7_10") (pintype "unspecified"))
    )
    (net (code "367") (name "unconnected-(U9-D9-Pad12)") (class "Default")
      (node (ref "U9") (pin "12") (pinfunction "D9_12") (pintype "unspecified"))
    )
    (net (code "368") (name "unconnected-(U9-D10-Pad13)") (class "Default")
      (node (ref "U9") (pin "13") (pinfunction "D10_13") (pintype "unspecified"))
    )
    (net (code "369") (name "unconnected-(U9-D11-Pad14)") (class "Default")
      (node (ref "U9") (pin "14") (pinfunction "D11_14") (pintype "unspecified"))
    )
    (net (code "370") (name "unconnected-(U9-D12-Pad15)") (class "Default")
      (node (ref "U9") (pin "15") (pinfunction "D12_15") (pintype "unspecified"))
    )
    (net (code "371") (name "unconnected-(U9-D13-Pad16)") (class "Default")
      (node (ref "U9") (pin "16") (pinfunction "D13_16") (pintype "unspecified"))
    )
    (net (code "372") (name "unconnected-(U9-GND-Pad29)") (class "Default")
      (node (ref "U9") (pin "29") (pinfunction "GND_29") (pintype "unspecified"))
    )
    (net (code "373") (name "unconnected-(U9-RESET-Pad3)") (class "Default")
      (node (ref "U9") (pin "3") (pinfunction "RESET_3") (pintype "unspecified"))
    )
    (net (code "374") (name "unconnected-(U9-RESET-Pad28)") (class "Default")
      (node (ref "U9") (pin "28") (pinfunction "RESET_28") (pintype "unspecified"))
    )
    (net (code "375") (name "unconnected-(U9-VIN-Pad30)") (class "Default")
      (node (ref "U9") (pin "30") (pinfunction "VIN_30") (pintype "unspecified"))
    )
    (net (code "376") (name "unconnected-(U10-3V-Pad29)") (class "Default")
      (node (ref "U10") (pin "29") (pinfunction "3V_29") (pintype "passive"))
    )
    (net (code "377") (name "unconnected-(U10-15{slash}A1{slash}PC1-Pad23)") (class "Default")
      (node (ref "U10") (pin "23") (pinfunction "15/A1/PC1_23") (pintype "unspecified"))
    )
    (net (code "378") (name "unconnected-(U10-16{slash}A2{slash}PC2-Pad22)") (class "Default")
      (node (ref "U10") (pin "22") (pinfunction "16/A2/PC2_22") (pintype "unspecified"))
    )
    (net (code "379") (name "unconnected-(U10-17{slash}A3{slash}PC3-Pad21)") (class "Default")
      (node (ref "U10") (pin "21") (pinfunction "17/A3/PC3_21") (pintype "unspecified"))
    )
    (net (code "380") (name "unconnected-(U10-18{slash}A4{slash}PC4{slash}SDA-Pad20)") (class "Default")
      (node (ref "U10") (pin "20") (pinfunction "18/A4/PC4/SDA_20") (pintype "unspecified"))
    )
    (net (code "381") (name "unconnected-(U10-19{slash}A5{slash}PC5{slash}SCL-Pad19)") (class "Default")
      (node (ref "U10") (pin "19") (pinfunction "19/A5/PC5/SCL_19") (pintype "unspecified"))
    )
    (net (code "382") (name "unconnected-(U10-AREF-Pad16)") (class "Default")
      (node (ref "U10") (pin "16") (pinfunction "AREF_16") (pintype "unspecified"))
    )
    (net (code "383") (name "unconnected-(U10-GND-Pad15)") (class "Default")
      (node (ref "U10") (pin "15") (pinfunction "GND_15") (pintype "passive"))
    )
    (net (code "384") (name "unconnected-(U10-GND2-Pad27)") (class "Default")
      (node (ref "U10") (pin "27") (pinfunction "GND2_27") (pintype "passive"))
    )
    (net (code "385") (name "unconnected-(U10-INT0{slash}PD2{slash}2-Pad3)") (class "Default")
      (node (ref "U10") (pin "3") (pinfunction "INT0/PD2/2_3") (pintype "unspecified"))
    )
    (net (code "386") (name "unconnected-(U10-INT1{slash}PWR{slash}PD3{slash}3-Pad4)") (class "Default")
      (node (ref "U10") (pin "4") (pinfunction "INT1/PWR/PD3/3_4") (pintype "unspecified"))
    )
    (net (code "387") (name "unconnected-(U10-IOREF-Pad31)") (class "Default")
      (node (ref "U10") (pin "31") (pinfunction "IOREF_31") (pintype "unspecified"))
    )
    (net (code "388") (name "unconnected-(U10-MISO{slash}PB4{slash}12-Pad13)") (class "Default")
      (node (ref "U10") (pin "13") (pinfunction "MISO/PB4/12_13") (pintype "unspecified"))
    )
    (net (code "389") (name "unconnected-(U10-MOSI{slash}PWR{slash}PB3{slash}11-Pad12)") (class "Default")
      (node (ref "U10") (pin "12") (pinfunction "MOSI/PWR/PB3/11_12") (pintype "unspecified"))
    )
    (net (code "390") (name "unconnected-(U10-NC-Pad32)") (class "Default")
      (node (ref "U10") (pin "32") (pinfunction "NC_32") (pintype "unspecified"))
    )
    (net (code "391") (name "unconnected-(U10-PD4{slash}4-Pad5)") (class "Default")
      (node (ref "U10") (pin "5") (pinfunction "PD4/4_5") (pintype "unspecified"))
    )
    (net (code "392") (name "unconnected-(U10-PD7{slash}7-Pad8)") (class "Default")
      (node (ref "U10") (pin "8") (pinfunction "PD7/7_8") (pintype "unspecified"))
    )
    (net (code "393") (name "unconnected-(U10-PWR{slash}PB1{slash}9-Pad10)") (class "Default")
      (node (ref "U10") (pin "10") (pinfunction "PWR/PB1/9_10") (pintype "unspecified"))
    )
    (net (code "394") (name "unconnected-(U10-PWR{slash}PD5{slash}5-Pad6)") (class "Default")
      (node (ref "U10") (pin "6") (pinfunction "PWR/PD5/5_6") (pintype "unspecified"))
    )
    (net (code "395") (name "unconnected-(U10-PWR{slash}PD6{slash}6-Pad7)") (class "Default")
      (node (ref "U10") (pin "7") (pinfunction "PWR/PD6/6_7") (pintype "unspecified"))
    )
    (net (code "396") (name "unconnected-(U10-RESET-Pad30)") (class "Default")
      (node (ref "U10") (pin "30") (pinfunction "RESET_30") (pintype "unspecified"))
    )
    (net (code "397") (name "unconnected-(U10-RX{slash}PD0{slash}0-Pad1)") (class "Default")
      (node (ref "U10") (pin "1") (pinfunction "RX/PD0/0_1") (pintype "unspecified"))
    )
    (net (code "398") (name "unconnected-(U10-SCK{slash}PB5{slash}13-Pad14)") (class "Default")
      (node (ref "U10") (pin "14") (pinfunction "SCK/PB5/13_14") (pintype "unspecified"))
    )
    (net (code "399") (name "unconnected-(U10-SCL-Pad18)") (class "Default")
      (node (ref "U10") (pin "18") (pinfunction "SCL_18") (pintype "unspecified"))
    )
    (net (code "400") (name "unconnected-(U10-SDA-Pad17)") (class "Default")
      (node (ref "U10") (pin "17") (pinfunction "SDA_17") (pintype "unspecified"))
    )
    (net (code "401") (name "unconnected-(U10-SS{slash}PWR{slash}PB2{slash}10-Pad11)") (class "Default")
      (node (ref "U10") (pin "11") (pinfunction "SS/PWR/PB2/10_11") (pintype "unspecified"))
    )
    (net (code "402") (name "unconnected-(U10-TX{slash}PD1{slash}1-Pad2)") (class "Default")
      (node (ref "U10") (pin "2") (pinfunction "TX/PD1/1_2") (pintype "unspecified"))
    )
    (net (code "403") (name "unconnected-(U10-VIN-Pad25)") (class "Default")
      (node (ref "U10") (pin "25") (pinfunction "VIN_25") (pintype "passive"))
    )
    (net (code "404") (name "unconnected-(U15-3V3-Pad17)") (class "Default")
      (node (ref "U15") (pin "17") (pinfunction "3V3_17") (pintype "unspecified"))
    )
    (net (code "405") (name "unconnected-(U15-A0-Pad19)") (class "Default")
      (node (ref "U15") (pin "19") (pinfunction "A0_19") (pintype "unspecified"))
    )
    (net (code "406") (name "unconnected-(U15-A1-Pad20)") (class "Default")
      (node (ref "U15") (pin "20") (pinfunction "A1_20") (pintype "unspecified"))
    )
    (net (code "407") (name "unconnected-(U15-A2-Pad21)") (class "Default")
      (node (ref "U15") (pin "21") (pinfunction "A2_21") (pintype "unspecified"))
    )
    (net (code "408") (name "unconnected-(U15-A6-Pad25)") (class "Default")
      (node (ref "U15") (pin "25") (pinfunction "A6_25") (pintype "unspecified"))
    )
    (net (code "409") (name "unconnected-(U15-A7-Pad26)") (class "Default")
      (node (ref "U15") (pin "26") (pinfunction "A7_26") (pintype "unspecified"))
    )
    (net (code "410") (name "unconnected-(U15-AREF-Pad18)") (class "Default")
      (node (ref "U15") (pin "18") (pinfunction "AREF_18") (pintype "unspecified"))
    )
    (net (code "411") (name "unconnected-(U15-D0{slash}RX-Pad2)") (class "Default")
      (node (ref "U15") (pin "2") (pinfunction "D0/RX_2") (pintype "unspecified"))
    )
    (net (code "412") (name "unconnected-(U15-D1{slash}TX-Pad1)") (class "Default")
      (node (ref "U15") (pin "1") (pinfunction "D1/TX_1") (pintype "unspecified"))
    )
    (net (code "413") (name "unconnected-(U15-D2-Pad5)") (class "Default")
      (node (ref "U15") (pin "5") (pinfunction "D2_5") (pintype "unspecified"))
    )
    (net (code "414") (name "unconnected-(U15-D3-Pad6)") (class "Default")
      (node (ref "U15") (pin "6") (pinfunction "D3_6") (pintype "unspecified"))
    )
    (net (code "415") (name "unconnected-(U15-D4-Pad7)") (class "Default")
      (node (ref "U15") (pin "7") (pinfunction "D4_7") (pintype "unspecified"))
    )
    (net (code "416") (name "unconnected-(U15-D5-Pad8)") (class "Default")
      (node (ref "U15") (pin "8") (pinfunction "D5_8") (pintype "unspecified"))
    )
    (net (code "417") (name "unconnected-(U15-D6-Pad9)") (class "Default")
      (node (ref "U15") (pin "9") (pinfunction "D6_9") (pintype "unspecified"))
    )
    (net (code "418") (name "unconnected-(U15-D7-Pad10)") (class "Default")
      (node (ref "U15") (pin "10") (pinfunction "D7_10") (pintype "unspecified"))
    )
    (net (code "419") (name "unconnected-(U15-D8-Pad11)") (class "Default")
      (node (ref "U15") (pin "11") (pinfunction "D8_11") (pintype "unspecified"))
    )
    (net (code "420") (name "unconnected-(U15-D9-Pad12)") (class "Default")
      (node (ref "U15") (pin "12") (pinfunction "D9_12") (pintype "unspecified"))
    )
    (net (code "421") (name "unconnected-(U15-D10-Pad13)") (class "Default")
      (node (ref "U15") (pin "13") (pinfunction "D10_13") (pintype "unspecified"))
    )
    (net (code "422") (name "unconnected-(U15-D11-Pad14)") (class "Default")
      (node (ref "U15") (pin "14") (pinfunction "D11_14") (pintype "unspecified"))
    )
    (net (code "423") (name "unconnected-(U15-D12-Pad15)") (class "Default")
      (node (ref "U15") (pin "15") (pinfunction "D12_15") (pintype "unspecified"))
    )
    (net (code "424") (name "unconnected-(U15-D13-Pad16)") (class "Default")
      (node (ref "U15") (pin "16") (pinfunction "D13_16") (pintype "unspecified"))
    )
    (net (code "425") (name "unconnected-(U15-GND-Pad4)") (class "Default")
      (node (ref "U15") (pin "4") (pinfunction "GND_4") (pintype "unspecified"))
    )
    (net (code "426") (name "unconnected-(U15-RESET-Pad3)") (class "Default")
      (node (ref "U15") (pin "3") (pinfunction "RESET_3") (pintype "unspecified"))
    )
    (net (code "427") (name "unconnected-(U15-RESET-Pad28)") (class "Default")
      (node (ref "U15") (pin "28") (pinfunction "RESET_28") (pintype "unspecified"))
    )
    (net (code "428") (name "unconnected-(U15-VIN-Pad30)") (class "Default")
      (node (ref "U15") (pin "30") (pinfunction "VIN_30") (pintype "unspecified"))
    )
    (net (code "429") (name "unconnected-(U16-3V-Pad29)") (class "Default")
      (node (ref "U16") (pin "29") (pinfunction "3V_29") (pintype "passive"))
    )
    (net (code "430") (name "unconnected-(U16-14{slash}A0{slash}PC0-Pad24)") (class "Default")
      (node (ref "U16") (pin "24") (pinfunction "14/A0/PC0_24") (pintype "unspecified"))
    )
    (net (code "431") (name "unconnected-(U16-15{slash}A1{slash}PC1-Pad23)") (class "Default")
      (node (ref "U16") (pin "23") (pinfunction "15/A1/PC1_23") (pintype "unspecified"))
    )
    (net (code "432") (name "unconnected-(U16-16{slash}A2{slash}PC2-Pad22)") (class "Default")
      (node (ref "U16") (pin "22") (pinfunction "16/A2/PC2_22") (pintype "unspecified"))
    )
    (net (code "433") (name "unconnected-(U16-AREF-Pad16)") (class "Default")
      (node (ref "U16") (pin "16") (pinfunction "AREF_16") (pintype "unspecified"))
    )
    (net (code "434") (name "unconnected-(U16-GND-Pad15)") (class "Default")
      (node (ref "U16") (pin "15") (pinfunction "GND_15") (pintype "passive"))
    )
    (net (code "435") (name "unconnected-(U16-GND2-Pad27)") (class "Default")
      (node (ref "U16") (pin "27") (pinfunction "GND2_27") (pintype "passive"))
    )
    (net (code "436") (name "unconnected-(U16-INT0{slash}PD2{slash}2-Pad3)") (class "Default")
      (node (ref "U16") (pin "3") (pinfunction "INT0/PD2/2_3") (pintype "unspecified"))
    )
    (net (code "437") (name "unconnected-(U16-INT1{slash}PWR{slash}PD3{slash}3-Pad4)") (class "Default")
      (node (ref "U16") (pin "4") (pinfunction "INT1/PWR/PD3/3_4") (pintype "unspecified"))
    )
    (net (code "438") (name "unconnected-(U16-IOREF-Pad31)") (class "Default")
      (node (ref "U16") (pin "31") (pinfunction "IOREF_31") (pintype "unspecified"))
    )
    (net (code "439") (name "unconnected-(U16-MISO{slash}PB4{slash}12-Pad13)") (class "Default")
      (node (ref "U16") (pin "13") (pinfunction "MISO/PB4/12_13") (pintype "unspecified"))
    )
    (net (code "440") (name "unconnected-(U16-MOSI{slash}PWR{slash}PB3{slash}11-Pad12)") (class "Default")
      (node (ref "U16") (pin "12") (pinfunction "MOSI/PWR/PB3/11_12") (pintype "unspecified"))
    )
    (net (code "441") (name "unconnected-(U16-NC-Pad32)") (class "Default")
      (node (ref "U16") (pin "32") (pinfunction "NC_32") (pintype "unspecified"))
    )
    (net (code "442") (name "unconnected-(U16-PB0{slash}8-Pad9)") (class "Default")
      (node (ref "U16") (pin "9") (pinfunction "PB0/8_9") (pintype "unspecified"))
    )
    (net (code "443") (name "unconnected-(U16-PD4{slash}4-Pad5)") (class "Default")
      (node (ref "U16") (pin "5") (pinfunction "PD4/4_5") (pintype "unspecified"))
    )
    (net (code "444") (name "unconnected-(U16-PD7{slash}7-Pad8)") (class "Default")
      (node (ref "U16") (pin "8") (pinfunction "PD7/7_8") (pintype "unspecified"))
    )
    (net (code "445") (name "unconnected-(U16-PWR{slash}PB1{slash}9-Pad10)") (class "Default")
      (node (ref "U16") (pin "10") (pinfunction "PWR/PB1/9_10") (pintype "unspecified"))
    )
    (net (code "446") (name "unconnected-(U16-PWR{slash}PD5{slash}5-Pad6)") (class "Default")
      (node (ref "U16") (pin "6") (pinfunction "PWR/PD5/5_6") (pintype "unspecified"))
    )
    (net (code "447") (name "unconnected-(U16-PWR{slash}PD6{slash}6-Pad7)") (class "Default")
      (node (ref "U16") (pin "7") (pinfunction "PWR/PD6/6_7") (pintype "unspecified"))
    )
    (net (code "448") (name "unconnected-(U16-RESET-Pad30)") (class "Default")
      (node (ref "U16") (pin "30") (pinfunction "RESET_30") (pintype "unspecified"))
    )
    (net (code "449") (name "unconnected-(U16-RX{slash}PD0{slash}0-Pad1)") (class "Default")
      (node (ref "U16") (pin "1") (pinfunction "RX/PD0/0_1") (pintype "unspecified"))
    )
    (net (code "450") (name "unconnected-(U16-SCK{slash}PB5{slash}13-Pad14)") (class "Default")
      (node (ref "U16") (pin "14") (pinfunction "SCK/PB5/13_14") (pintype "unspecified"))
    )
    (net (code "451") (name "unconnected-(U16-SCL-Pad18)") (class "Default")
      (node (ref "U16") (pin "18") (pinfunction "SCL_18") (pintype "unspecified"))
    )
    (net (code "452") (name "unconnected-(U16-SDA-Pad17)") (class "Default")
      (node (ref "U16") (pin "17") (pinfunction "SDA_17") (pintype "unspecified"))
    )
    (net (code "453") (name "unconnected-(U16-SS{slash}PWR{slash}PB2{slash}10-Pad11)") (class "Default")
      (node (ref "U16") (pin "11") (pinfunction "SS/PWR/PB2/10_11") (pintype "unspecified"))
    )
    (net (code "454") (name "unconnected-(U16-TX{slash}PD1{slash}1-Pad2)") (class "Default")
      (node (ref "U16") (pin "2") (pinfunction "TX/PD1/1_2") (pintype "unspecified"))
    )
    (net (code "455") (name "unconnected-(U16-VIN-Pad25)") (class "Default")
      (node (ref "U16") (pin "25") (pinfunction "VIN_25") (pintype "passive"))
    )
    (net (code "456") (name "unconnected-(U17-3V3-Pad17)") (class "Default")
      (node (ref "U17") (pin "17") (pinfunction "3V3_17") (pintype "unspecified"))
    )
    (net (code "457") (name "unconnected-(U17-A0-Pad19)") (class "Default")
      (node (ref "U17") (pin "19") (pinfunction "A0_19") (pintype "unspecified"))
    )
    (net (code "458") (name "unconnected-(U17-A1-Pad20)") (class "Default")
      (node (ref "U17") (pin "20") (pinfunction "A1_20") (pintype "unspecified"))
    )
    (net (code "459") (name "unconnected-(U17-A2-Pad21)") (class "Default")
      (node (ref "U17") (pin "21") (pinfunction "A2_21") (pintype "unspecified"))
    )
    (net (code "460") (name "unconnected-(U17-A3-Pad22)") (class "Default")
      (node (ref "U17") (pin "22") (pinfunction "A3_22") (pintype "unspecified"))
    )
    (net (code "461") (name "unconnected-(U17-A4-Pad23)") (class "Default")
      (node (ref "U17") (pin "23") (pinfunction "A4_23") (pintype "unspecified"))
    )
    (net (code "462") (name "unconnected-(U17-A5-Pad24)") (class "Default")
      (node (ref "U17") (pin "24") (pinfunction "A5_24") (pintype "unspecified"))
    )
    (net (code "463") (name "unconnected-(U17-A6-Pad25)") (class "Default")
      (node (ref "U17") (pin "25") (pinfunction "A6_25") (pintype "unspecified"))
    )
    (net (code "464") (name "unconnected-(U17-A7-Pad26)") (class "Default")
      (node (ref "U17") (pin "26") (pinfunction "A7_26") (pintype "unspecified"))
    )
    (net (code "465") (name "unconnected-(U17-AREF-Pad18)") (class "Default")
      (node (ref "U17") (pin "18") (pinfunction "AREF_18") (pintype "unspecified"))
    )
    (net (code "466") (name "unconnected-(U17-D0{slash}RX-Pad2)") (class "Default")
      (node (ref "U17") (pin "2") (pinfunction "D0/RX_2") (pintype "unspecified"))
    )
    (net (code "467") (name "unconnected-(U17-D1{slash}TX-Pad1)") (class "Default")
      (node (ref "U17") (pin "1") (pinfunction "D1/TX_1") (pintype "unspecified"))
    )
    (net (code "468") (name "unconnected-(U17-D2-Pad5)") (class "Default")
      (node (ref "U17") (pin "5") (pinfunction "D2_5") (pintype "unspecified"))
    )
    (net (code "469") (name "unconnected-(U17-D3-Pad6)") (class "Default")
      (node (ref "U17") (pin "6") (pinfunction "D3_6") (pintype "unspecified"))
    )
    (net (code "470") (name "unconnected-(U17-D4-Pad7)") (class "Default")
      (node (ref "U17") (pin "7") (pinfunction "D4_7") (pintype "unspecified"))
    )
    (net (code "471") (name "unconnected-(U17-D5-Pad8)") (class "Default")
      (node (ref "U17") (pin "8") (pinfunction "D5_8") (pintype "unspecified"))
    )
    (net (code "472") (name "unconnected-(U17-D6-Pad9)") (class "Default")
      (node (ref "U17") (pin "9") (pinfunction "D6_9") (pintype "unspecified"))
    )
    (net (code "473") (name "unconnected-(U17-D7-Pad10)") (class "Default")
      (node (ref "U17") (pin "10") (pinfunction "D7_10") (pintype "unspecified"))
    )
    (net (code "474") (name "unconnected-(U17-D9-Pad12)") (class "Default")
      (node (ref "U17") (pin "12") (pinfunction "D9_12") (pintype "unspecified"))
    )
    (net (code "475") (name "unconnected-(U17-D10-Pad13)") (class "Default")
      (node (ref "U17") (pin "13") (pinfunction "D10_13") (pintype "unspecified"))
    )
    (net (code "476") (name "unconnected-(U17-D11-Pad14)") (class "Default")
      (node (ref "U17") (pin "14") (pinfunction "D11_14") (pintype "unspecified"))
    )
    (net (code "477") (name "unconnected-(U17-D12-Pad15)") (class "Default")
      (node (ref "U17") (pin "15") (pinfunction "D12_15") (pintype "unspecified"))
    )
    (net (code "478") (name "unconnected-(U17-D13-Pad16)") (class "Default")
      (node (ref "U17") (pin "16") (pinfunction "D13_16") (pintype "unspecified"))
    )
    (net (code "479") (name "unconnected-(U17-GND-Pad4)") (class "Default")
      (node (ref "U17") (pin "4") (pinfunction "GND_4") (pintype "unspecified"))
    )
    (net (code "480") (name "unconnected-(U17-RESET-Pad3)") (class "Default")
      (node (ref "U17") (pin "3") (pinfunction "RESET_3") (pintype "unspecified"))
    )
    (net (code "481") (name "unconnected-(U17-RESET-Pad28)") (class "Default")
      (node (ref "U17") (pin "28") (pinfunction "RESET_28") (pintype "unspecified"))
    )
    (net (code "482") (name "unconnected-(U17-VIN-Pad30)") (class "Default")
      (node (ref "U17") (pin "30") (pinfunction "VIN_30") (pintype "unspecified"))
    )
    (net (code "483") (name "unconnected-(U18-3V-Pad29)") (class "Default")
      (node (ref "U18") (pin "29") (pinfunction "3V_29") (pintype "passive"))
    )
    (net (code "484") (name "unconnected-(U18-14{slash}A0{slash}PC0-Pad24)") (class "Default")
      (node (ref "U18") (pin "24") (pinfunction "14/A0/PC0_24") (pintype "unspecified"))
    )
    (net (code "485") (name "unconnected-(U18-15{slash}A1{slash}PC1-Pad23)") (class "Default")
      (node (ref "U18") (pin "23") (pinfunction "15/A1/PC1_23") (pintype "unspecified"))
    )
    (net (code "486") (name "unconnected-(U18-16{slash}A2{slash}PC2-Pad22)") (class "Default")
      (node (ref "U18") (pin "22") (pinfunction "16/A2/PC2_22") (pintype "unspecified"))
    )
    (net (code "487") (name "unconnected-(U18-17{slash}A3{slash}PC3-Pad21)") (class "Default")
      (node (ref "U18") (pin "21") (pinfunction "17/A3/PC3_21") (pintype "unspecified"))
    )
    (net (code "488") (name "unconnected-(U18-18{slash}A4{slash}PC4{slash}SDA-Pad20)") (class "Default")
      (node (ref "U18") (pin "20") (pinfunction "18/A4/PC4/SDA_20") (pintype "unspecified"))
    )
    (net (code "489") (name "unconnected-(U18-19{slash}A5{slash}PC5{slash}SCL-Pad19)") (class "Default")
      (node (ref "U18") (pin "19") (pinfunction "19/A5/PC5/SCL_19") (pintype "unspecified"))
    )
    (net (code "490") (name "unconnected-(U18-AREF-Pad16)") (class "Default")
      (node (ref "U18") (pin "16") (pinfunction "AREF_16") (pintype "unspecified"))
    )
    (net (code "491") (name "unconnected-(U18-GND-Pad15)") (class "Default")
      (node (ref "U18") (pin "15") (pinfunction "GND_15") (pintype "passive"))
    )
    (net (code "492") (name "unconnected-(U18-GND2-Pad27)") (class "Default")
      (node (ref "U18") (pin "27") (pinfunction "GND2_27") (pintype "passive"))
    )
    (net (code "493") (name "unconnected-(U18-INT0{slash}PD2{slash}2-Pad3)") (class "Default")
      (node (ref "U18") (pin "3") (pinfunction "INT0/PD2/2_3") (pintype "unspecified"))
    )
    (net (code "494") (name "unconnected-(U18-INT1{slash}PWR{slash}PD3{slash}3-Pad4)") (class "Default")
      (node (ref "U18") (pin "4") (pinfunction "INT1/PWR/PD3/3_4") (pintype "unspecified"))
    )
    (net (code "495") (name "unconnected-(U18-IOREF-Pad31)") (class "Default")
      (node (ref "U18") (pin "31") (pinfunction "IOREF_31") (pintype "unspecified"))
    )
    (net (code "496") (name "unconnected-(U18-MISO{slash}PB4{slash}12-Pad13)") (class "Default")
      (node (ref "U18") (pin "13") (pinfunction "MISO/PB4/12_13") (pintype "unspecified"))
    )
    (net (code "497") (name "unconnected-(U18-MOSI{slash}PWR{slash}PB3{slash}11-Pad12)") (class "Default")
      (node (ref "U18") (pin "12") (pinfunction "MOSI/PWR/PB3/11_12") (pintype "unspecified"))
    )
    (net (code "498") (name "unconnected-(U18-NC-Pad32)") (class "Default")
      (node (ref "U18") (pin "32") (pinfunction "NC_32") (pintype "unspecified"))
    )
    (net (code "499") (name "unconnected-(U18-PD4{slash}4-Pad5)") (class "Default")
      (node (ref "U18") (pin "5") (pinfunction "PD4/4_5") (pintype "unspecified"))
    )
    (net (code "500") (name "unconnected-(U18-PD7{slash}7-Pad8)") (class "Default")
      (node (ref "U18") (pin "8") (pinfunction "PD7/7_8") (pintype "unspecified"))
    )
    (net (code "501") (name "unconnected-(U18-PWR{slash}PB1{slash}9-Pad10)") (class "Default")
      (node (ref "U18") (pin "10") (pinfunction "PWR/PB1/9_10") (pintype "unspecified"))
    )
    (net (code "502") (name "unconnected-(U18-PWR{slash}PD5{slash}5-Pad6)") (class "Default")
      (node (ref "U18") (pin "6") (pinfunction "PWR/PD5/5_6") (pintype "unspecified"))
    )
    (net (code "503") (name "unconnected-(U18-PWR{slash}PD6{slash}6-Pad7)") (class "Default")
      (node (ref "U18") (pin "7") (pinfunction "PWR/PD6/6_7") (pintype "unspecified"))
    )
    (net (code "504") (name "unconnected-(U18-RESET-Pad30)") (class "Default")
      (node (ref "U18") (pin "30") (pinfunction "RESET_30") (pintype "unspecified"))
    )
    (net (code "505") (name "unconnected-(U18-RX{slash}PD0{slash}0-Pad1)") (class "Default")
      (node (ref "U18") (pin "1") (pinfunction "RX/PD0/0_1") (pintype "unspecified"))
    )
    (net (code "506") (name "unconnected-(U18-SCK{slash}PB5{slash}13-Pad14)") (class "Default")
      (node (ref "U18") (pin "14") (pinfunction "SCK/PB5/13_14") (pintype "unspecified"))
    )
    (net (code "507") (name "unconnected-(U18-SCL-Pad18)") (class "Default")
      (node (ref "U18") (pin "18") (pinfunction "SCL_18") (pintype "unspecified"))
    )
    (net (code "508") (name "unconnected-(U18-SDA-Pad17)") (class "Default")
      (node (ref "U18") (pin "17") (pinfunction "SDA_17") (pintype "unspecified"))
    )
    (net (code "509") (name "unconnected-(U18-SS{slash}PWR{slash}PB2{slash}10-Pad11)") (class "Default")
      (node (ref "U18") (pin "11") (pinfunction "SS/PWR/PB2/10_11") (pintype "unspecified"))
    )
    (net (code "510") (name "unconnected-(U18-TX{slash}PD1{slash}1-Pad2)") (class "Default")
      (node (ref "U18") (pin "2") (pinfunction "TX/PD1/1_2") (pintype "unspecified"))
    )
    (net (code "511") (name "unconnected-(U18-VIN-Pad25)") (class "Default")
      (node (ref "U18") (pin "25") (pinfunction "VIN_25") (pintype "passive"))
    )
    (net (code "512") (name "unconnected-(U19-3V3-Pad17)") (class "Default")
      (node (ref "U19") (pin "17") (pinfunction "3V3_17") (pintype "unspecified"))
    )
    (net (code "513") (name "unconnected-(U19-A0-Pad19)") (class "Default")
      (node (ref "U19") (pin "19") (pinfunction "A0_19") (pintype "unspecified"))
    )
    (net (code "514") (name "unconnected-(U19-A1-Pad20)") (class "Default")
      (node (ref "U19") (pin "20") (pinfunction "A1_20") (pintype "unspecified"))
    )
    (net (code "515") (name "unconnected-(U19-A2-Pad21)") (class "Default")
      (node (ref "U19") (pin "21") (pinfunction "A2_21") (pintype "unspecified"))
    )
    (net (code "516") (name "unconnected-(U19-A3-Pad22)") (class "Default")
      (node (ref "U19") (pin "22") (pinfunction "A3_22") (pintype "unspecified"))
    )
    (net (code "517") (name "unconnected-(U19-A6-Pad25)") (class "Default")
      (node (ref "U19") (pin "25") (pinfunction "A6_25") (pintype "unspecified"))
    )
    (net (code "518") (name "unconnected-(U19-A7-Pad26)") (class "Default")
      (node (ref "U19") (pin "26") (pinfunction "A7_26") (pintype "unspecified"))
    )
    (net (code "519") (name "unconnected-(U19-AREF-Pad18)") (class "Default")
      (node (ref "U19") (pin "18") (pinfunction "AREF_18") (pintype "unspecified"))
    )
    (net (code "520") (name "unconnected-(U19-D0{slash}RX-Pad2)") (class "Default")
      (node (ref "U19") (pin "2") (pinfunction "D0/RX_2") (pintype "unspecified"))
    )
    (net (code "521") (name "unconnected-(U19-D1{slash}TX-Pad1)") (class "Default")
      (node (ref "U19") (pin "1") (pinfunction "D1/TX_1") (pintype "unspecified"))
    )
    (net (code "522") (name "unconnected-(U19-D2-Pad5)") (class "Default")
      (node (ref "U19") (pin "5") (pinfunction "D2_5") (pintype "unspecified"))
    )
    (net (code "523") (name "unconnected-(U19-D3-Pad6)") (class "Default")
      (node (ref "U19") (pin "6") (pinfunction "D3_6") (pintype "unspecified"))
    )
    (net (code "524") (name "unconnected-(U19-D4-Pad7)") (class "Default")
      (node (ref "U19") (pin "7") (pinfunction "D4_7") (pintype "unspecified"))
    )
    (net (code "525") (name "unconnected-(U19-D5-Pad8)") (class "Default")
      (node (ref "U19") (pin "8") (pinfunction "D5_8") (pintype "unspecified"))
    )
    (net (code "526") (name "unconnected-(U19-D6-Pad9)") (class "Default")
      (node (ref "U19") (pin "9") (pinfunction "D6_9") (pintype "unspecified"))
    )
    (net (code "527") (name "unconnected-(U19-D7-Pad10)") (class "Default")
      (node (ref "U19") (pin "10") (pinfunction "D7_10") (pintype "unspecified"))
    )
    (net (code "528") (name "unconnected-(U19-D8-Pad11)") (class "Default")
      (node (ref "U19") (pin "11") (pinfunction "D8_11") (pintype "unspecified"))
    )
    (net (code "529") (name "unconnected-(U19-D9-Pad12)") (class "Default")
      (node (ref "U19") (pin "12") (pinfunction "D9_12") (pintype "unspecified"))
    )
    (net (code "530") (name "unconnected-(U19-D10-Pad13)") (class "Default")
      (node (ref "U19") (pin "13") (pinfunction "D10_13") (pintype "unspecified"))
    )
    (net (code "531") (name "unconnected-(U19-D11-Pad14)") (class "Default")
      (node (ref "U19") (pin "14") (pinfunction "D11_14") (pintype "unspecified"))
    )
    (net (code "532") (name "unconnected-(U19-D12-Pad15)") (class "Default")
      (node (ref "U19") (pin "15") (pinfunction "D12_15") (pintype "unspecified"))
    )
    (net (code "533") (name "unconnected-(U19-D13-Pad16)") (class "Default")
      (node (ref "U19") (pin "16") (pinfunction "D13_16") (pintype "unspecified"))
    )
    (net (code "534") (name "unconnected-(U19-GND-Pad4)") (class "Default")
      (node (ref "U19") (pin "4") (pinfunction "GND_4") (pintype "unspecified"))
    )
    (net (code "535") (name "unconnected-(U19-RESET-Pad3)") (class "Default")
      (node (ref "U19") (pin "3") (pinfunction "RESET_3") (pintype "unspecified"))
    )
    (net (code "536") (name "unconnected-(U19-RESET-Pad28)") (class "Default")
      (node (ref "U19") (pin "28") (pinfunction "RESET_28") (pintype "unspecified"))
    )
    (net (code "537") (name "unconnected-(U19-VIN-Pad30)") (class "Default")
      (node (ref "U19") (pin "30") (pinfunction "VIN_30") (pintype "unspecified"))
    )
    (net (code "538") (name "unconnected-(U20-3V-Pad29)") (class "Default")
      (node (ref "U20") (pin "29") (pinfunction "3V_29") (pintype "passive"))
    )
    (net (code "539") (name "unconnected-(U20-14{slash}A0{slash}PC0-Pad24)") (class "Default")
      (node (ref "U20") (pin "24") (pinfunction "14/A0/PC0_24") (pintype "unspecified"))
    )
    (net (code "540") (name "unconnected-(U20-15{slash}A1{slash}PC1-Pad23)") (class "Default")
      (node (ref "U20") (pin "23") (pinfunction "15/A1/PC1_23") (pintype "unspecified"))
    )
    (net (code "541") (name "unconnected-(U20-16{slash}A2{slash}PC2-Pad22)") (class "Default")
      (node (ref "U20") (pin "22") (pinfunction "16/A2/PC2_22") (pintype "unspecified"))
    )
    (net (code "542") (name "unconnected-(U20-17{slash}A3{slash}PC3-Pad21)") (class "Default")
      (node (ref "U20") (pin "21") (pinfunction "17/A3/PC3_21") (pintype "unspecified"))
    )
    (net (code "543") (name "unconnected-(U20-AREF-Pad16)") (class "Default")
      (node (ref "U20") (pin "16") (pinfunction "AREF_16") (pintype "unspecified"))
    )
    (net (code "544") (name "unconnected-(U20-GND-Pad15)") (class "Default")
      (node (ref "U20") (pin "15") (pinfunction "GND_15") (pintype "passive"))
    )
    (net (code "545") (name "unconnected-(U20-GND2-Pad27)") (class "Default")
      (node (ref "U20") (pin "27") (pinfunction "GND2_27") (pintype "passive"))
    )
    (net (code "546") (name "unconnected-(U20-INT0{slash}PD2{slash}2-Pad3)") (class "Default")
      (node (ref "U20") (pin "3") (pinfunction "INT0/PD2/2_3") (pintype "unspecified"))
    )
    (net (code "547") (name "unconnected-(U20-INT1{slash}PWR{slash}PD3{slash}3-Pad4)") (class "Default")
      (node (ref "U20") (pin "4") (pinfunction "INT1/PWR/PD3/3_4") (pintype "unspecified"))
    )
    (net (code "548") (name "unconnected-(U20-IOREF-Pad31)") (class "Default")
      (node (ref "U20") (pin "31") (pinfunction "IOREF_31") (pintype "unspecified"))
    )
    (net (code "549") (name "unconnected-(U20-MISO{slash}PB4{slash}12-Pad13)") (class "Default")
      (node (ref "U20") (pin "13") (pinfunction "MISO/PB4/12_13") (pintype "unspecified"))
    )
    (net (code "550") (name "unconnected-(U20-MOSI{slash}PWR{slash}PB3{slash}11-Pad12)") (class "Default")
      (node (ref "U20") (pin "12") (pinfunction "MOSI/PWR/PB3/11_12") (pintype "unspecified"))
    )
    (net (code "551") (name "unconnected-(U20-NC-Pad32)") (class "Default")
      (node (ref "U20") (pin "32") (pinfunction "NC_32") (pintype "unspecified"))
    )
    (net (code "552") (name "unconnected-(U20-PB0{slash}8-Pad9)") (class "Default")
      (node (ref "U20") (pin "9") (pinfunction "PB0/8_9") (pintype "unspecified"))
    )
    (net (code "553") (name "unconnected-(U20-PD4{slash}4-Pad5)") (class "Default")
      (node (ref "U20") (pin "5") (pinfunction "PD4/4_5") (pintype "unspecified"))
    )
    (net (code "554") (name "unconnected-(U20-PD7{slash}7-Pad8)") (class "Default")
      (node (ref "U20") (pin "8") (pinfunction "PD7/7_8") (pintype "unspecified"))
    )
    (net (code "555") (name "unconnected-(U20-PWR{slash}PB1{slash}9-Pad10)") (class "Default")
      (node (ref "U20") (pin "10") (pinfunction "PWR/PB1/9_10") (pintype "unspecified"))
    )
    (net (code "556") (name "unconnected-(U20-PWR{slash}PD5{slash}5-Pad6)") (class "Default")
      (node (ref "U20") (pin "6") (pinfunction "PWR/PD5/5_6") (pintype "unspecified"))
    )
    (net (code "557") (name "unconnected-(U20-PWR{slash}PD6{slash}6-Pad7)") (class "Default")
      (node (ref "U20") (pin "7") (pinfunction "PWR/PD6/6_7") (pintype "unspecified"))
    )
    (net (code "558") (name "unconnected-(U20-RESET-Pad30)") (class "Default")
      (node (ref "U20") (pin "30") (pinfunction "RESET_30") (pintype "unspecified"))
    )
    (net (code "559") (name "unconnected-(U20-RX{slash}PD0{slash}0-Pad1)") (class "Default")
      (node (ref "U20") (pin "1") (pinfunction "RX/PD0/0_1") (pintype "unspecified"))
    )
    (net (code "560") (name "unconnected-(U20-SCK{slash}PB5{slash}13-Pad14)") (class "Default")
      (node (ref "U20") (pin "14") (pinfunction "SCK/PB5/13_14") (pintype "unspecified"))
    )
    (net (code "561") (name "unconnected-(U20-SCL-Pad18)") (class "Default")
      (node (ref "U20") (pin "18") (pinfunction "SCL_18") (pintype "unspecified"))
    )
    (net (code "562") (name "unconnected-(U20-SDA-Pad17)") (class "Default")
      (node (ref "U20") (pin "17") (pinfunction "SDA_17") (pintype "unspecified"))
    )
    (net (code "563") (name "unconnected-(U20-SS{slash}PWR{slash}PB2{slash}10-Pad11)") (class "Default")
      (node (ref "U20") (pin "11") (pinfunction "SS/PWR/PB2/10_11") (pintype "unspecified"))
    )
    (net (code "564") (name "unconnected-(U20-TX{slash}PD1{slash}1-Pad2)") (class "Default")
      (node (ref "U20") (pin "2") (pinfunction "TX/PD1/1_2") (pintype "unspecified"))
    )
    (net (code "565") (name "unconnected-(U20-VIN-Pad25)") (class "Default")
      (node (ref "U20") (pin "25") (pinfunction "VIN_25") (pintype "passive"))
    )
    (net (code "566") (name "unconnected-(U24-3V3-Pad17)") (class "Default")
      (node (ref "U24") (pin "17") (pinfunction "3V3_17") (pintype "unspecified"))
    )
    (net (code "567") (name "unconnected-(U24-A6-Pad25)") (class "Default")
      (node (ref "U24") (pin "25") (pinfunction "A6_25") (pintype "unspecified"))
    )
    (net (code "568") (name "unconnected-(U24-A7-Pad26)") (class "Default")
      (node (ref "U24") (pin "26") (pinfunction "A7_26") (pintype "unspecified"))
    )
    (net (code "569") (name "unconnected-(U24-AREF-Pad18)") (class "Default")
      (node (ref "U24") (pin "18") (pinfunction "AREF_18") (pintype "unspecified"))
    )
    (net (code "570") (name "unconnected-(U24-D0{slash}RX-Pad2)") (class "Default")
      (node (ref "U24") (pin "2") (pinfunction "D0/RX_2") (pintype "unspecified"))
    )
    (net (code "571") (name "unconnected-(U24-D1{slash}TX-Pad1)") (class "Default")
      (node (ref "U24") (pin "1") (pinfunction "D1/TX_1") (pintype "unspecified"))
    )
    (net (code "572") (name "unconnected-(U24-D2-Pad5)") (class "Default")
      (node (ref "U24") (pin "5") (pinfunction "D2_5") (pintype "unspecified"))
    )
    (net (code "573") (name "unconnected-(U24-D3-Pad6)") (class "Default")
      (node (ref "U24") (pin "6") (pinfunction "D3_6") (pintype "unspecified"))
    )
    (net (code "574") (name "unconnected-(U24-D4-Pad7)") (class "Default")
      (node (ref "U24") (pin "7") (pinfunction "D4_7") (pintype "unspecified"))
    )
    (net (code "575") (name "unconnected-(U24-D5-Pad8)") (class "Default")
      (node (ref "U24") (pin "8") (pinfunction "D5_8") (pintype "unspecified"))
    )
    (net (code "576") (name "unconnected-(U24-D6-Pad9)") (class "Default")
      (node (ref "U24") (pin "9") (pinfunction "D6_9") (pintype "unspecified"))
    )
    (net (code "577") (name "unconnected-(U24-D7-Pad10)") (class "Default")
      (node (ref "U24") (pin "10") (pinfunction "D7_10") (pintype "unspecified"))
    )
    (net (code "578") (name "unconnected-(U24-D8-Pad11)") (class "Default")
      (node (ref "U24") (pin "11") (pinfunction "D8_11") (pintype "unspecified"))
    )
    (net (code "579") (name "unconnected-(U24-D9-Pad12)") (class "Default")
      (node (ref "U24") (pin "12") (pinfunction "D9_12") (pintype "unspecified"))
    )
    (net (code "580") (name "unconnected-(U24-D10-Pad13)") (class "Default")
      (node (ref "U24") (pin "13") (pinfunction "D10_13") (pintype "unspecified"))
    )
    (net (code "581") (name "unconnected-(U24-D11-Pad14)") (class "Default")
      (node (ref "U24") (pin "14") (pinfunction "D11_14") (pintype "unspecified"))
    )
    (net (code "582") (name "unconnected-(U24-D12-Pad15)") (class "Default")
      (node (ref "U24") (pin "15") (pinfunction "D12_15") (pintype "unspecified"))
    )
    (net (code "583") (name "unconnected-(U24-D13-Pad16)") (class "Default")
      (node (ref "U24") (pin "16") (pinfunction "D13_16") (pintype "unspecified"))
    )
    (net (code "584") (name "unconnected-(U24-GND-Pad4)") (class "Default")
      (node (ref "U24") (pin "4") (pinfunction "GND_4") (pintype "unspecified"))
    )
    (net (code "585") (name "unconnected-(U24-RESET-Pad3)") (class "Default")
      (node (ref "U24") (pin "3") (pinfunction "RESET_3") (pintype "unspecified"))
    )
    (net (code "586") (name "unconnected-(U24-RESET-Pad28)") (class "Default")
      (node (ref "U24") (pin "28") (pinfunction "RESET_28") (pintype "unspecified"))
    )
    (net (code "587") (name "unconnected-(U24-VIN-Pad30)") (class "Default")
      (node (ref "U24") (pin "30") (pinfunction "VIN_30") (pintype "unspecified"))
    )
    (net (code "588") (name "unconnected-(U25-3V-Pad29)") (class "Default")
      (node (ref "U25") (pin "29") (pinfunction "3V_29") (pintype "passive"))
    )
    (net (code "589") (name "unconnected-(U25-AREF-Pad16)") (class "Default")
      (node (ref "U25") (pin "16") (pinfunction "AREF_16") (pintype "unspecified"))
    )
    (net (code "590") (name "unconnected-(U25-GND-Pad15)") (class "Default")
      (node (ref "U25") (pin "15") (pinfunction "GND_15") (pintype "passive"))
    )
    (net (code "591") (name "unconnected-(U25-GND2-Pad27)") (class "Default")
      (node (ref "U25") (pin "27") (pinfunction "GND2_27") (pintype "passive"))
    )
    (net (code "592") (name "unconnected-(U25-INT0{slash}PD2{slash}2-Pad3)") (class "Default")
      (node (ref "U25") (pin "3") (pinfunction "INT0/PD2/2_3") (pintype "unspecified"))
    )
    (net (code "593") (name "unconnected-(U25-INT1{slash}PWR{slash}PD3{slash}3-Pad4)") (class "Default")
      (node (ref "U25") (pin "4") (pinfunction "INT1/PWR/PD3/3_4") (pintype "unspecified"))
    )
    (net (code "594") (name "unconnected-(U25-IOREF-Pad31)") (class "Default")
      (node (ref "U25") (pin "31") (pinfunction "IOREF_31") (pintype "unspecified"))
    )
    (net (code "595") (name "unconnected-(U25-MISO{slash}PB4{slash}12-Pad13)") (class "Default")
      (node (ref "U25") (pin "13") (pinfunction "MISO/PB4/12_13") (pintype "unspecified"))
    )
    (net (code "596") (name "unconnected-(U25-MOSI{slash}PWR{slash}PB3{slash}11-Pad12)") (class "Default")
      (node (ref "U25") (pin "12") (pinfunction "MOSI/PWR/PB3/11_12") (pintype "unspecified"))
    )
    (net (code "597") (name "unconnected-(U25-NC-Pad32)") (class "Default")
      (node (ref "U25") (pin "32") (pinfunction "NC_32") (pintype "unspecified"))
    )
    (net (code "598") (name "unconnected-(U25-PB0{slash}8-Pad9)") (class "Default")
      (node (ref "U25") (pin "9") (pinfunction "PB0/8_9") (pintype "unspecified"))
    )
    (net (code "599") (name "unconnected-(U25-PD4{slash}4-Pad5)") (class "Default")
      (node (ref "U25") (pin "5") (pinfunction "PD4/4_5") (pintype "unspecified"))
    )
    (net (code "600") (name "unconnected-(U25-PD7{slash}7-Pad8)") (class "Default")
      (node (ref "U25") (pin "8") (pinfunction "PD7/7_8") (pintype "unspecified"))
    )
    (net (code "601") (name "unconnected-(U25-PWR{slash}PB1{slash}9-Pad10)") (class "Default")
      (node (ref "U25") (pin "10") (pinfunction "PWR/PB1/9_10") (pintype "unspecified"))
    )
    (net (code "602") (name "unconnected-(U25-PWR{slash}PD5{slash}5-Pad6)") (class "Default")
      (node (ref "U25") (pin "6") (pinfunction "PWR/PD5/5_6") (pintype "unspecified"))
    )
    (net (code "603") (name "unconnected-(U25-PWR{slash}PD6{slash}6-Pad7)") (class "Default")
      (node (ref "U25") (pin "7") (pinfunction "PWR/PD6/6_7") (pintype "unspecified"))
    )
    (net (code "604") (name "unconnected-(U25-RESET-Pad30)") (class "Default")
      (node (ref "U25") (pin "30") (pinfunction "RESET_30") (pintype "unspecified"))
    )
    (net (code "605") (name "unconnected-(U25-RX{slash}PD0{slash}0-Pad1)") (class "Default")
      (node (ref "U25") (pin "1") (pinfunction "RX/PD0/0_1") (pintype "unspecified"))
    )
    (net (code "606") (name "unconnected-(U25-SCK{slash}PB5{slash}13-Pad14)") (class "Default")
      (node (ref "U25") (pin "14") (pinfunction "SCK/PB5/13_14") (pintype "unspecified"))
    )
    (net (code "607") (name "unconnected-(U25-SCL-Pad18)") (class "Default")
      (node (ref "U25") (pin "18") (pinfunction "SCL_18") (pintype "unspecified"))
    )
    (net (code "608") (name "unconnected-(U25-SDA-Pad17)") (class "Default")
      (node (ref "U25") (pin "17") (pinfunction "SDA_17") (pintype "unspecified"))
    )
    (net (code "609") (name "unconnected-(U25-SS{slash}PWR{slash}PB2{slash}10-Pad11)") (class "Default")
      (node (ref "U25") (pin "11") (pinfunction "SS/PWR/PB2/10_11") (pintype "unspecified"))
    )
    (net (code "610") (name "unconnected-(U25-TX{slash}PD1{slash}1-Pad2)") (class "Default")
      (node (ref "U25") (pin "2") (pinfunction "TX/PD1/1_2") (pintype "unspecified"))
    )
    (net (code "611") (name "unconnected-(U25-VIN-Pad25)") (class "Default")
      (node (ref "U25") (pin "25") (pinfunction "VIN_25") (pintype "passive"))
    )
    (net (code "612") (name "unconnected-(U27-3V-Pad29)") (class "Default")
      (node (ref "U27") (pin "29") (pinfunction "3V_29") (pintype "passive"))
    )
    (net (code "613") (name "unconnected-(U27-14{slash}A0{slash}PC0-Pad24)") (class "Default")
      (node (ref "U27") (pin "24") (pinfunction "14/A0/PC0_24") (pintype "unspecified"))
    )
    (net (code "614") (name "unconnected-(U27-15{slash}A1{slash}PC1-Pad23)") (class "Default")
      (node (ref "U27") (pin "23") (pinfunction "15/A1/PC1_23") (pintype "unspecified"))
    )
    (net (code "615") (name "unconnected-(U27-16{slash}A2{slash}PC2-Pad22)") (class "Default")
      (node (ref "U27") (pin "22") (pinfunction "16/A2/PC2_22") (pintype "unspecified"))
    )
    (net (code "616") (name "unconnected-(U27-17{slash}A3{slash}PC3-Pad21)") (class "Default")
      (node (ref "U27") (pin "21") (pinfunction "17/A3/PC3_21") (pintype "unspecified"))
    )
    (net (code "617") (name "unconnected-(U27-AREF-Pad16)") (class "Default")
      (node (ref "U27") (pin "16") (pinfunction "AREF_16") (pintype "unspecified"))
    )
    (net (code "618") (name "unconnected-(U27-GND-Pad15)") (class "Default")
      (node (ref "U27") (pin "15") (pinfunction "GND_15") (pintype "passive"))
    )
    (net (code "619") (name "unconnected-(U27-GND2-Pad27)") (class "Default")
      (node (ref "U27") (pin "27") (pinfunction "GND2_27") (pintype "passive"))
    )
    (net (code "620") (name "unconnected-(U27-INT0{slash}PD2{slash}2-Pad3)") (class "Default")
      (node (ref "U27") (pin "3") (pinfunction "INT0/PD2/2_3") (pintype "unspecified"))
    )
    (net (code "621") (name "unconnected-(U27-INT1{slash}PWR{slash}PD3{slash}3-Pad4)") (class "Default")
      (node (ref "U27") (pin "4") (pinfunction "INT1/PWR/PD3/3_4") (pintype "unspecified"))
    )
    (net (code "622") (name "unconnected-(U27-IOREF-Pad31)") (class "Default")
      (node (ref "U27") (pin "31") (pinfunction "IOREF_31") (pintype "unspecified"))
    )
    (net (code "623") (name "unconnected-(U27-MISO{slash}PB4{slash}12-Pad13)") (class "Default")
      (node (ref "U27") (pin "13") (pinfunction "MISO/PB4/12_13") (pintype "unspecified"))
    )
    (net (code "624") (name "unconnected-(U27-MOSI{slash}PWR{slash}PB3{slash}11-Pad12)") (class "Default")
      (node (ref "U27") (pin "12") (pinfunction "MOSI/PWR/PB3/11_12") (pintype "unspecified"))
    )
    (net (code "625") (name "unconnected-(U27-NC-Pad32)") (class "Default")
      (node (ref "U27") (pin "32") (pinfunction "NC_32") (pintype "unspecified"))
    )
    (net (code "626") (name "unconnected-(U27-PB0{slash}8-Pad9)") (class "Default")
      (node (ref "U27") (pin "9") (pinfunction "PB0/8_9") (pintype "unspecified"))
    )
    (net (code "627") (name "unconnected-(U27-PD4{slash}4-Pad5)") (class "Default")
      (node (ref "U27") (pin "5") (pinfunction "PD4/4_5") (pintype "unspecified"))
    )
    (net (code "628") (name "unconnected-(U27-PD7{slash}7-Pad8)") (class "Default")
      (node (ref "U27") (pin "8") (pinfunction "PD7/7_8") (pintype "unspecified"))
    )
    (net (code "629") (name "unconnected-(U27-PWR{slash}PB1{slash}9-Pad10)") (class "Default")
      (node (ref "U27") (pin "10") (pinfunction "PWR/PB1/9_10") (pintype "unspecified"))
    )
    (net (code "630") (name "unconnected-(U27-PWR{slash}PD5{slash}5-Pad6)") (class "Default")
      (node (ref "U27") (pin "6") (pinfunction "PWR/PD5/5_6") (pintype "unspecified"))
    )
    (net (code "631") (name "unconnected-(U27-PWR{slash}PD6{slash}6-Pad7)") (class "Default")
      (node (ref "U27") (pin "7") (pinfunction "PWR/PD6/6_7") (pintype "unspecified"))
    )
    (net (code "632") (name "unconnected-(U27-RESET-Pad30)") (class "Default")
      (node (ref "U27") (pin "30") (pinfunction "RESET_30") (pintype "unspecified"))
    )
    (net (code "633") (name "unconnected-(U27-RX{slash}PD0{slash}0-Pad1)") (class "Default")
      (node (ref "U27") (pin "1") (pinfunction "RX/PD0/0_1") (pintype "unspecified"))
    )
    (net (code "634") (name "unconnected-(U27-SCK{slash}PB5{slash}13-Pad14)") (class "Default")
      (node (ref "U27") (pin "14") (pinfunction "SCK/PB5/13_14") (pintype "unspecified"))
    )
    (net (code "635") (name "unconnected-(U27-SCL-Pad18)") (class "Default")
      (node (ref "U27") (pin "18") (pinfunction "SCL_18") (pintype "unspecified"))
    )
    (net (code "636") (name "unconnected-(U27-SDA-Pad17)") (class "Default")
      (node (ref "U27") (pin "17") (pinfunction "SDA_17") (pintype "unspecified"))
    )
    (net (code "637") (name "unconnected-(U27-SS{slash}PWR{slash}PB2{slash}10-Pad11)") (class "Default")
      (node (ref "U27") (pin "11") (pinfunction "SS/PWR/PB2/10_11") (pintype "unspecified"))
    )
    (net (code "638") (name "unconnected-(U27-TX{slash}PD1{slash}1-Pad2)") (class "Default")
      (node (ref "U27") (pin "2") (pinfunction "TX/PD1/1_2") (pintype "unspecified"))
    )
    (net (code "639") (name "unconnected-(U27-VIN-Pad25)") (class "Default")
      (node (ref "U27") (pin "25") (pinfunction "VIN_25") (pintype "passive"))
    )
    (net (code "640") (name "unconnected-(U28-3V3-Pad17)") (class "Default")
      (node (ref "U28") (pin "17") (pinfunction "3V3_17") (pintype "unspecified"))
    )
    (net (code "641") (name "unconnected-(U28-A0-Pad19)") (class "Default")
      (node (ref "U28") (pin "19") (pinfunction "A0_19") (pintype "unspecified"))
    )
    (net (code "642") (name "unconnected-(U28-A1-Pad20)") (class "Default")
      (node (ref "U28") (pin "20") (pinfunction "A1_20") (pintype "unspecified"))
    )
    (net (code "643") (name "unconnected-(U28-A2-Pad21)") (class "Default")
      (node (ref "U28") (pin "21") (pinfunction "A2_21") (pintype "unspecified"))
    )
    (net (code "644") (name "unconnected-(U28-A3-Pad22)") (class "Default")
      (node (ref "U28") (pin "22") (pinfunction "A3_22") (pintype "unspecified"))
    )
    (net (code "645") (name "unconnected-(U28-A6-Pad25)") (class "Default")
      (node (ref "U28") (pin "25") (pinfunction "A6_25") (pintype "unspecified"))
    )
    (net (code "646") (name "unconnected-(U28-A7-Pad26)") (class "Default")
      (node (ref "U28") (pin "26") (pinfunction "A7_26") (pintype "unspecified"))
    )
    (net (code "647") (name "unconnected-(U28-AREF-Pad18)") (class "Default")
      (node (ref "U28") (pin "18") (pinfunction "AREF_18") (pintype "unspecified"))
    )
    (net (code "648") (name "unconnected-(U28-D0{slash}RX-Pad2)") (class "Default")
      (node (ref "U28") (pin "2") (pinfunction "D0/RX_2") (pintype "unspecified"))
    )
    (net (code "649") (name "unconnected-(U28-D1{slash}TX-Pad1)") (class "Default")
      (node (ref "U28") (pin "1") (pinfunction "D1/TX_1") (pintype "unspecified"))
    )
    (net (code "650") (name "unconnected-(U28-D2-Pad5)") (class "Default")
      (node (ref "U28") (pin "5") (pinfunction "D2_5") (pintype "unspecified"))
    )
    (net (code "651") (name "unconnected-(U28-D3-Pad6)") (class "Default")
      (node (ref "U28") (pin "6") (pinfunction "D3_6") (pintype "unspecified"))
    )
    (net (code "652") (name "unconnected-(U28-D4-Pad7)") (class "Default")
      (node (ref "U28") (pin "7") (pinfunction "D4_7") (pintype "unspecified"))
    )
    (net (code "653") (name "unconnected-(U28-D5-Pad8)") (class "Default")
      (node (ref "U28") (pin "8") (pinfunction "D5_8") (pintype "unspecified"))
    )
    (net (code "654") (name "unconnected-(U28-D6-Pad9)") (class "Default")
      (node (ref "U28") (pin "9") (pinfunction "D6_9") (pintype "unspecified"))
    )
    (net (code "655") (name "unconnected-(U28-D7-Pad10)") (class "Default")
      (node (ref "U28") (pin "10") (pinfunction "D7_10") (pintype "unspecified"))
    )
    (net (code "656") (name "unconnected-(U28-D8-Pad11)") (class "Default")
      (node (ref "U28") (pin "11") (pinfunction "D8_11") (pintype "unspecified"))
    )
    (net (code "657") (name "unconnected-(U28-D9-Pad12)") (class "Default")
      (node (ref "U28") (pin "12") (pinfunction "D9_12") (pintype "unspecified"))
    )
    (net (code "658") (name "unconnected-(U28-D10-Pad13)") (class "Default")
      (node (ref "U28") (pin "13") (pinfunction "D10_13") (pintype "unspecified"))
    )
    (net (code "659") (name "unconnected-(U28-D11-Pad14)") (class "Default")
      (node (ref "U28") (pin "14") (pinfunction "D11_14") (pintype "unspecified"))
    )
    (net (code "660") (name "unconnected-(U28-D12-Pad15)") (class "Default")
      (node (ref "U28") (pin "15") (pinfunction "D12_15") (pintype "unspecified"))
    )
    (net (code "661") (name "unconnected-(U28-D13-Pad16)") (class "Default")
      (node (ref "U28") (pin "16") (pinfunction "D13_16") (pintype "unspecified"))
    )
    (net (code "662") (name "unconnected-(U28-GND-Pad29)") (class "Default")
      (node (ref "U28") (pin "29") (pinfunction "GND_29") (pintype "unspecified"))
    )
    (net (code "663") (name "unconnected-(U28-RESET-Pad3)") (class "Default")
      (node (ref "U28") (pin "3") (pinfunction "RESET_3") (pintype "unspecified"))
    )
    (net (code "664") (name "unconnected-(U28-RESET-Pad28)") (class "Default")
      (node (ref "U28") (pin "28") (pinfunction "RESET_28") (pintype "unspecified"))
    )
    (net (code "665") (name "unconnected-(U28-VIN-Pad30)") (class "Default")
      (node (ref "U28") (pin "30") (pinfunction "VIN_30") (pintype "unspecified"))
    )
  )
)
